# backplane.net
KiCad netlist of a schematic drawn in EAGLE
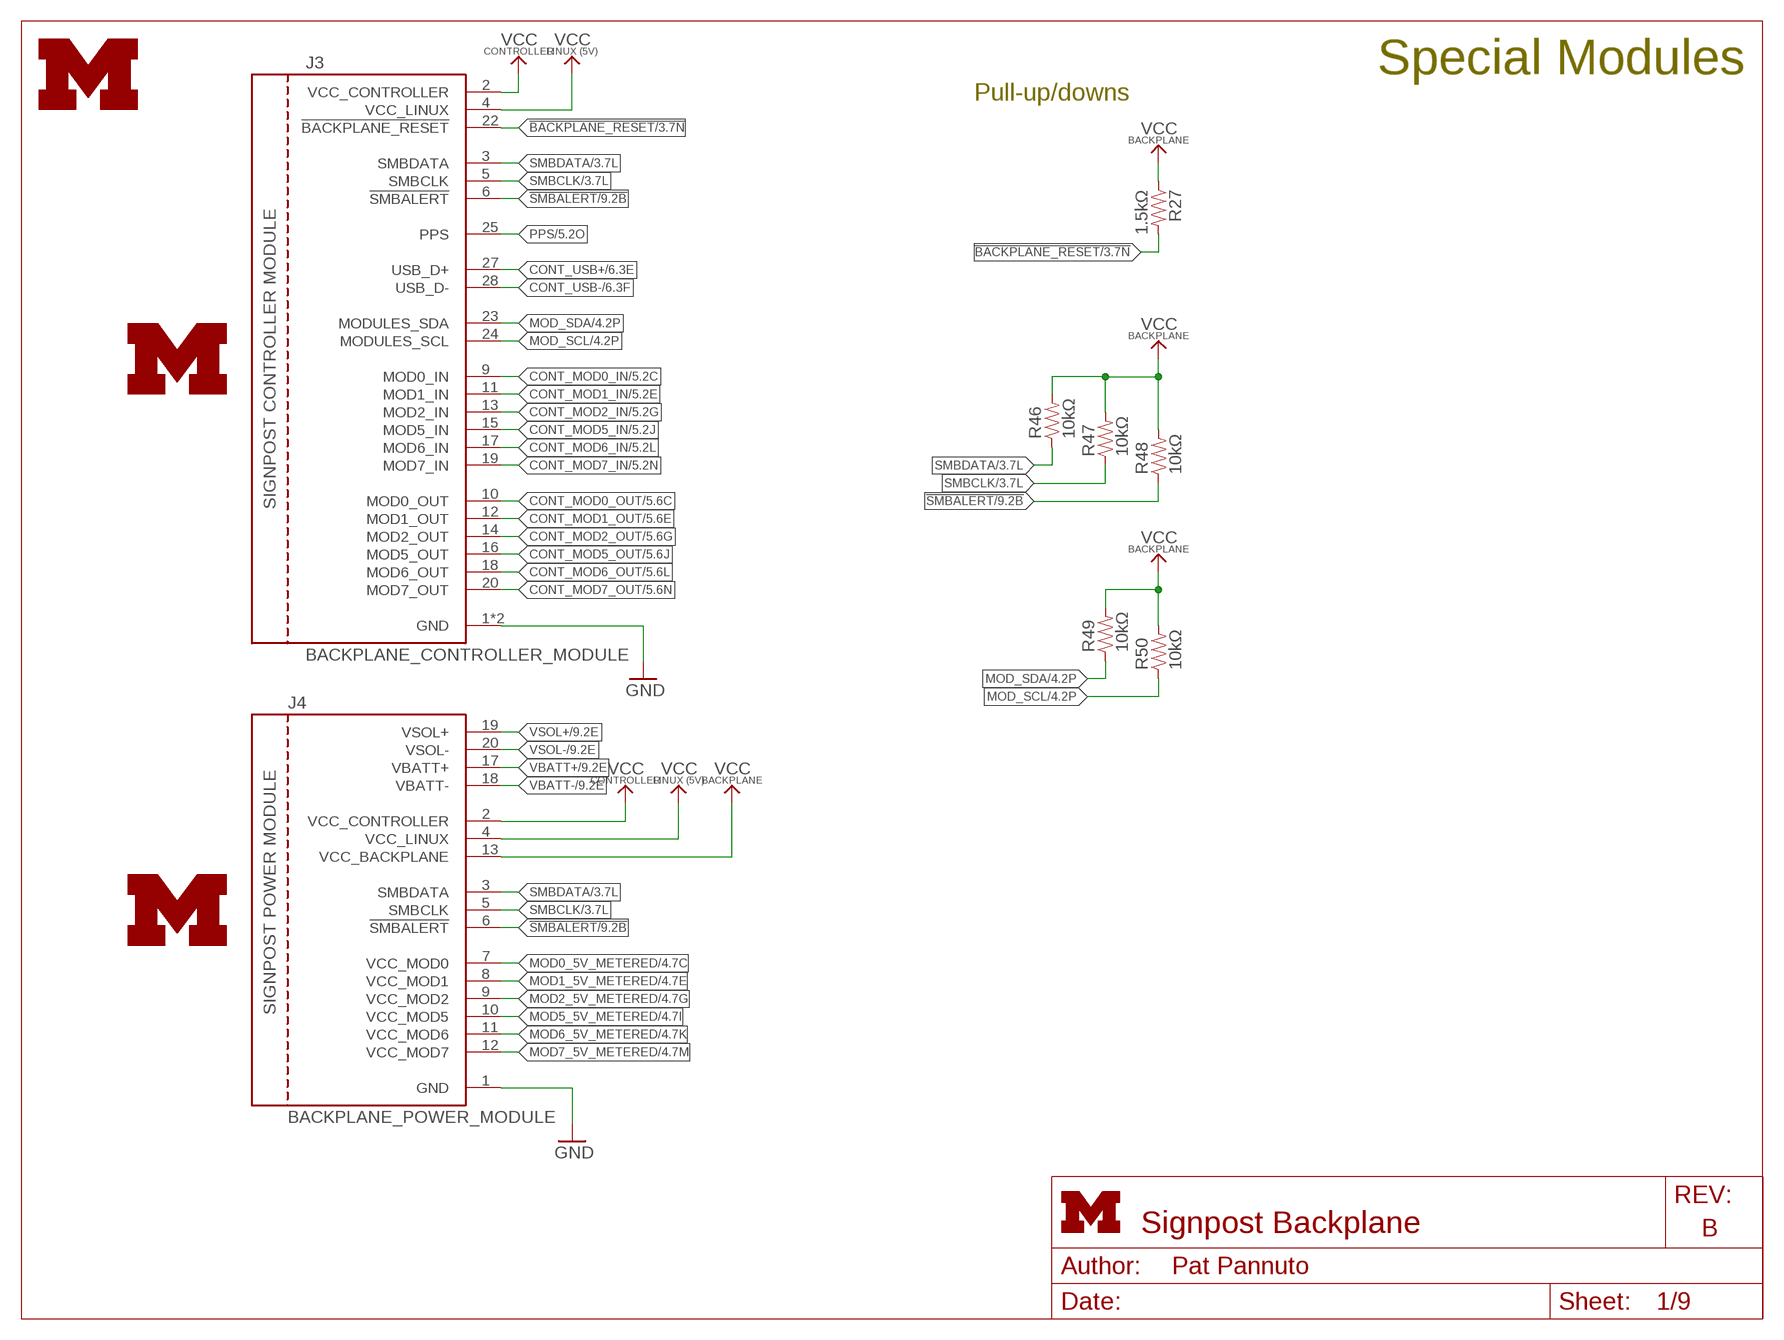
[diagram p0: schematic, sheet 1]
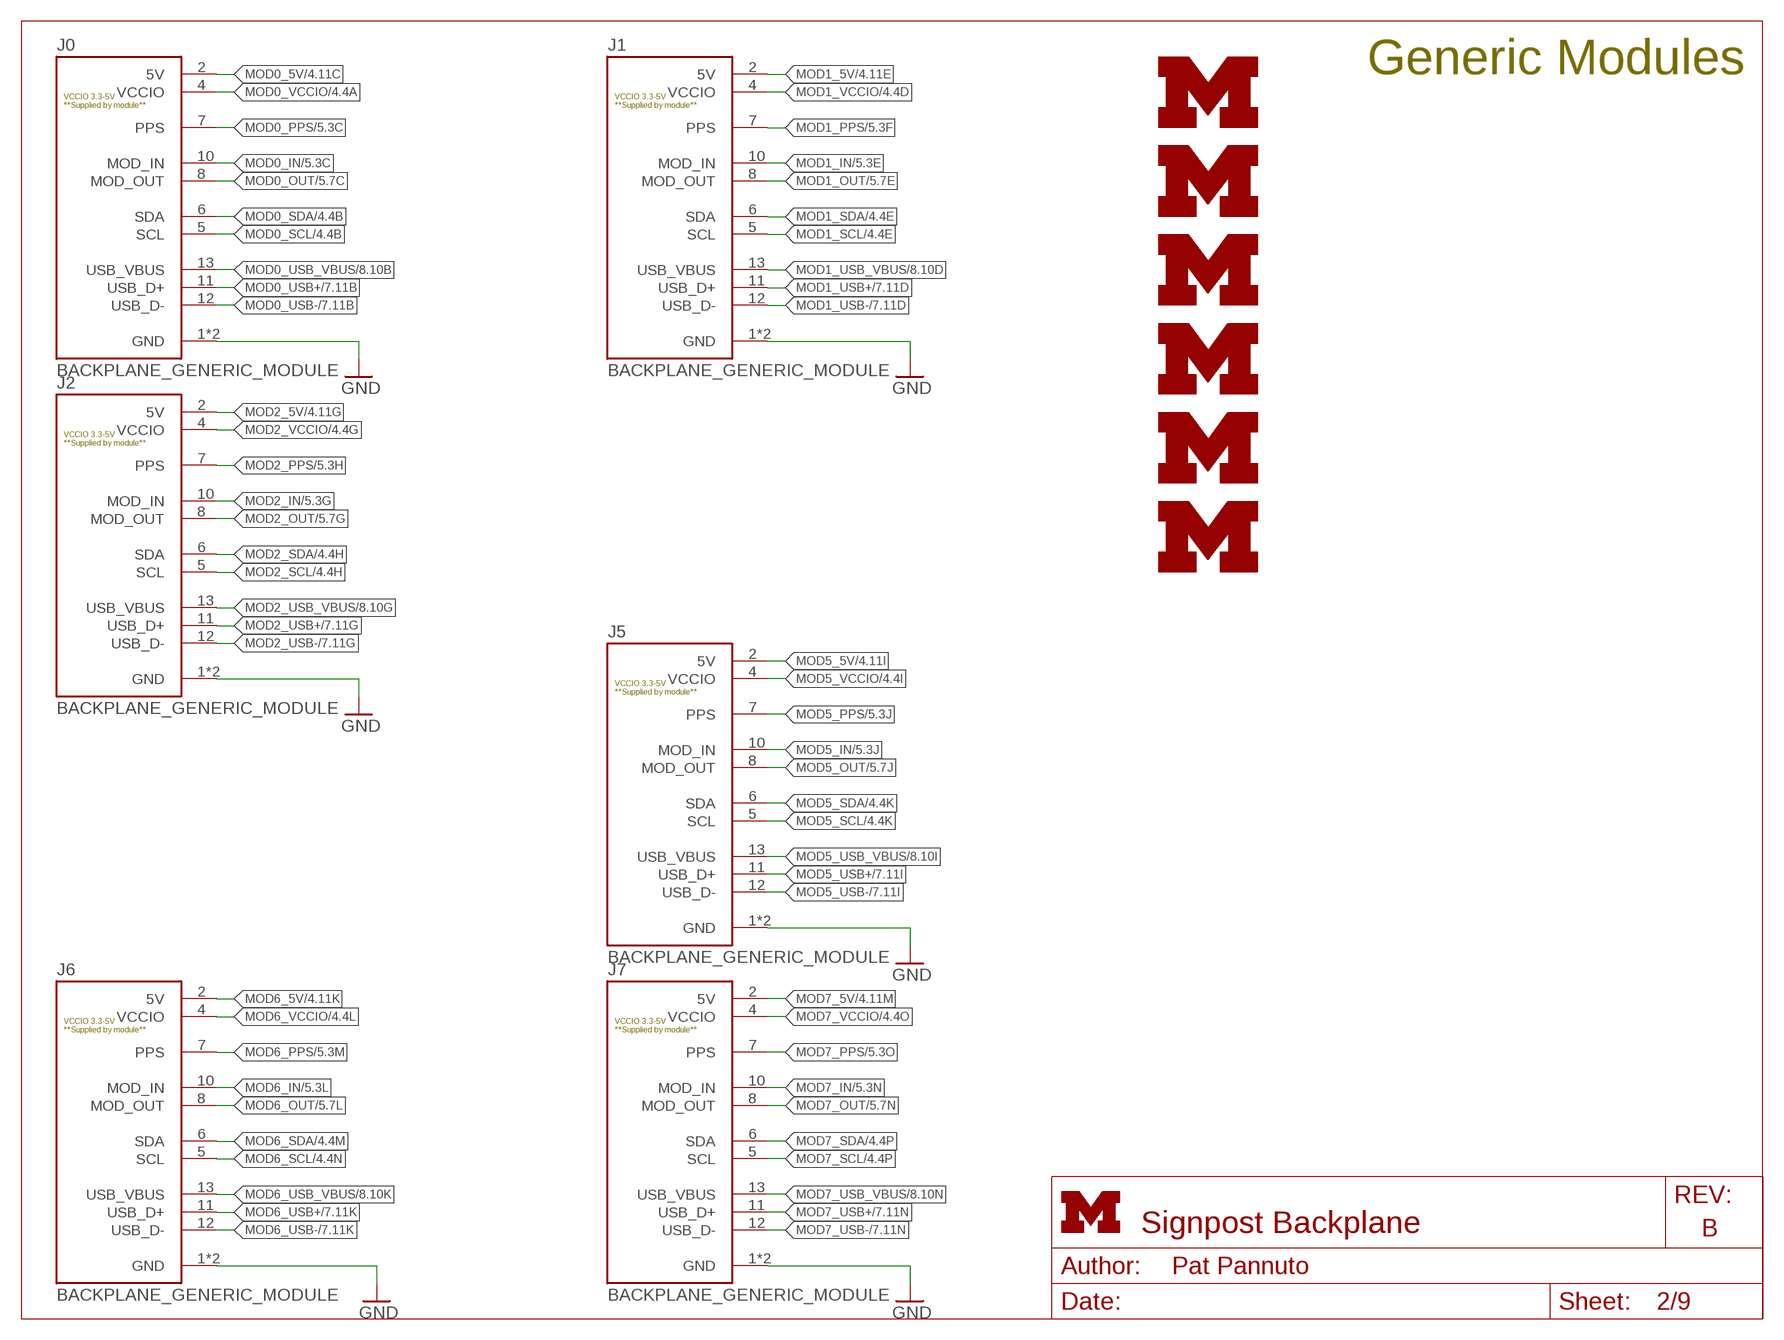
[diagram p1: schematic, sheet 2]
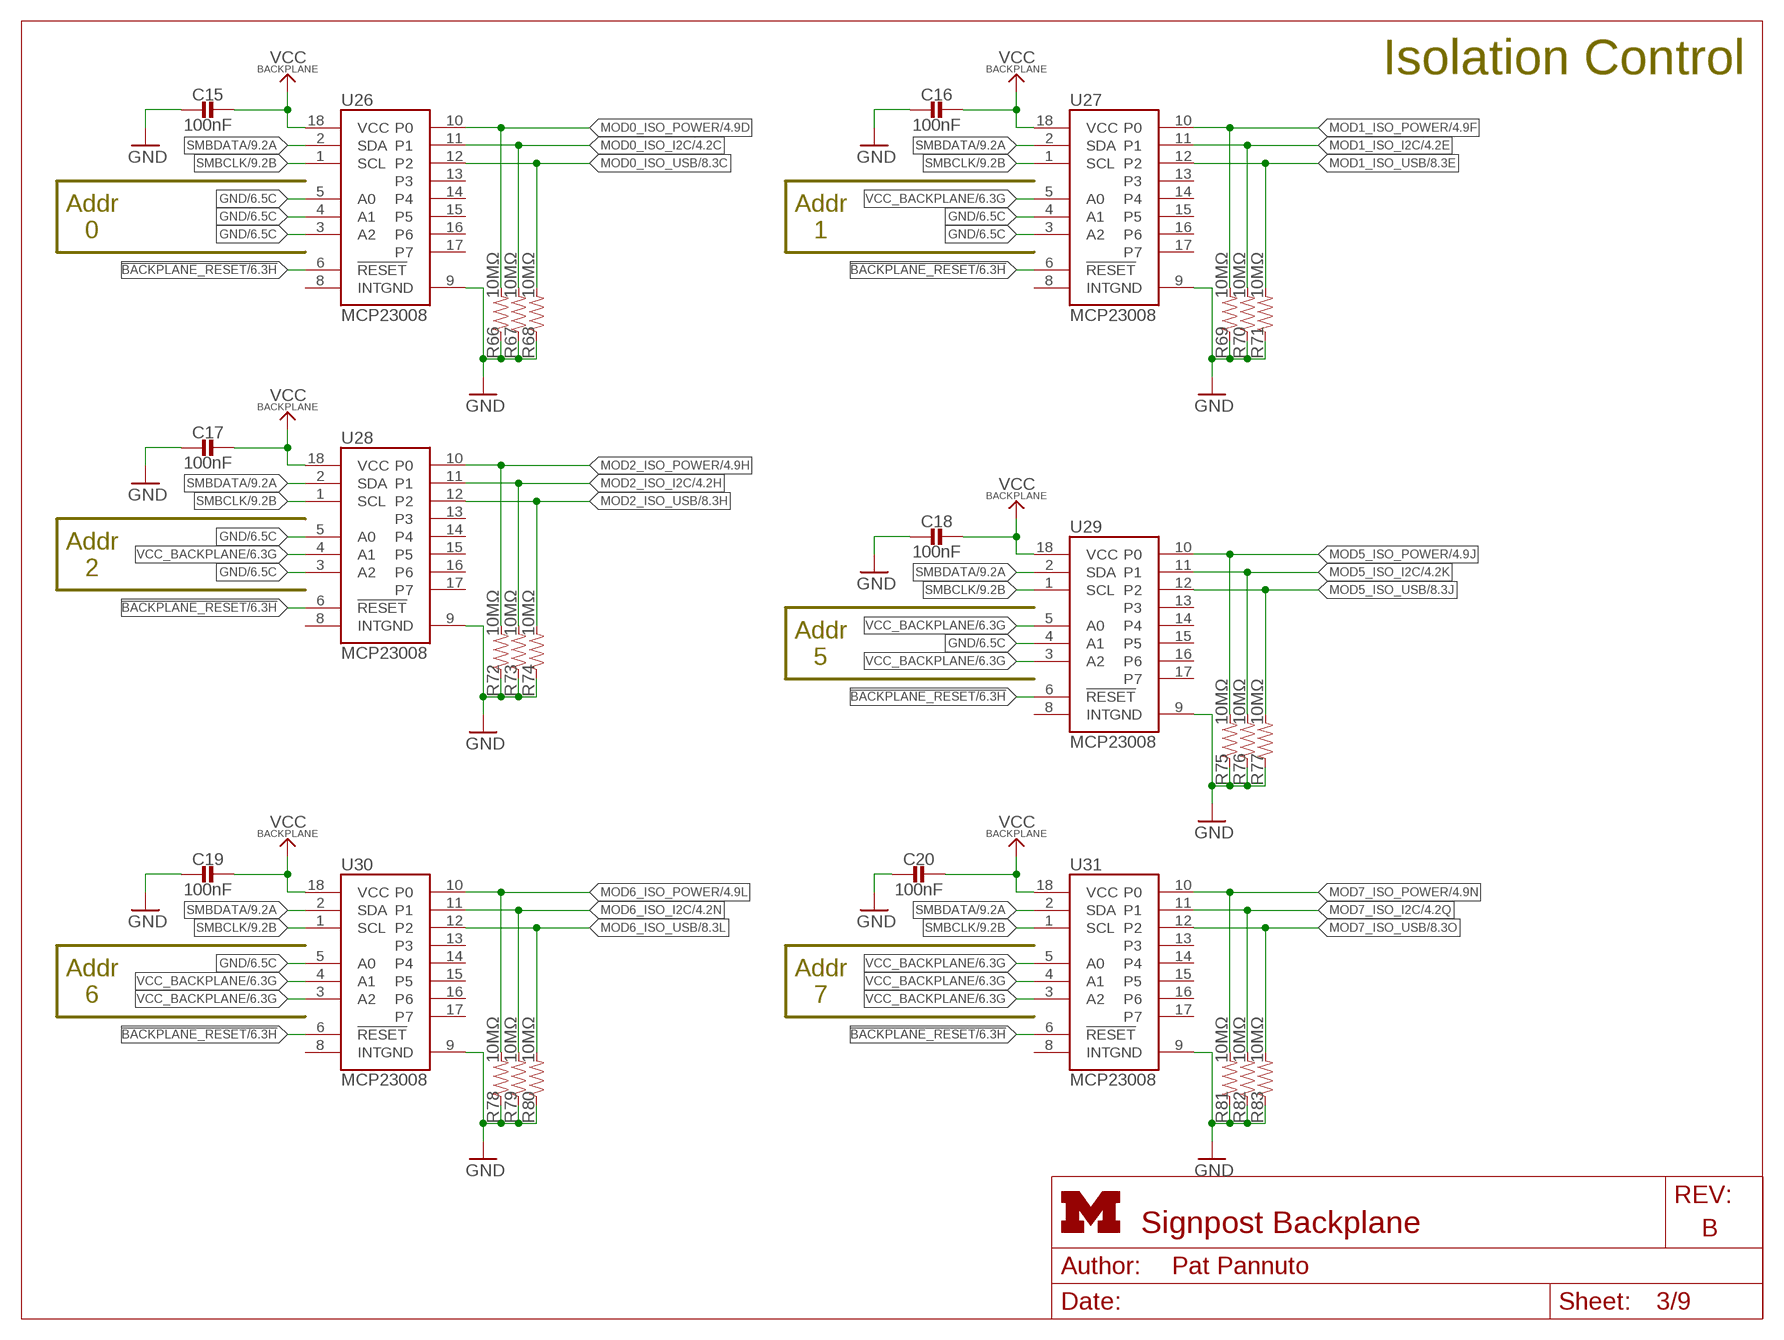
[diagram p2: schematic, sheet 3]
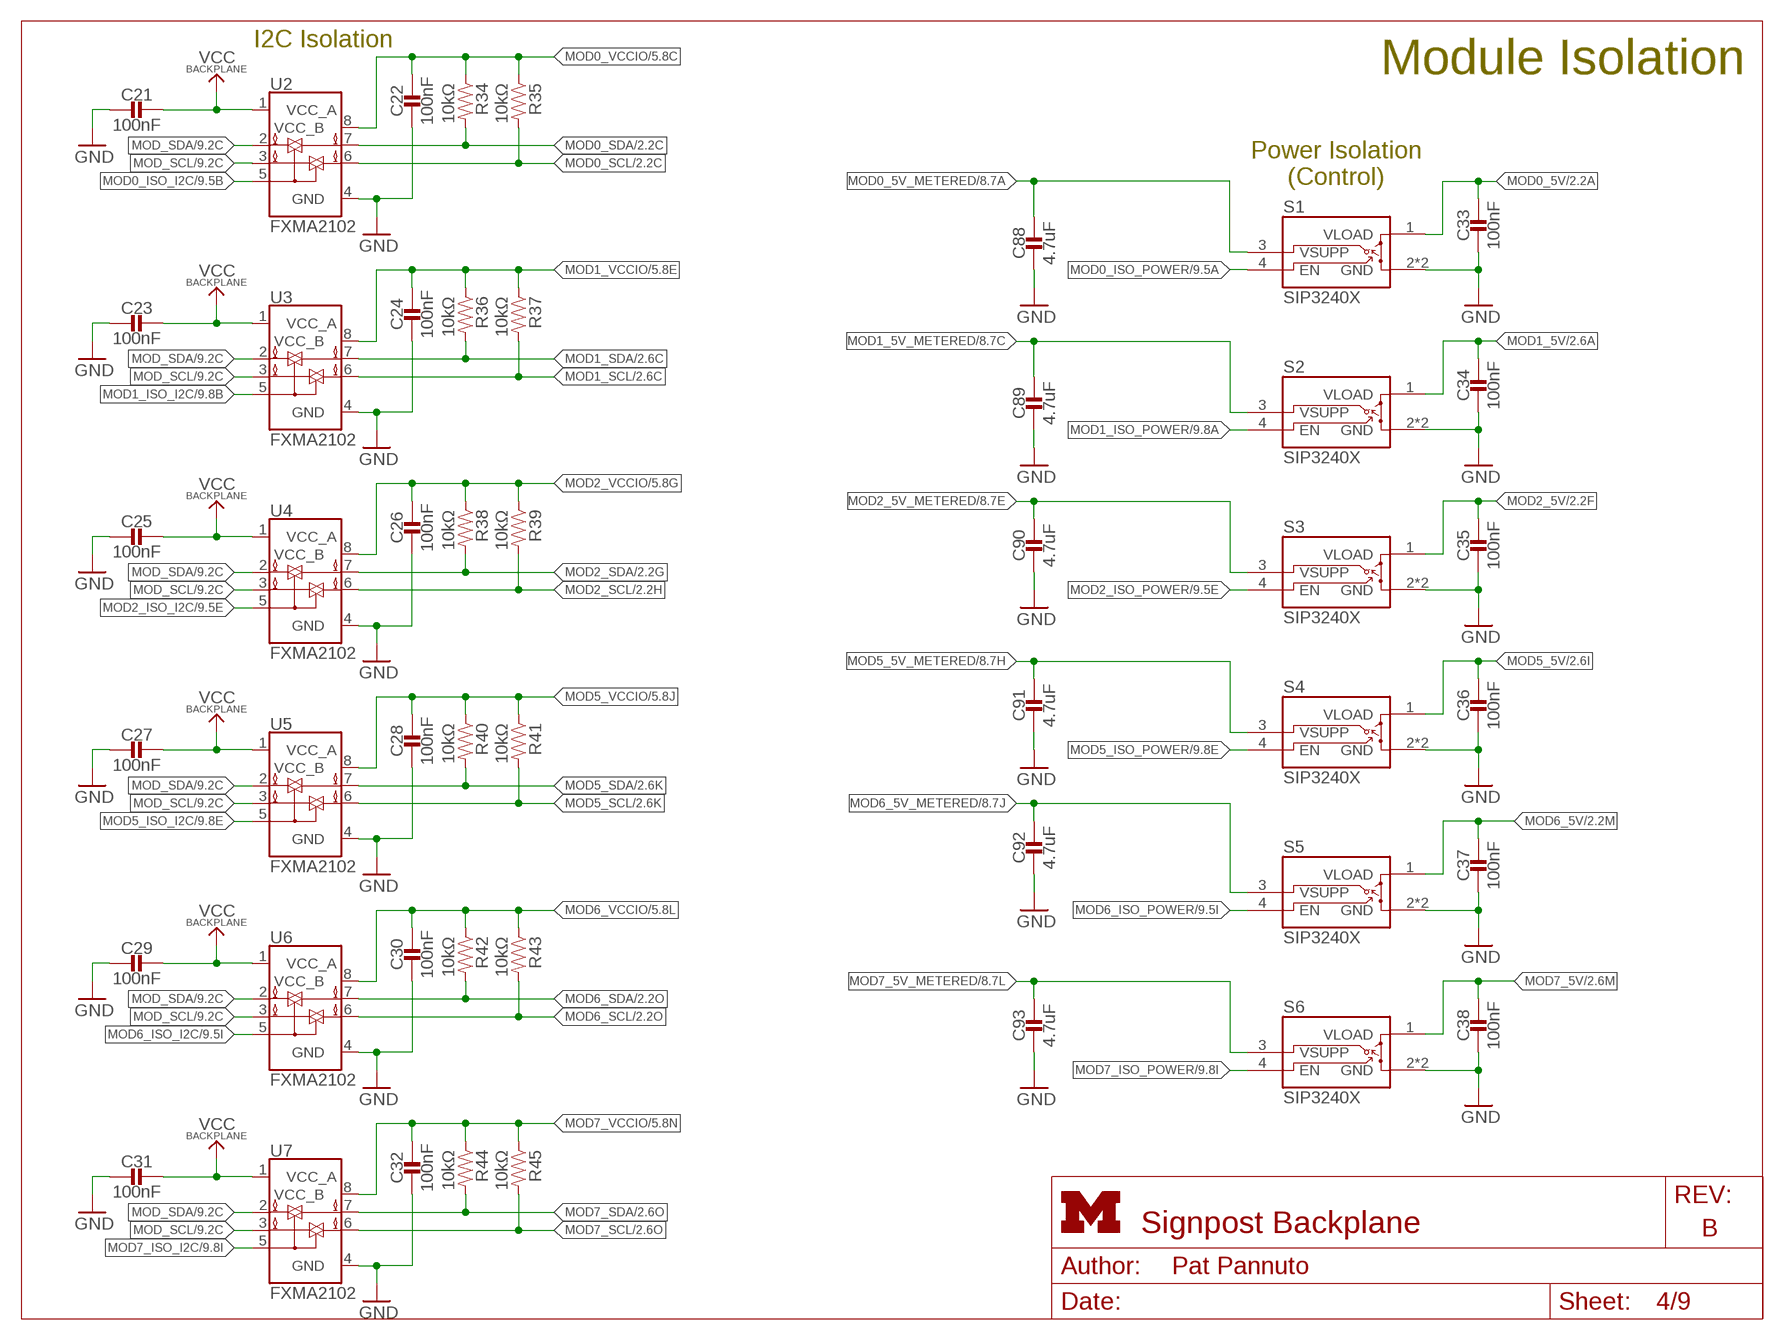
[diagram p3: schematic, sheet 4]
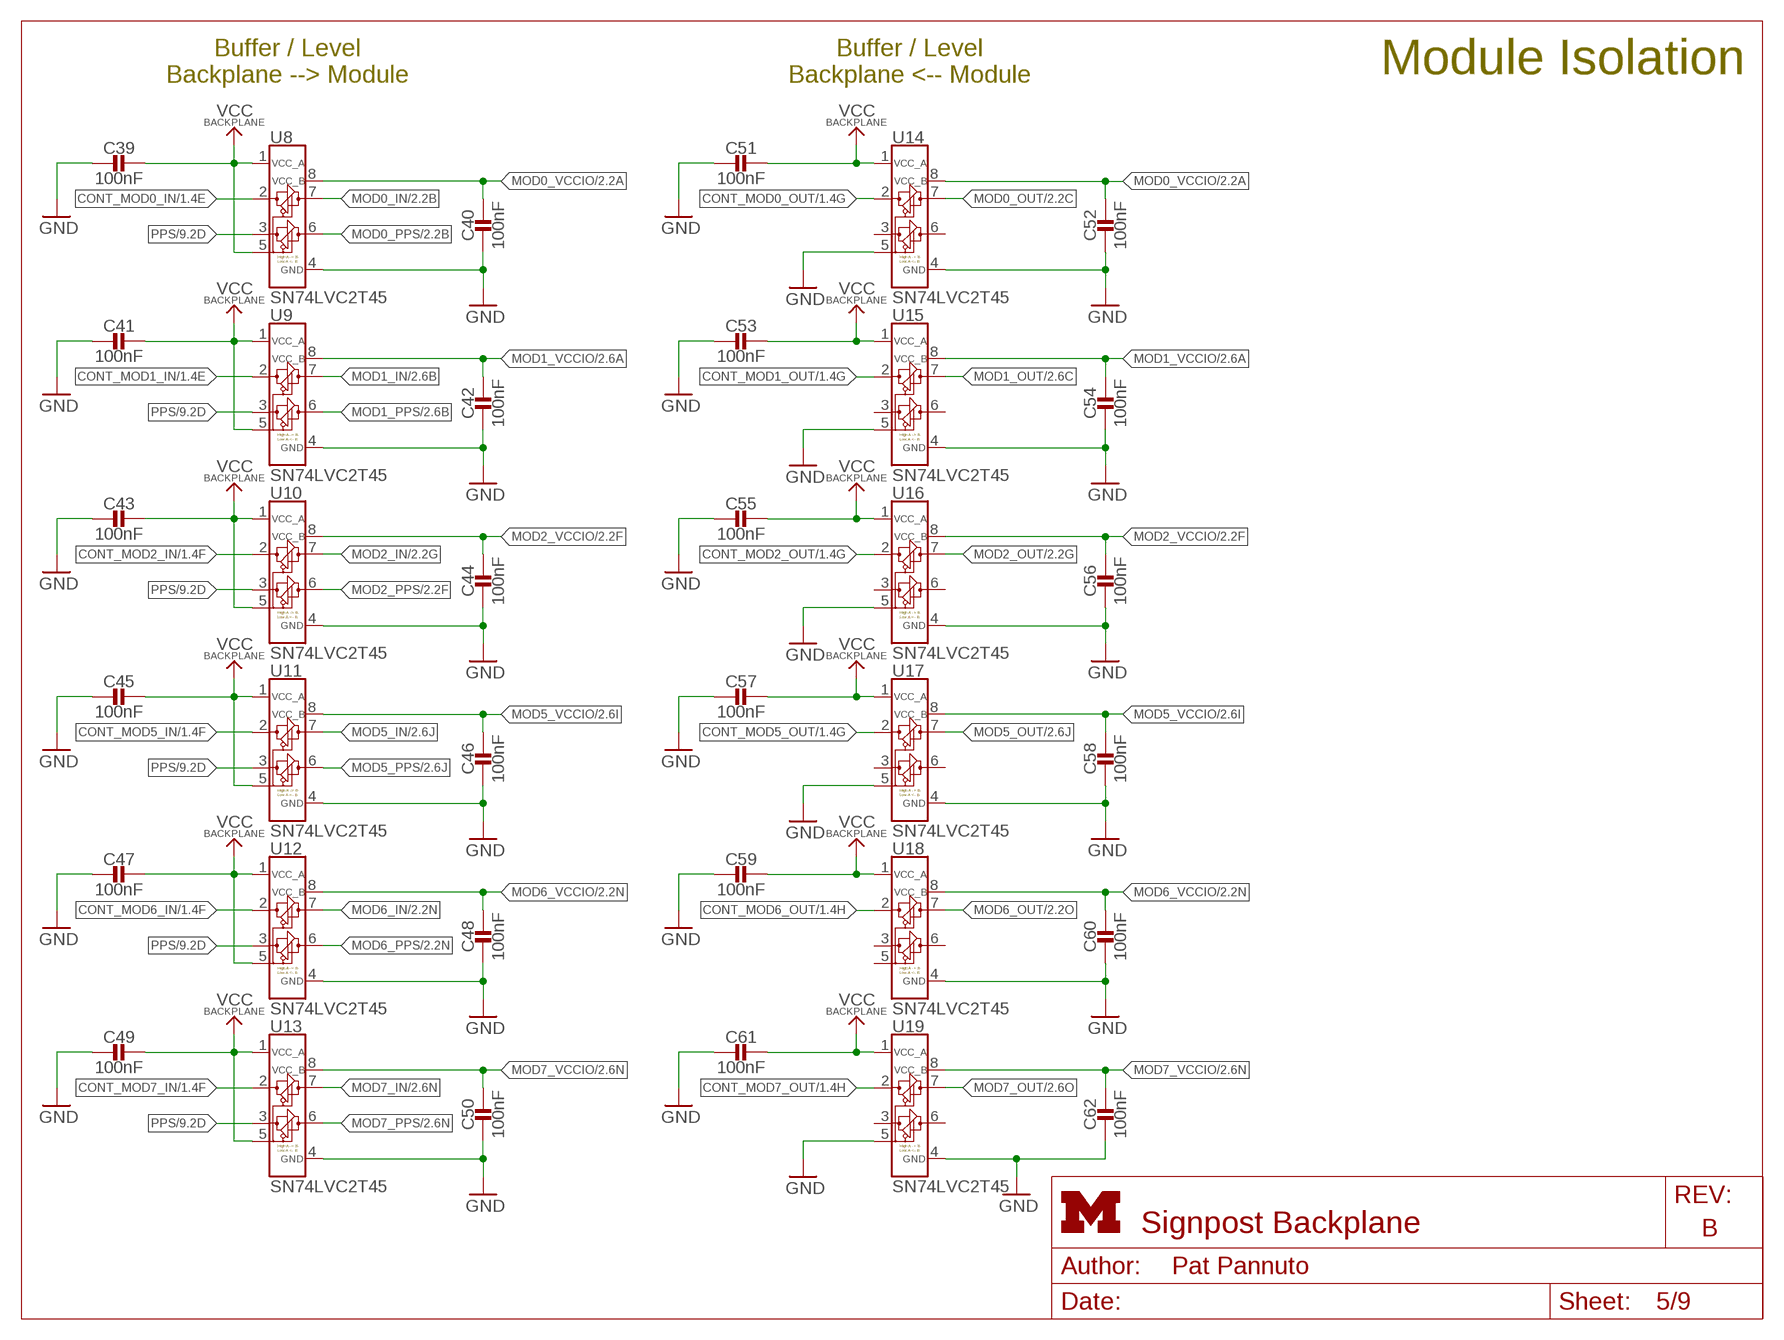
[diagram p4: schematic, sheet 5]
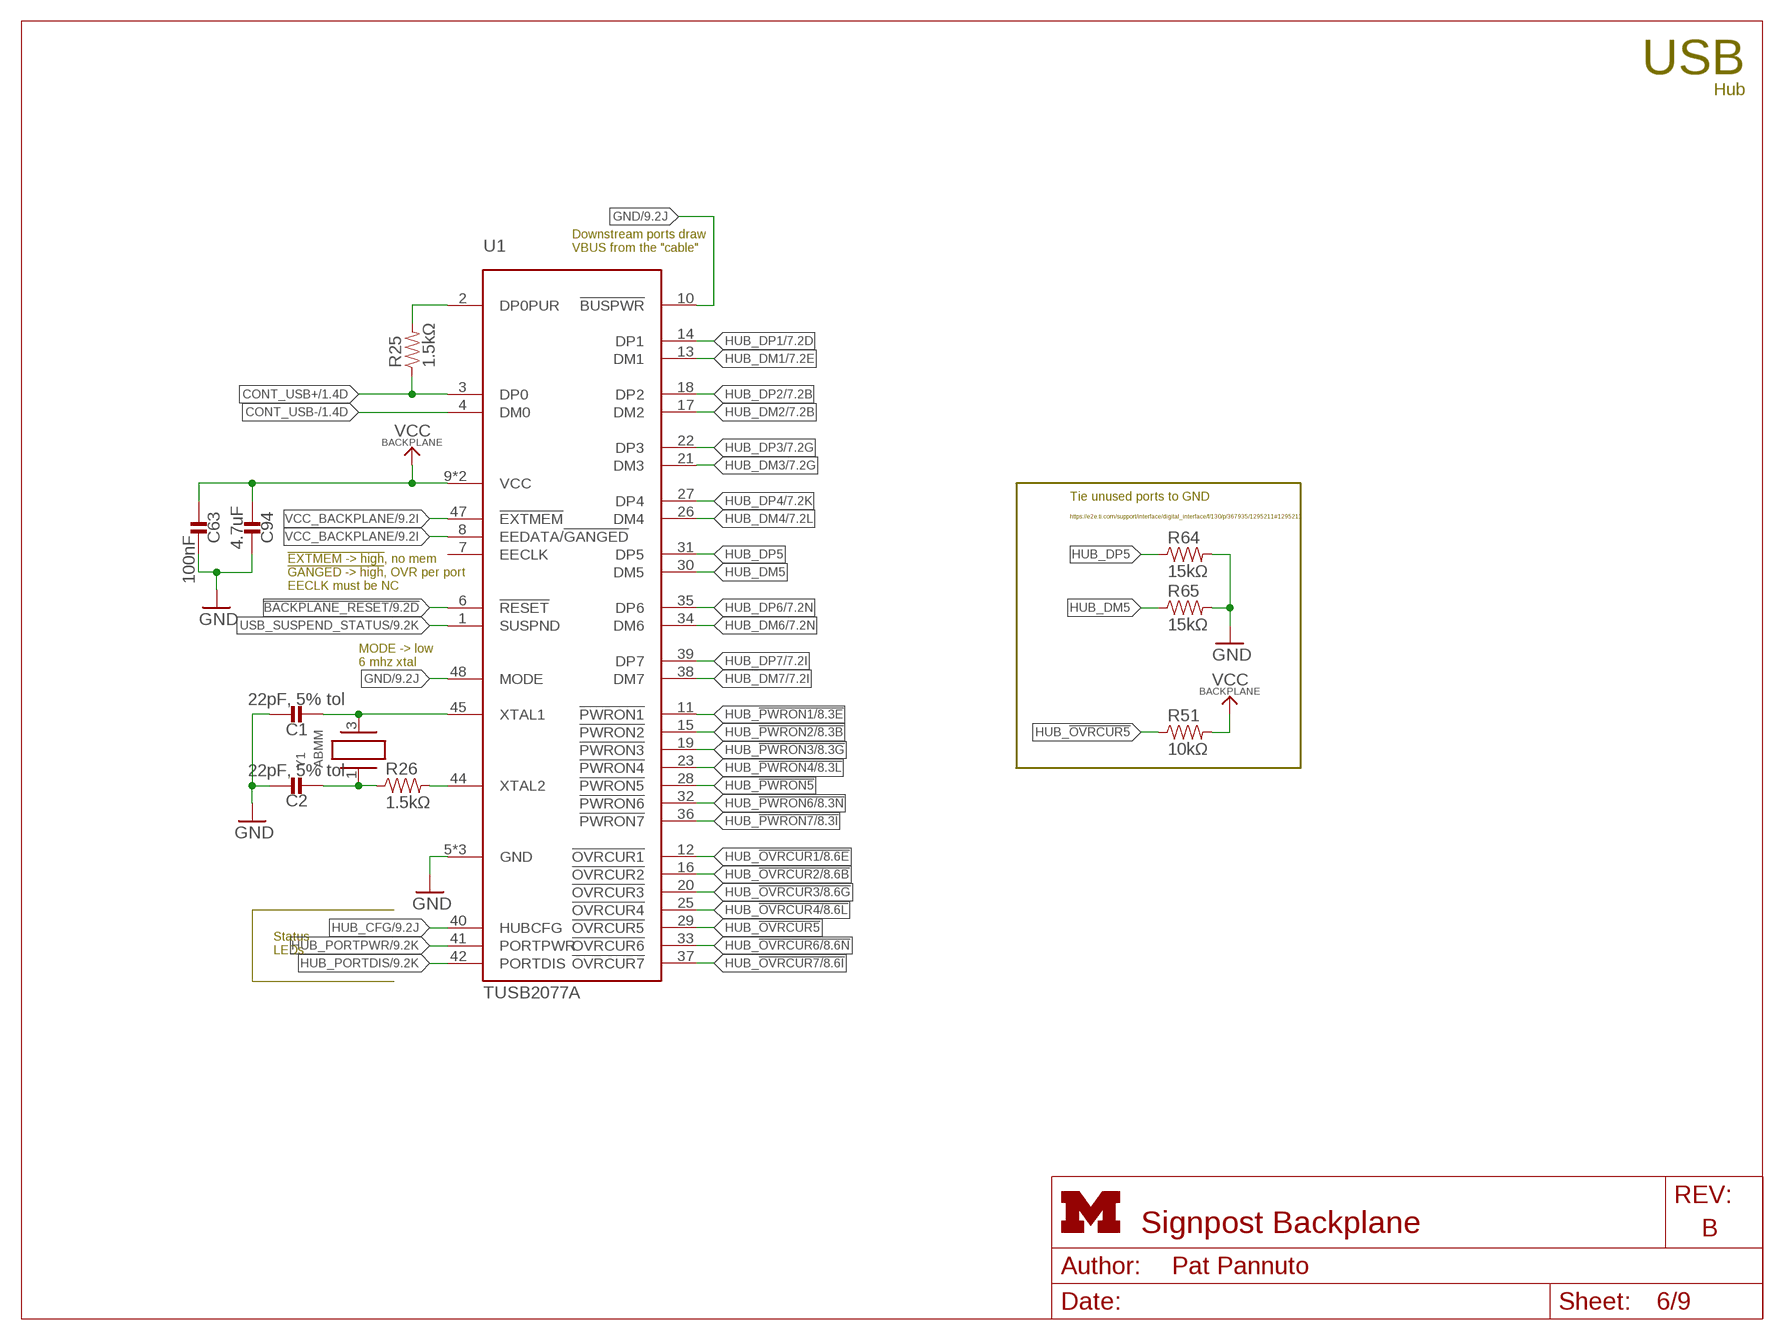
[diagram p5: schematic, sheet 6]
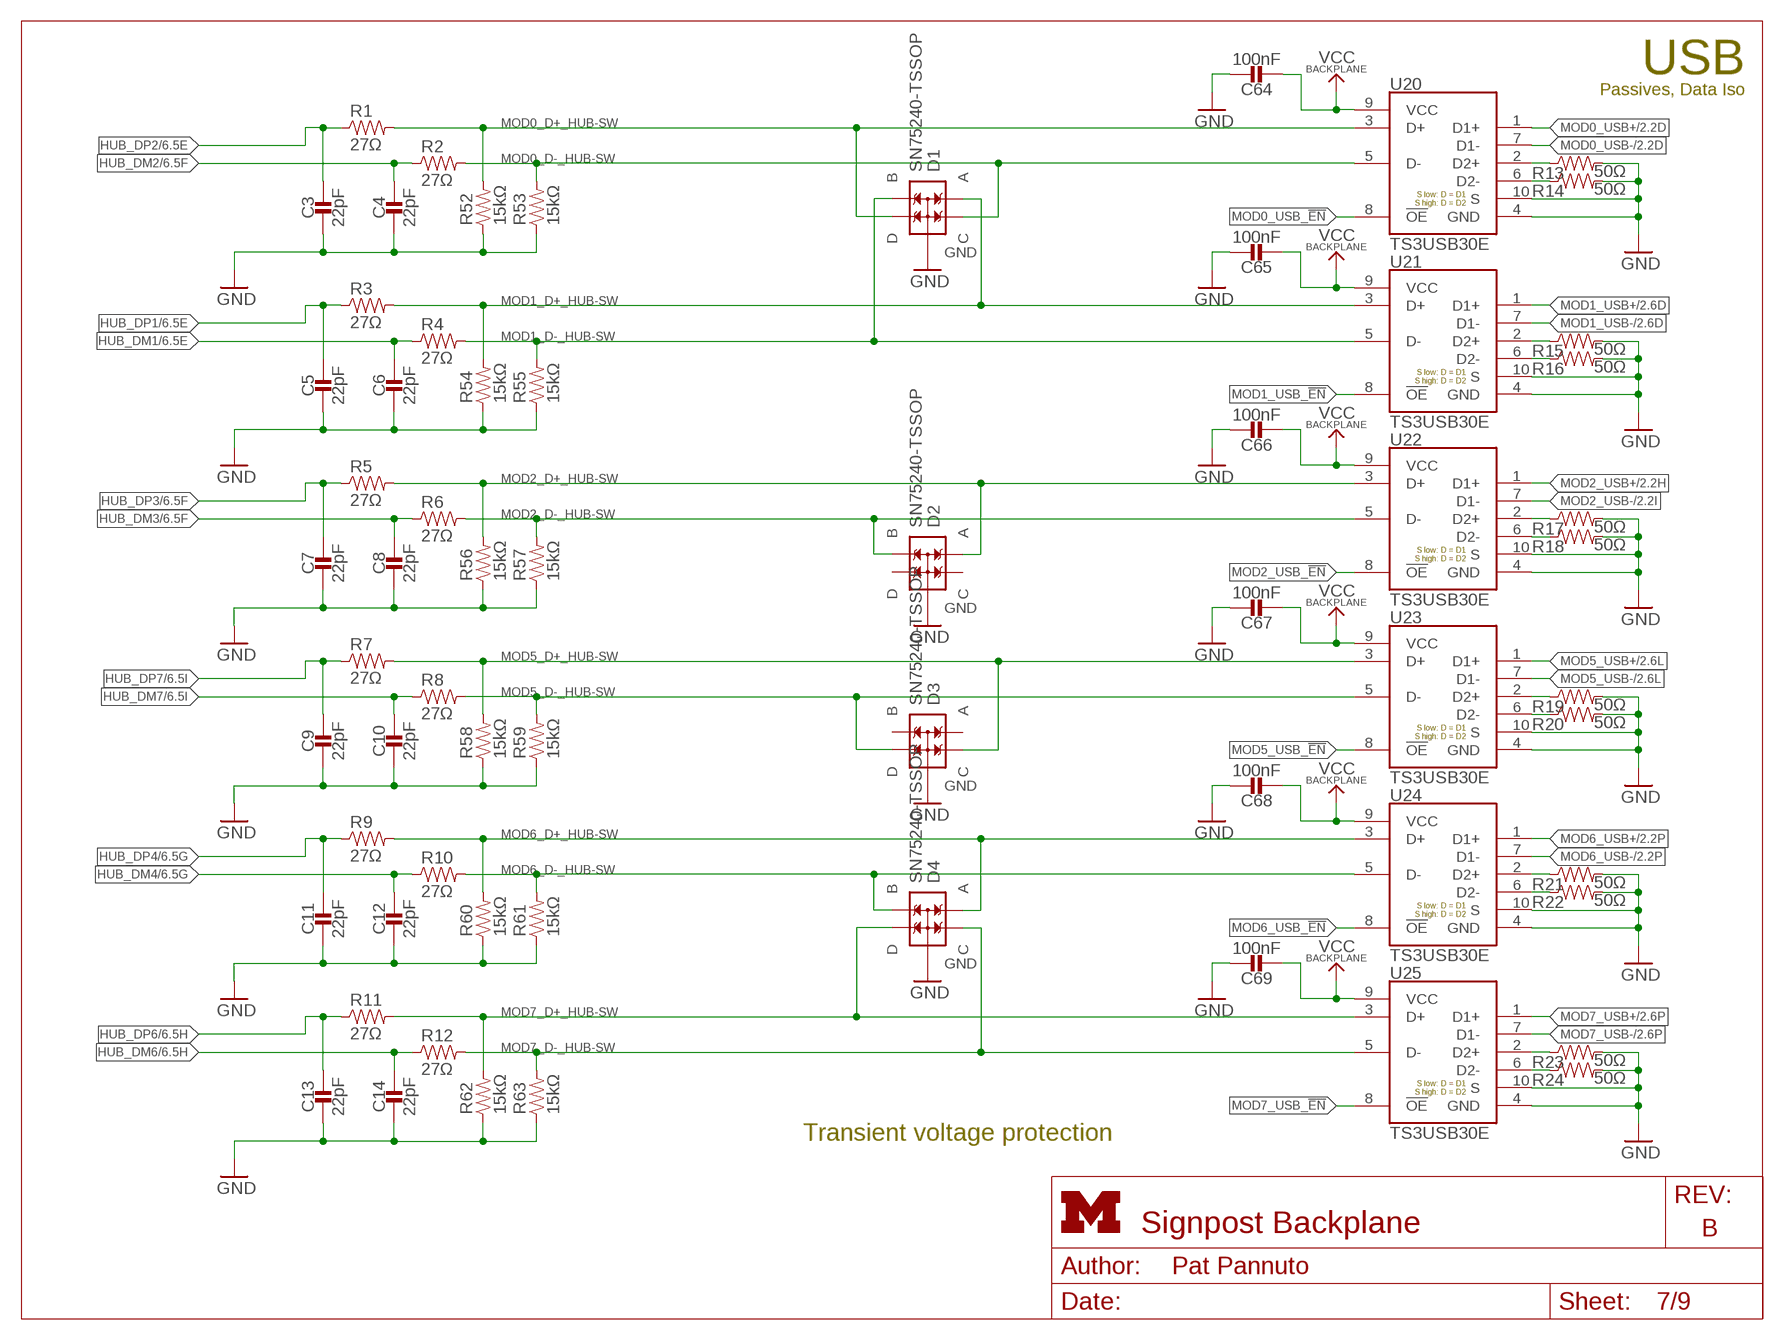
[diagram p6: schematic, sheet 7]
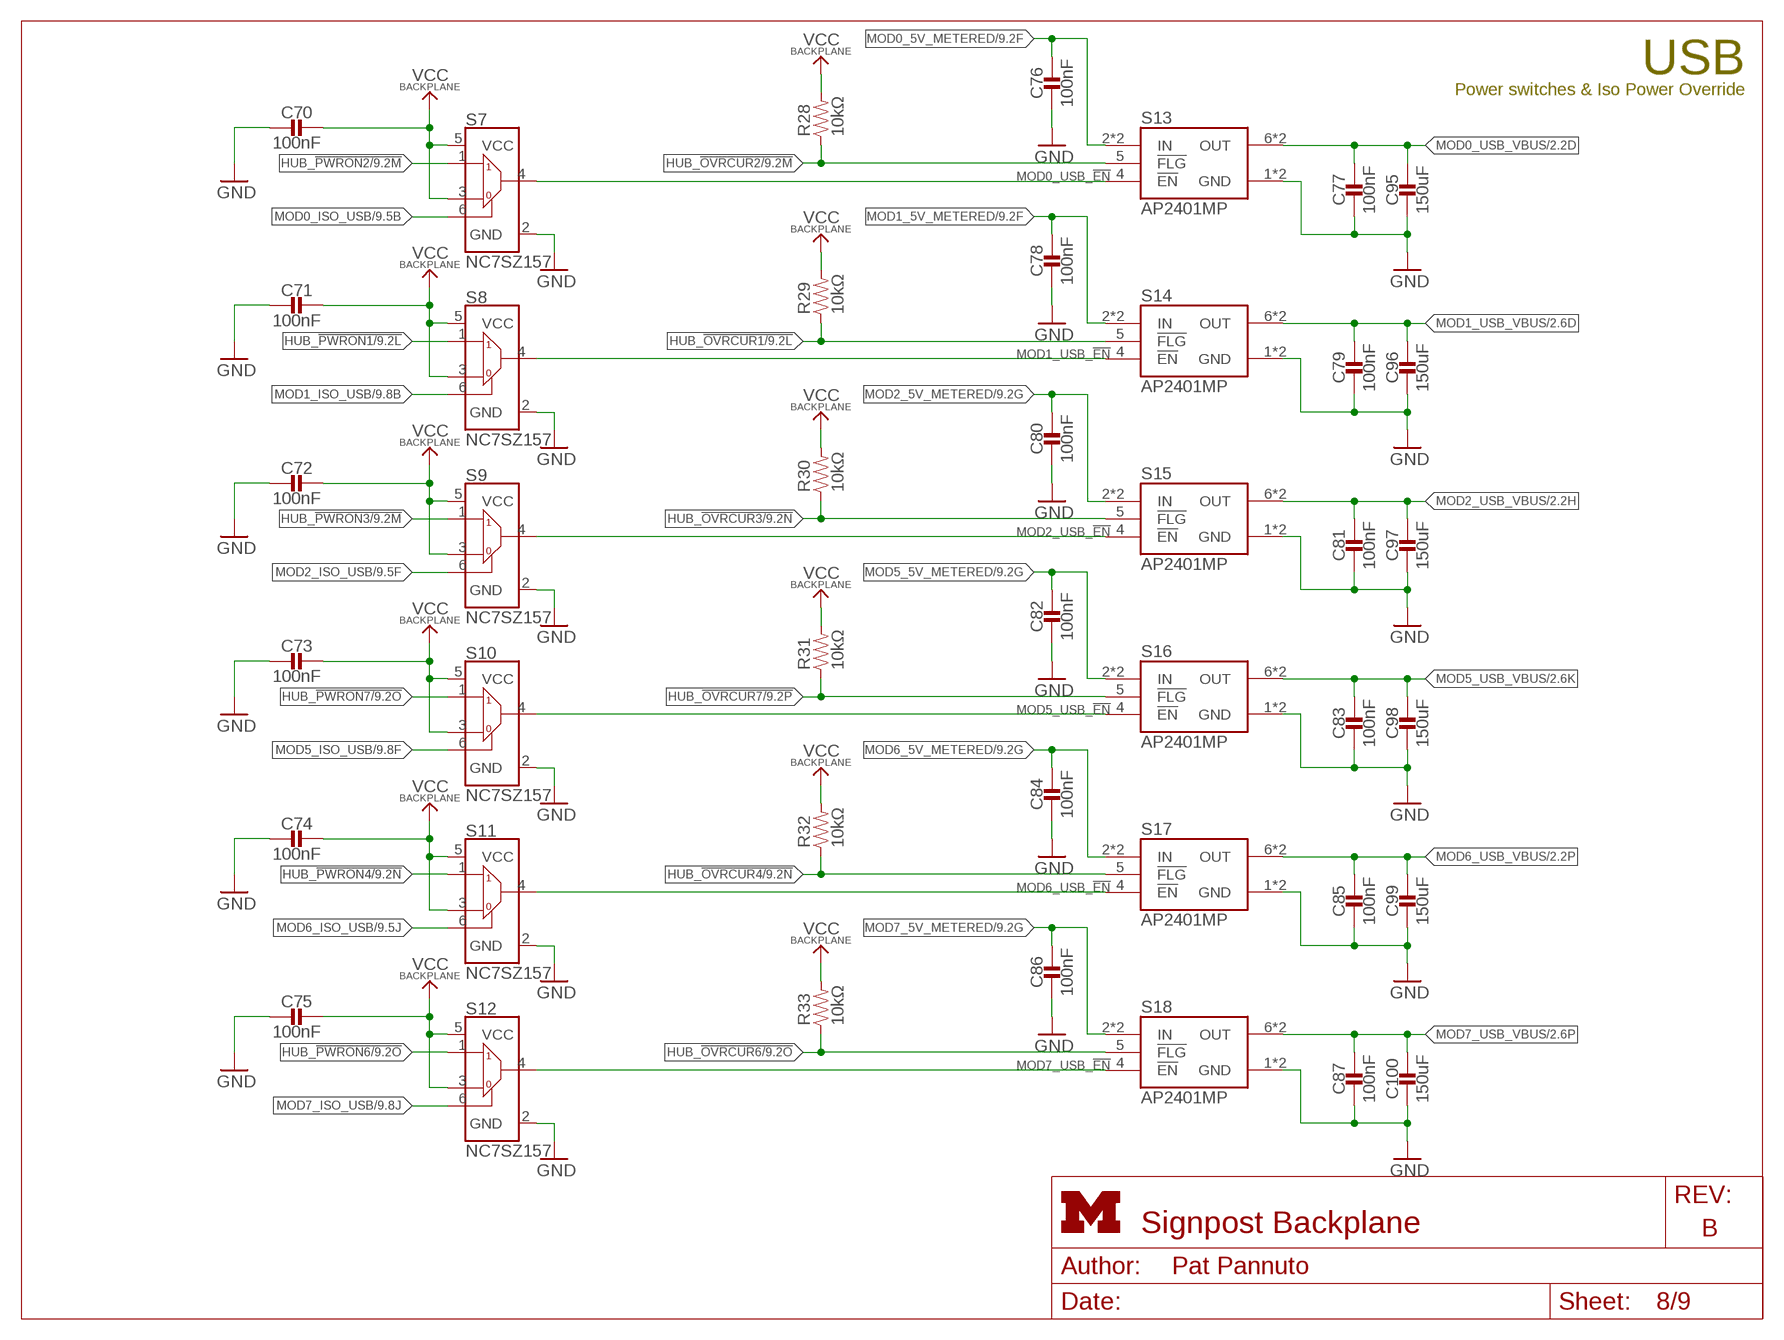
[diagram p7: schematic, sheet 8]
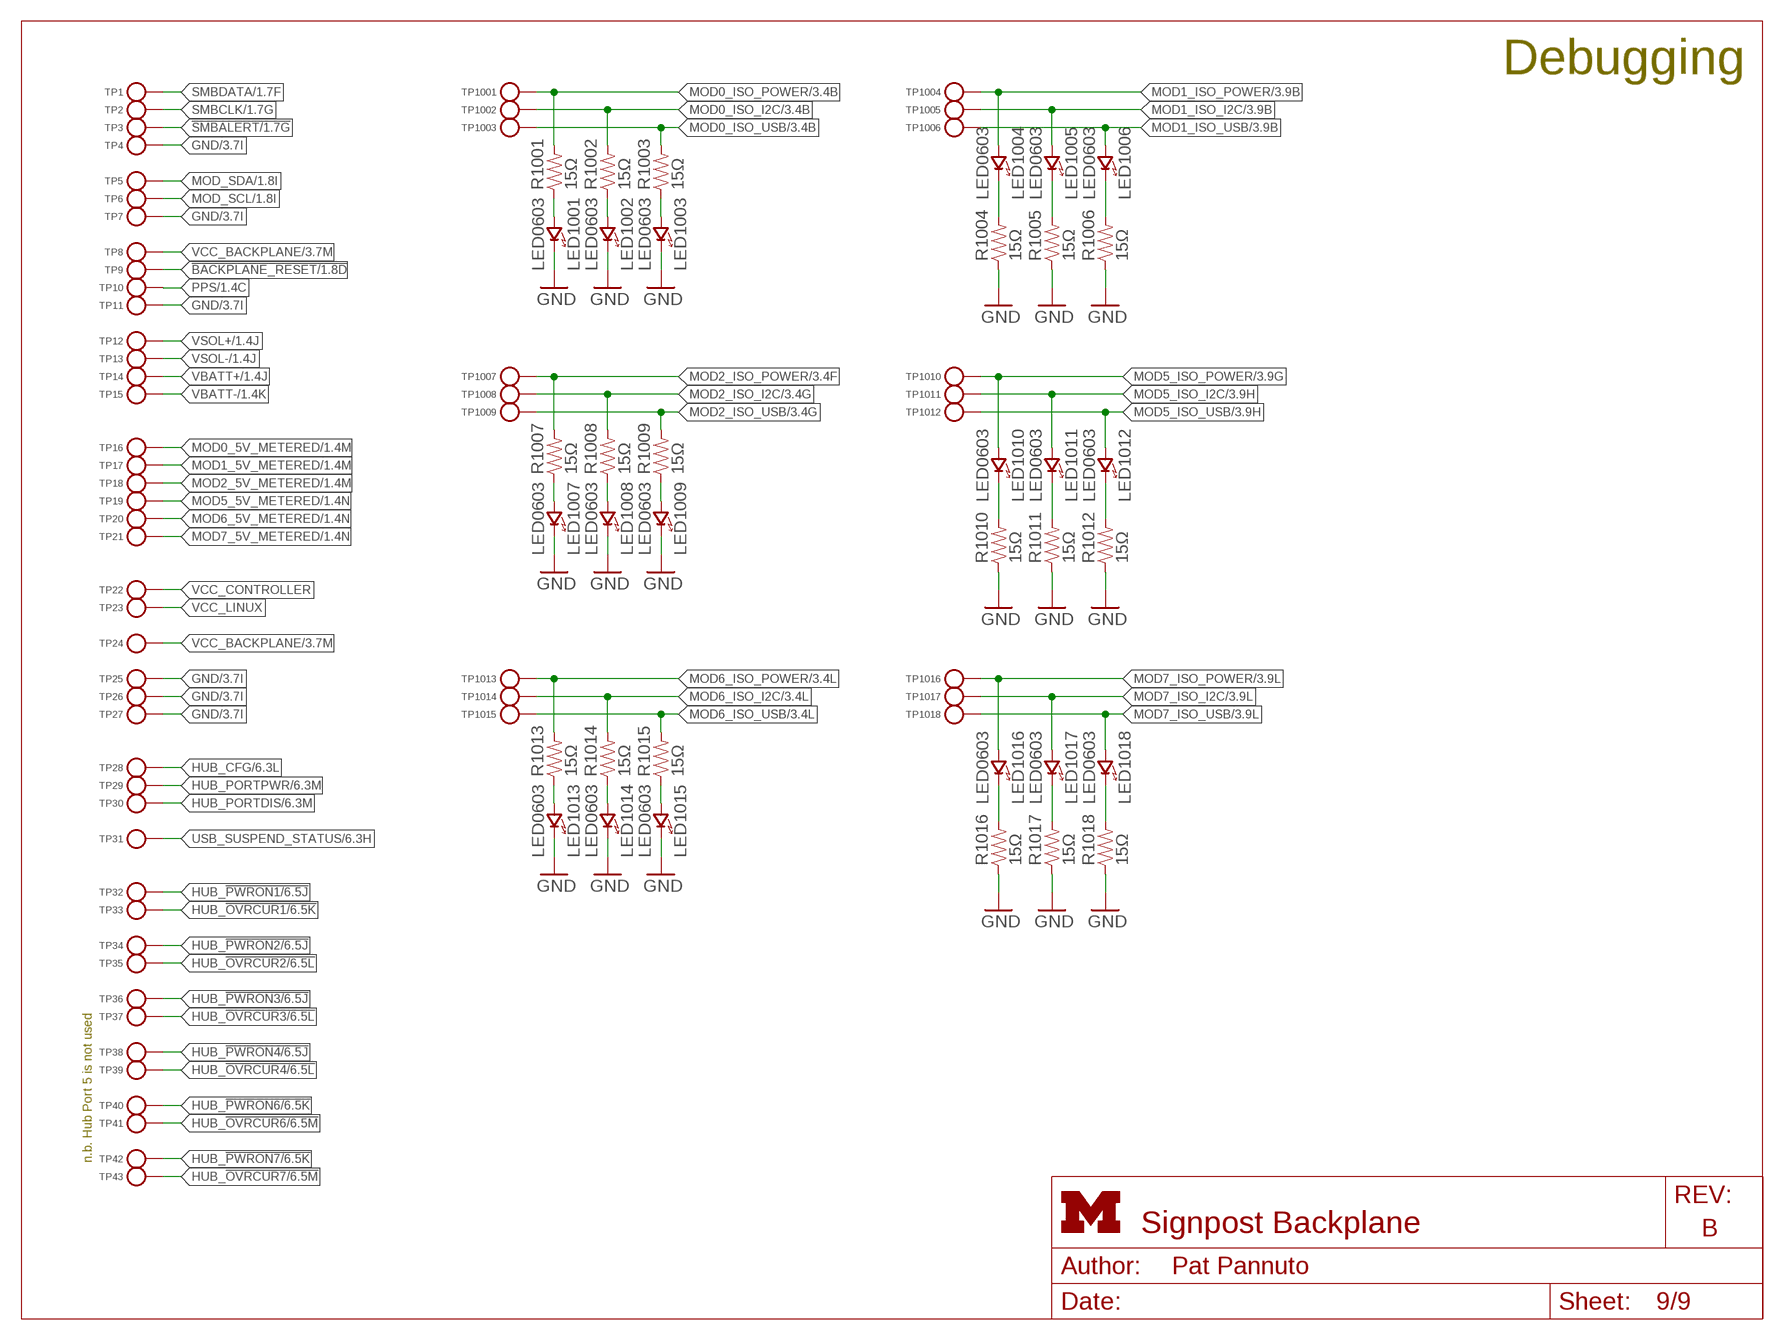
[diagram p8: schematic, sheet 9]

(export (version "E")
  (design (tool "Eeschema 10.0.6"))
  (components
    (comp (ref "C21")
      (value "100nF")
      (footprint "eagle-import:0603_CAP")
      (libsource (lib "eagle-import") (part "CAPACITOR0603_CAP"))
    )
    (comp (ref "C22")
      (value "100nF")
      (footprint "eagle-import:0603_CAP")
      (libsource (lib "eagle-import") (part "CAPACITOR0603_CAP"))
    )
    (comp (ref "C23")
      (value "100nF")
      (footprint "eagle-import:0603_CAP")
      (libsource (lib "eagle-import") (part "CAPACITOR0603_CAP"))
    )
    (comp (ref "C24")
      (value "100nF")
      (footprint "eagle-import:0603_CAP")
      (libsource (lib "eagle-import") (part "CAPACITOR0603_CAP"))
    )
    (comp (ref "C25")
      (value "100nF")
      (footprint "eagle-import:0603_CAP")
      (libsource (lib "eagle-import") (part "CAPACITOR0603_CAP"))
    )
    (comp (ref "C26")
      (value "100nF")
      (footprint "eagle-import:0603_CAP")
      (libsource (lib "eagle-import") (part "CAPACITOR0603_CAP"))
    )
    (comp (ref "C27")
      (value "100nF")
      (footprint "eagle-import:0603_CAP")
      (libsource (lib "eagle-import") (part "CAPACITOR0603_CAP"))
    )
    (comp (ref "C28")
      (value "100nF")
      (footprint "eagle-import:0603_CAP")
      (libsource (lib "eagle-import") (part "CAPACITOR0603_CAP"))
    )
    (comp (ref "C29")
      (value "100nF")
      (footprint "eagle-import:0603_CAP")
      (libsource (lib "eagle-import") (part "CAPACITOR0603_CAP"))
    )
    (comp (ref "C30")
      (value "100nF")
      (footprint "eagle-import:0603_CAP")
      (libsource (lib "eagle-import") (part "CAPACITOR0603_CAP"))
    )
    (comp (ref "C31")
      (value "100nF")
      (footprint "eagle-import:0603_CAP")
      (libsource (lib "eagle-import") (part "CAPACITOR0603_CAP"))
    )
    (comp (ref "C32")
      (value "100nF")
      (footprint "eagle-import:0603_CAP")
      (libsource (lib "eagle-import") (part "CAPACITOR0603_CAP"))
    )
    (comp (ref "C33")
      (value "100nF")
      (footprint "eagle-import:0603_CAP")
      (libsource (lib "eagle-import") (part "CAPACITOR0603_CAP"))
    )
    (comp (ref "C34")
      (value "100nF")
      (footprint "eagle-import:0603_CAP")
      (libsource (lib "eagle-import") (part "CAPACITOR0603_CAP"))
    )
    (comp (ref "C35")
      (value "100nF")
      (footprint "eagle-import:0603_CAP")
      (libsource (lib "eagle-import") (part "CAPACITOR0603_CAP"))
    )
    (comp (ref "C36")
      (value "100nF")
      (footprint "eagle-import:0603_CAP")
      (libsource (lib "eagle-import") (part "CAPACITOR0603_CAP"))
    )
    (comp (ref "C37")
      (value "100nF")
      (footprint "eagle-import:0603_CAP")
      (libsource (lib "eagle-import") (part "CAPACITOR0603_CAP"))
    )
    (comp (ref "C38")
      (value "100nF")
      (footprint "eagle-import:0603_CAP")
      (libsource (lib "eagle-import") (part "CAPACITOR0603_CAP"))
    )
    (comp (ref "C88")
      (value "4.7uF")
      (footprint "eagle-import:0603_CAP")
      (libsource (lib "eagle-import") (part "CAPACITOR0603_CAP"))
    )
    (comp (ref "C89")
      (value "4.7uF")
      (footprint "eagle-import:0603_CAP")
      (libsource (lib "eagle-import") (part "CAPACITOR0603_CAP"))
    )
    (comp (ref "C90")
      (value "4.7uF")
      (footprint "eagle-import:0603_CAP")
      (libsource (lib "eagle-import") (part "CAPACITOR0603_CAP"))
    )
    (comp (ref "C91")
      (value "4.7uF")
      (footprint "eagle-import:0603_CAP")
      (libsource (lib "eagle-import") (part "CAPACITOR0603_CAP"))
    )
    (comp (ref "C92")
      (value "4.7uF")
      (footprint "eagle-import:0603_CAP")
      (libsource (lib "eagle-import") (part "CAPACITOR0603_CAP"))
    )
    (comp (ref "C93")
      (value "4.7uF")
      (footprint "eagle-import:0603_CAP")
      (libsource (lib "eagle-import") (part "CAPACITOR0603_CAP"))
    )
    (comp (ref "R34")
      (value "10kΩ")
      (footprint "eagle-import:0603-RES")
      (libsource (lib "eagle-import") (part "RESISTOR0603_RES"))
    )
    (comp (ref "R35")
      (value "10kΩ")
      (footprint "eagle-import:0603-RES")
      (libsource (lib "eagle-import") (part "RESISTOR0603_RES"))
    )
    (comp (ref "R36")
      (value "10kΩ")
      (footprint "eagle-import:0603-RES")
      (libsource (lib "eagle-import") (part "RESISTOR0603_RES"))
    )
    (comp (ref "R37")
      (value "10kΩ")
      (footprint "eagle-import:0603-RES")
      (libsource (lib "eagle-import") (part "RESISTOR0603_RES"))
    )
    (comp (ref "R38")
      (value "10kΩ")
      (footprint "eagle-import:0603-RES")
      (libsource (lib "eagle-import") (part "RESISTOR0603_RES"))
    )
    (comp (ref "R39")
      (value "10kΩ")
      (footprint "eagle-import:0603-RES")
      (libsource (lib "eagle-import") (part "RESISTOR0603_RES"))
    )
    (comp (ref "R40")
      (value "10kΩ")
      (footprint "eagle-import:0603-RES")
      (libsource (lib "eagle-import") (part "RESISTOR0603_RES"))
    )
    (comp (ref "R41")
      (value "10kΩ")
      (footprint "eagle-import:0603-RES")
      (libsource (lib "eagle-import") (part "RESISTOR0603_RES"))
    )
    (comp (ref "R42")
      (value "10kΩ")
      (footprint "eagle-import:0603-RES")
      (libsource (lib "eagle-import") (part "RESISTOR0603_RES"))
    )
    (comp (ref "R43")
      (value "10kΩ")
      (footprint "eagle-import:0603-RES")
      (libsource (lib "eagle-import") (part "RESISTOR0603_RES"))
    )
    (comp (ref "R44")
      (value "10kΩ")
      (footprint "eagle-import:0603-RES")
      (libsource (lib "eagle-import") (part "RESISTOR0603_RES"))
    )
    (comp (ref "R45")
      (value "10kΩ")
      (footprint "eagle-import:0603-RES")
      (libsource (lib "eagle-import") (part "RESISTOR0603_RES"))
    )
    (comp (ref "S1")
      (value "SIP3240X")
      (footprint "eagle-import:TDFN4")
      (libsource (lib "eagle-import") (part "SIP3240X"))
    )
    (comp (ref "S2")
      (value "SIP3240X")
      (footprint "eagle-import:TDFN4")
      (libsource (lib "eagle-import") (part "SIP3240X"))
    )
    (comp (ref "S3")
      (value "SIP3240X")
      (footprint "eagle-import:TDFN4")
      (libsource (lib "eagle-import") (part "SIP3240X"))
    )
    (comp (ref "S4")
      (value "SIP3240X")
      (footprint "eagle-import:TDFN4")
      (libsource (lib "eagle-import") (part "SIP3240X"))
    )
    (comp (ref "S5")
      (value "SIP3240X")
      (footprint "eagle-import:TDFN4")
      (libsource (lib "eagle-import") (part "SIP3240X"))
    )
    (comp (ref "S6")
      (value "SIP3240X")
      (footprint "eagle-import:TDFN4")
      (libsource (lib "eagle-import") (part "SIP3240X"))
    )
    (comp (ref "U2")
      (value "FXMA2102")
      (footprint "eagle-import:UMLP-8")
      (libsource (lib "eagle-import") (part "FXMA2102"))
    )
    (comp (ref "U3")
      (value "FXMA2102")
      (footprint "eagle-import:UMLP-8")
      (libsource (lib "eagle-import") (part "FXMA2102"))
    )
    (comp (ref "U4")
      (value "FXMA2102")
      (footprint "eagle-import:UMLP-8")
      (libsource (lib "eagle-import") (part "FXMA2102"))
    )
    (comp (ref "U5")
      (value "FXMA2102")
      (footprint "eagle-import:UMLP-8")
      (libsource (lib "eagle-import") (part "FXMA2102"))
    )
    (comp (ref "U6")
      (value "FXMA2102")
      (footprint "eagle-import:UMLP-8")
      (libsource (lib "eagle-import") (part "FXMA2102"))
    )
    (comp (ref "U7")
      (value "FXMA2102")
      (footprint "eagle-import:UMLP-8")
      (libsource (lib "eagle-import") (part "FXMA2102"))
    )
    (comp (ref "C1")
      (value "22pF, 5% tol")
      (footprint "eagle-import:0603_CAP")
      (libsource (lib "eagle-import") (part "CAPACITOR0603_CAP"))
    )
    (comp (ref "C2")
      (value "22pF, 5% tol")
      (footprint "eagle-import:0603_CAP")
      (libsource (lib "eagle-import") (part "CAPACITOR0603_CAP"))
    )
    (comp (ref "C63")
      (value "100nF")
      (footprint "eagle-import:0603_CAP")
      (libsource (lib "eagle-import") (part "CAPACITOR0603_CAP"))
    )
    (comp (ref "C94")
      (value "4.7uF")
      (footprint "eagle-import:0603_CAP")
      (libsource (lib "eagle-import") (part "CAPACITOR0603_CAP"))
    )
    (comp (ref "R25")
      (value "1.5kΩ")
      (footprint "eagle-import:0603-RES")
      (libsource (lib "eagle-import") (part "RESISTOR0603_RES"))
    )
    (comp (ref "R26")
      (value "1.5kΩ")
      (footprint "eagle-import:0603-RES")
      (libsource (lib "eagle-import") (part "RESISTOR0603_RES"))
    )
    (comp (ref "R51")
      (value "10kΩ")
      (footprint "eagle-import:0603-RES")
      (libsource (lib "eagle-import") (part "RESISTOR0603_RES"))
    )
    (comp (ref "R64")
      (value "15kΩ")
      (footprint "eagle-import:0603-RES")
      (libsource (lib "eagle-import") (part "RESISTOR0603_RES"))
    )
    (comp (ref "R65")
      (value "15kΩ")
      (footprint "eagle-import:0603-RES")
      (libsource (lib "eagle-import") (part "RESISTOR0603_RES"))
    )
    (comp (ref "U1")
      (value "TUSB2077A")
      (footprint "eagle-import:LQFP-48")
      (libsource (lib "eagle-import") (part "TUSB2077A"))
    )
    (comp (ref "Y1")
      (value "ABMM")
      (footprint "eagle-import:ABMM")
      (libsource (lib "eagle-import") (part "ABMM"))
    )
    (comp (ref "C3")
      (value "22pF")
      (footprint "eagle-import:0402_CAP")
      (libsource (lib "eagle-import") (part "CAPACITOR0402_CAP"))
    )
    (comp (ref "C4")
      (value "22pF")
      (footprint "eagle-import:0402_CAP")
      (libsource (lib "eagle-import") (part "CAPACITOR0402_CAP"))
    )
    (comp (ref "C5")
      (value "22pF")
      (footprint "eagle-import:0402_CAP")
      (libsource (lib "eagle-import") (part "CAPACITOR0402_CAP"))
    )
    (comp (ref "C6")
      (value "22pF")
      (footprint "eagle-import:0402_CAP")
      (libsource (lib "eagle-import") (part "CAPACITOR0402_CAP"))
    )
    (comp (ref "C7")
      (value "22pF")
      (footprint "eagle-import:0402_CAP")
      (libsource (lib "eagle-import") (part "CAPACITOR0402_CAP"))
    )
    (comp (ref "C8")
      (value "22pF")
      (footprint "eagle-import:0402_CAP")
      (libsource (lib "eagle-import") (part "CAPACITOR0402_CAP"))
    )
    (comp (ref "C9")
      (value "22pF")
      (footprint "eagle-import:0402_CAP")
      (libsource (lib "eagle-import") (part "CAPACITOR0402_CAP"))
    )
    (comp (ref "C10")
      (value "22pF")
      (footprint "eagle-import:0402_CAP")
      (libsource (lib "eagle-import") (part "CAPACITOR0402_CAP"))
    )
    (comp (ref "C11")
      (value "22pF")
      (footprint "eagle-import:0402_CAP")
      (libsource (lib "eagle-import") (part "CAPACITOR0402_CAP"))
    )
    (comp (ref "C12")
      (value "22pF")
      (footprint "eagle-import:0402_CAP")
      (libsource (lib "eagle-import") (part "CAPACITOR0402_CAP"))
    )
    (comp (ref "C13")
      (value "22pF")
      (footprint "eagle-import:0402_CAP")
      (libsource (lib "eagle-import") (part "CAPACITOR0402_CAP"))
    )
    (comp (ref "C14")
      (value "22pF")
      (footprint "eagle-import:0402_CAP")
      (libsource (lib "eagle-import") (part "CAPACITOR0402_CAP"))
    )
    (comp (ref "C64")
      (value "100nF")
      (footprint "eagle-import:0603_CAP")
      (libsource (lib "eagle-import") (part "CAPACITOR0603_CAP"))
    )
    (comp (ref "C65")
      (value "100nF")
      (footprint "eagle-import:0603_CAP")
      (libsource (lib "eagle-import") (part "CAPACITOR0603_CAP"))
    )
    (comp (ref "C66")
      (value "100nF")
      (footprint "eagle-import:0603_CAP")
      (libsource (lib "eagle-import") (part "CAPACITOR0603_CAP"))
    )
    (comp (ref "C67")
      (value "100nF")
      (footprint "eagle-import:0603_CAP")
      (libsource (lib "eagle-import") (part "CAPACITOR0603_CAP"))
    )
    (comp (ref "C68")
      (value "100nF")
      (footprint "eagle-import:0603_CAP")
      (libsource (lib "eagle-import") (part "CAPACITOR0603_CAP"))
    )
    (comp (ref "C69")
      (value "100nF")
      (footprint "eagle-import:0603_CAP")
      (libsource (lib "eagle-import") (part "CAPACITOR0603_CAP"))
    )
    (comp (ref "D1")
      (value "SN75240-TSSOP")
      (footprint "eagle-import:TSSOP-8")
      (libsource (lib "eagle-import") (part "SN75240-TSSOP"))
    )
    (comp (ref "D2")
      (value "SN75240-TSSOP")
      (footprint "eagle-import:TSSOP-8")
      (libsource (lib "eagle-import") (part "SN75240-TSSOP"))
    )
    (comp (ref "D3")
      (value "SN75240-TSSOP")
      (footprint "eagle-import:TSSOP-8")
      (libsource (lib "eagle-import") (part "SN75240-TSSOP"))
    )
    (comp (ref "D4")
      (value "SN75240-TSSOP")
      (footprint "eagle-import:TSSOP-8")
      (libsource (lib "eagle-import") (part "SN75240-TSSOP"))
    )
    (comp (ref "R1")
      (value "27Ω")
      (footprint "eagle-import:0402_RES-HIGH_SPEED")
      (libsource (lib "eagle-import") (part "RESISTOR0402_RES-HIGH_SPEED"))
    )
    (comp (ref "R2")
      (value "27Ω")
      (footprint "eagle-import:0402_RES-HIGH_SPEED")
      (libsource (lib "eagle-import") (part "RESISTOR0402_RES-HIGH_SPEED"))
    )
    (comp (ref "R3")
      (value "27Ω")
      (footprint "eagle-import:0402_RES-HIGH_SPEED")
      (libsource (lib "eagle-import") (part "RESISTOR0402_RES-HIGH_SPEED"))
    )
    (comp (ref "R4")
      (value "27Ω")
      (footprint "eagle-import:0402_RES-HIGH_SPEED")
      (libsource (lib "eagle-import") (part "RESISTOR0402_RES-HIGH_SPEED"))
    )
    (comp (ref "R5")
      (value "27Ω")
      (footprint "eagle-import:0402_RES-HIGH_SPEED")
      (libsource (lib "eagle-import") (part "RESISTOR0402_RES-HIGH_SPEED"))
    )
    (comp (ref "R6")
      (value "27Ω")
      (footprint "eagle-import:0402_RES-HIGH_SPEED")
      (libsource (lib "eagle-import") (part "RESISTOR0402_RES-HIGH_SPEED"))
    )
    (comp (ref "R7")
      (value "27Ω")
      (footprint "eagle-import:0402_RES-HIGH_SPEED")
      (libsource (lib "eagle-import") (part "RESISTOR0402_RES-HIGH_SPEED"))
    )
    (comp (ref "R8")
      (value "27Ω")
      (footprint "eagle-import:0402_RES-HIGH_SPEED")
      (libsource (lib "eagle-import") (part "RESISTOR0402_RES-HIGH_SPEED"))
    )
    (comp (ref "R9")
      (value "27Ω")
      (footprint "eagle-import:0402_RES-HIGH_SPEED")
      (libsource (lib "eagle-import") (part "RESISTOR0402_RES-HIGH_SPEED"))
    )
    (comp (ref "R10")
      (value "27Ω")
      (footprint "eagle-import:0402_RES-HIGH_SPEED")
      (libsource (lib "eagle-import") (part "RESISTOR0402_RES-HIGH_SPEED"))
    )
    (comp (ref "R11")
      (value "27Ω")
      (footprint "eagle-import:0402_RES-HIGH_SPEED")
      (libsource (lib "eagle-import") (part "RESISTOR0402_RES-HIGH_SPEED"))
    )
    (comp (ref "R12")
      (value "27Ω")
      (footprint "eagle-import:0402_RES-HIGH_SPEED")
      (libsource (lib "eagle-import") (part "RESISTOR0402_RES-HIGH_SPEED"))
    )
    (comp (ref "R13")
      (value "50Ω")
      (footprint "eagle-import:0603-RES")
      (libsource (lib "eagle-import") (part "RESISTOR0603_RES"))
    )
    (comp (ref "R14")
      (value "50Ω")
      (footprint "eagle-import:0603-RES")
      (libsource (lib "eagle-import") (part "RESISTOR0603_RES"))
    )
    (comp (ref "R15")
      (value "50Ω")
      (footprint "eagle-import:0603-RES")
      (libsource (lib "eagle-import") (part "RESISTOR0603_RES"))
    )
    (comp (ref "R16")
      (value "50Ω")
      (footprint "eagle-import:0603-RES")
      (libsource (lib "eagle-import") (part "RESISTOR0603_RES"))
    )
    (comp (ref "R17")
      (value "50Ω")
      (footprint "eagle-import:0603-RES")
      (libsource (lib "eagle-import") (part "RESISTOR0603_RES"))
    )
    (comp (ref "R18")
      (value "50Ω")
      (footprint "eagle-import:0603-RES")
      (libsource (lib "eagle-import") (part "RESISTOR0603_RES"))
    )
    (comp (ref "R19")
      (value "50Ω")
      (footprint "eagle-import:0603-RES")
      (libsource (lib "eagle-import") (part "RESISTOR0603_RES"))
    )
    (comp (ref "R20")
      (value "50Ω")
      (footprint "eagle-import:0603-RES")
      (libsource (lib "eagle-import") (part "RESISTOR0603_RES"))
    )
    (comp (ref "R21")
      (value "50Ω")
      (footprint "eagle-import:0603-RES")
      (libsource (lib "eagle-import") (part "RESISTOR0603_RES"))
    )
    (comp (ref "R22")
      (value "50Ω")
      (footprint "eagle-import:0603-RES")
      (libsource (lib "eagle-import") (part "RESISTOR0603_RES"))
    )
    (comp (ref "R23")
      (value "50Ω")
      (footprint "eagle-import:0603-RES")
      (libsource (lib "eagle-import") (part "RESISTOR0603_RES"))
    )
    (comp (ref "R24")
      (value "50Ω")
      (footprint "eagle-import:0603-RES")
      (libsource (lib "eagle-import") (part "RESISTOR0603_RES"))
    )
    (comp (ref "R52")
      (value "15kΩ")
      (footprint "eagle-import:0603-RES")
      (libsource (lib "eagle-import") (part "RESISTOR0603_RES"))
    )
    (comp (ref "R53")
      (value "15kΩ")
      (footprint "eagle-import:0603-RES")
      (libsource (lib "eagle-import") (part "RESISTOR0603_RES"))
    )
    (comp (ref "R54")
      (value "15kΩ")
      (footprint "eagle-import:0603-RES")
      (libsource (lib "eagle-import") (part "RESISTOR0603_RES"))
    )
    (comp (ref "R55")
      (value "15kΩ")
      (footprint "eagle-import:0603-RES")
      (libsource (lib "eagle-import") (part "RESISTOR0603_RES"))
    )
    (comp (ref "R56")
      (value "15kΩ")
      (footprint "eagle-import:0603-RES")
      (libsource (lib "eagle-import") (part "RESISTOR0603_RES"))
    )
    (comp (ref "R57")
      (value "15kΩ")
      (footprint "eagle-import:0603-RES")
      (libsource (lib "eagle-import") (part "RESISTOR0603_RES"))
    )
    (comp (ref "R58")
      (value "15kΩ")
      (footprint "eagle-import:0603-RES")
      (libsource (lib "eagle-import") (part "RESISTOR0603_RES"))
    )
    (comp (ref "R59")
      (value "15kΩ")
      (footprint "eagle-import:0603-RES")
      (libsource (lib "eagle-import") (part "RESISTOR0603_RES"))
    )
    (comp (ref "R60")
      (value "15kΩ")
      (footprint "eagle-import:0603-RES")
      (libsource (lib "eagle-import") (part "RESISTOR0603_RES"))
    )
    (comp (ref "R61")
      (value "15kΩ")
      (footprint "eagle-import:0603-RES")
      (libsource (lib "eagle-import") (part "RESISTOR0603_RES"))
    )
    (comp (ref "R62")
      (value "15kΩ")
      (footprint "eagle-import:0603-RES")
      (libsource (lib "eagle-import") (part "RESISTOR0603_RES"))
    )
    (comp (ref "R63")
      (value "15kΩ")
      (footprint "eagle-import:0603-RES")
      (libsource (lib "eagle-import") (part "RESISTOR0603_RES"))
    )
    (comp (ref "U20")
      (value "TS3USB30E")
      (footprint "eagle-import:UQFN-10")
      (libsource (lib "eagle-import") (part "TS3USB30E"))
    )
    (comp (ref "U21")
      (value "TS3USB30E")
      (footprint "eagle-import:UQFN-10")
      (libsource (lib "eagle-import") (part "TS3USB30E"))
    )
    (comp (ref "U22")
      (value "TS3USB30E")
      (footprint "eagle-import:UQFN-10")
      (libsource (lib "eagle-import") (part "TS3USB30E"))
    )
    (comp (ref "U23")
      (value "TS3USB30E")
      (footprint "eagle-import:UQFN-10")
      (libsource (lib "eagle-import") (part "TS3USB30E"))
    )
    (comp (ref "U24")
      (value "TS3USB30E")
      (footprint "eagle-import:UQFN-10")
      (libsource (lib "eagle-import") (part "TS3USB30E"))
    )
    (comp (ref "U25")
      (value "TS3USB30E")
      (footprint "eagle-import:UQFN-10")
      (libsource (lib "eagle-import") (part "TS3USB30E"))
    )
    (comp (ref "LED1001")
      (value "LED0603")
      (footprint "eagle-import:LED-0603")
      (libsource (lib "eagle-import") (part "LED0603"))
    )
    (comp (ref "LED1002")
      (value "LED0603")
      (footprint "eagle-import:LED-0603")
      (libsource (lib "eagle-import") (part "LED0603"))
    )
    (comp (ref "LED1003")
      (value "LED0603")
      (footprint "eagle-import:LED-0603")
      (libsource (lib "eagle-import") (part "LED0603"))
    )
    (comp (ref "LED1004")
      (value "LED0603")
      (footprint "eagle-import:LED-0603")
      (libsource (lib "eagle-import") (part "LED0603"))
    )
    (comp (ref "LED1005")
      (value "LED0603")
      (footprint "eagle-import:LED-0603")
      (libsource (lib "eagle-import") (part "LED0603"))
    )
    (comp (ref "LED1006")
      (value "LED0603")
      (footprint "eagle-import:LED-0603")
      (libsource (lib "eagle-import") (part "LED0603"))
    )
    (comp (ref "LED1007")
      (value "LED0603")
      (footprint "eagle-import:LED-0603")
      (libsource (lib "eagle-import") (part "LED0603"))
    )
    (comp (ref "LED1008")
      (value "LED0603")
      (footprint "eagle-import:LED-0603")
      (libsource (lib "eagle-import") (part "LED0603"))
    )
    (comp (ref "LED1009")
      (value "LED0603")
      (footprint "eagle-import:LED-0603")
      (libsource (lib "eagle-import") (part "LED0603"))
    )
    (comp (ref "LED1010")
      (value "LED0603")
      (footprint "eagle-import:LED-0603")
      (libsource (lib "eagle-import") (part "LED0603"))
    )
    (comp (ref "LED1011")
      (value "LED0603")
      (footprint "eagle-import:LED-0603")
      (libsource (lib "eagle-import") (part "LED0603"))
    )
    (comp (ref "LED1012")
      (value "LED0603")
      (footprint "eagle-import:LED-0603")
      (libsource (lib "eagle-import") (part "LED0603"))
    )
    (comp (ref "LED1013")
      (value "LED0603")
      (footprint "eagle-import:LED-0603")
      (libsource (lib "eagle-import") (part "LED0603"))
    )
    (comp (ref "LED1014")
      (value "LED0603")
      (footprint "eagle-import:LED-0603")
      (libsource (lib "eagle-import") (part "LED0603"))
    )
    (comp (ref "LED1015")
      (value "LED0603")
      (footprint "eagle-import:LED-0603")
      (libsource (lib "eagle-import") (part "LED0603"))
    )
    (comp (ref "LED1016")
      (value "LED0603")
      (footprint "eagle-import:LED-0603")
      (libsource (lib "eagle-import") (part "LED0603"))
    )
    (comp (ref "LED1017")
      (value "LED0603")
      (footprint "eagle-import:LED-0603")
      (libsource (lib "eagle-import") (part "LED0603"))
    )
    (comp (ref "LED1018")
      (value "LED0603")
      (footprint "eagle-import:LED-0603")
      (libsource (lib "eagle-import") (part "LED0603"))
    )
    (comp (ref "R1001")
      (value "15Ω")
      (footprint "eagle-import:0603-RES")
      (libsource (lib "eagle-import") (part "RESISTOR0603_RES"))
    )
    (comp (ref "R1002")
      (value "15Ω")
      (footprint "eagle-import:0603-RES")
      (libsource (lib "eagle-import") (part "RESISTOR0603_RES"))
    )
    (comp (ref "R1003")
      (value "15Ω")
      (footprint "eagle-import:0603-RES")
      (libsource (lib "eagle-import") (part "RESISTOR0603_RES"))
    )
    (comp (ref "R1004")
      (value "15Ω")
      (footprint "eagle-import:0603-RES")
      (libsource (lib "eagle-import") (part "RESISTOR0603_RES"))
    )
    (comp (ref "R1005")
      (value "15Ω")
      (footprint "eagle-import:0603-RES")
      (libsource (lib "eagle-import") (part "RESISTOR0603_RES"))
    )
    (comp (ref "R1006")
      (value "15Ω")
      (footprint "eagle-import:0603-RES")
      (libsource (lib "eagle-import") (part "RESISTOR0603_RES"))
    )
    (comp (ref "R1007")
      (value "15Ω")
      (footprint "eagle-import:0603-RES")
      (libsource (lib "eagle-import") (part "RESISTOR0603_RES"))
    )
    (comp (ref "R1008")
      (value "15Ω")
      (footprint "eagle-import:0603-RES")
      (libsource (lib "eagle-import") (part "RESISTOR0603_RES"))
    )
    (comp (ref "R1009")
      (value "15Ω")
      (footprint "eagle-import:0603-RES")
      (libsource (lib "eagle-import") (part "RESISTOR0603_RES"))
    )
    (comp (ref "R1010")
      (value "15Ω")
      (footprint "eagle-import:0603-RES")
      (libsource (lib "eagle-import") (part "RESISTOR0603_RES"))
    )
    (comp (ref "R1011")
      (value "15Ω")
      (footprint "eagle-import:0603-RES")
      (libsource (lib "eagle-import") (part "RESISTOR0603_RES"))
    )
    (comp (ref "R1012")
      (value "15Ω")
      (footprint "eagle-import:0603-RES")
      (libsource (lib "eagle-import") (part "RESISTOR0603_RES"))
    )
    (comp (ref "R1013")
      (value "15Ω")
      (footprint "eagle-import:0603-RES")
      (libsource (lib "eagle-import") (part "RESISTOR0603_RES"))
    )
    (comp (ref "R1014")
      (value "15Ω")
      (footprint "eagle-import:0603-RES")
      (libsource (lib "eagle-import") (part "RESISTOR0603_RES"))
    )
    (comp (ref "R1015")
      (value "15Ω")
      (footprint "eagle-import:0603-RES")
      (libsource (lib "eagle-import") (part "RESISTOR0603_RES"))
    )
    (comp (ref "R1016")
      (value "15Ω")
      (footprint "eagle-import:0603-RES")
      (libsource (lib "eagle-import") (part "RESISTOR0603_RES"))
    )
    (comp (ref "R1017")
      (value "15Ω")
      (footprint "eagle-import:0603-RES")
      (libsource (lib "eagle-import") (part "RESISTOR0603_RES"))
    )
    (comp (ref "R1018")
      (value "15Ω")
      (footprint "eagle-import:0603-RES")
      (libsource (lib "eagle-import") (part "RESISTOR0603_RES"))
    )
    (comp (ref "TP1")
      (value "TEST_POINT_0.040IN")
      (footprint "eagle-import:TESTPOINT_0.040IN")
      (libsource (lib "eagle-import") (part "TEST_POINT_0.040IN"))
    )
    (comp (ref "TP2")
      (value "TEST_POINT_0.040IN")
      (footprint "eagle-import:TESTPOINT_0.040IN")
      (libsource (lib "eagle-import") (part "TEST_POINT_0.040IN"))
    )
    (comp (ref "TP3")
      (value "TEST_POINT_0.040IN")
      (footprint "eagle-import:TESTPOINT_0.040IN")
      (libsource (lib "eagle-import") (part "TEST_POINT_0.040IN"))
    )
    (comp (ref "TP4")
      (value "TEST_POINT_0.040IN")
      (footprint "eagle-import:TESTPOINT_0.040IN")
      (libsource (lib "eagle-import") (part "TEST_POINT_0.040IN"))
    )
    (comp (ref "TP5")
      (value "TEST_POINT_0.040IN")
      (footprint "eagle-import:TESTPOINT_0.040IN")
      (libsource (lib "eagle-import") (part "TEST_POINT_0.040IN"))
    )
    (comp (ref "TP6")
      (value "TEST_POINT_0.040IN")
      (footprint "eagle-import:TESTPOINT_0.040IN")
      (libsource (lib "eagle-import") (part "TEST_POINT_0.040IN"))
    )
    (comp (ref "TP7")
      (value "TEST_POINT_0.040IN")
      (footprint "eagle-import:TESTPOINT_0.040IN")
      (libsource (lib "eagle-import") (part "TEST_POINT_0.040IN"))
    )
    (comp (ref "TP8")
      (value "TEST_POINT_0.040IN")
      (footprint "eagle-import:TESTPOINT_0.040IN")
      (libsource (lib "eagle-import") (part "TEST_POINT_0.040IN"))
    )
    (comp (ref "TP9")
      (value "TEST_POINT_0.040IN")
      (footprint "eagle-import:TESTPOINT_0.040IN")
      (libsource (lib "eagle-import") (part "TEST_POINT_0.040IN"))
    )
    (comp (ref "TP10")
      (value "TEST_POINT_0.040IN")
      (footprint "eagle-import:TESTPOINT_0.040IN")
      (libsource (lib "eagle-import") (part "TEST_POINT_0.040IN"))
    )
    (comp (ref "TP11")
      (value "TEST_POINT_0.040IN")
      (footprint "eagle-import:TESTPOINT_0.040IN")
      (libsource (lib "eagle-import") (part "TEST_POINT_0.040IN"))
    )
    (comp (ref "TP12")
      (value "TEST_POINT_0.040IN")
      (footprint "eagle-import:TESTPOINT_0.040IN")
      (libsource (lib "eagle-import") (part "TEST_POINT_0.040IN"))
    )
    (comp (ref "TP13")
      (value "TEST_POINT_0.040IN")
      (footprint "eagle-import:TESTPOINT_0.040IN")
      (libsource (lib "eagle-import") (part "TEST_POINT_0.040IN"))
    )
    (comp (ref "TP14")
      (value "TEST_POINT_0.040IN")
      (footprint "eagle-import:TESTPOINT_0.040IN")
      (libsource (lib "eagle-import") (part "TEST_POINT_0.040IN"))
    )
    (comp (ref "TP15")
      (value "TEST_POINT_0.040IN")
      (footprint "eagle-import:TESTPOINT_0.040IN")
      (libsource (lib "eagle-import") (part "TEST_POINT_0.040IN"))
    )
    (comp (ref "TP16")
      (value "TEST_POINT_0.040IN")
      (footprint "eagle-import:TESTPOINT_0.040IN")
      (libsource (lib "eagle-import") (part "TEST_POINT_0.040IN"))
    )
    (comp (ref "TP17")
      (value "TEST_POINT_0.040IN")
      (footprint "eagle-import:TESTPOINT_0.040IN")
      (libsource (lib "eagle-import") (part "TEST_POINT_0.040IN"))
    )
    (comp (ref "TP18")
      (value "TEST_POINT_0.040IN")
      (footprint "eagle-import:TESTPOINT_0.040IN")
      (libsource (lib "eagle-import") (part "TEST_POINT_0.040IN"))
    )
    (comp (ref "TP19")
      (value "TEST_POINT_0.040IN")
      (footprint "eagle-import:TESTPOINT_0.040IN")
      (libsource (lib "eagle-import") (part "TEST_POINT_0.040IN"))
    )
    (comp (ref "TP20")
      (value "TEST_POINT_0.040IN")
      (footprint "eagle-import:TESTPOINT_0.040IN")
      (libsource (lib "eagle-import") (part "TEST_POINT_0.040IN"))
    )
    (comp (ref "TP21")
      (value "TEST_POINT_0.040IN")
      (footprint "eagle-import:TESTPOINT_0.040IN")
      (libsource (lib "eagle-import") (part "TEST_POINT_0.040IN"))
    )
    (comp (ref "TP22")
      (value "TEST_POINT_0.040IN")
      (footprint "eagle-import:TESTPOINT_0.040IN")
      (libsource (lib "eagle-import") (part "TEST_POINT_0.040IN"))
    )
    (comp (ref "TP23")
      (value "TEST_POINT_0.040IN")
      (footprint "eagle-import:TESTPOINT_0.040IN")
      (libsource (lib "eagle-import") (part "TEST_POINT_0.040IN"))
    )
    (comp (ref "TP24")
      (value "TEST_POINT_0.040IN")
      (footprint "eagle-import:TESTPOINT_0.040IN")
      (libsource (lib "eagle-import") (part "TEST_POINT_0.040IN"))
    )
    (comp (ref "TP25")
      (value "TEST_POINT_0.040IN")
      (footprint "eagle-import:TESTPOINT_0.040IN")
      (libsource (lib "eagle-import") (part "TEST_POINT_0.040IN"))
    )
    (comp (ref "TP26")
      (value "TEST_POINT_0.040IN")
      (footprint "eagle-import:TESTPOINT_0.040IN")
      (libsource (lib "eagle-import") (part "TEST_POINT_0.040IN"))
    )
    (comp (ref "TP27")
      (value "TEST_POINT_0.040IN")
      (footprint "eagle-import:TESTPOINT_0.040IN")
      (libsource (lib "eagle-import") (part "TEST_POINT_0.040IN"))
    )
    (comp (ref "TP28")
      (value "TEST_POINT_0.040IN")
      (footprint "eagle-import:TESTPOINT_0.040IN")
      (libsource (lib "eagle-import") (part "TEST_POINT_0.040IN"))
    )
    (comp (ref "TP29")
      (value "TEST_POINT_0.040IN")
      (footprint "eagle-import:TESTPOINT_0.040IN")
      (libsource (lib "eagle-import") (part "TEST_POINT_0.040IN"))
    )
    (comp (ref "TP30")
      (value "TEST_POINT_0.040IN")
      (footprint "eagle-import:TESTPOINT_0.040IN")
      (libsource (lib "eagle-import") (part "TEST_POINT_0.040IN"))
    )
    (comp (ref "TP31")
      (value "TEST_POINT_0.040IN")
      (footprint "eagle-import:TESTPOINT_0.040IN")
      (libsource (lib "eagle-import") (part "TEST_POINT_0.040IN"))
    )
    (comp (ref "TP32")
      (value "TEST_POINT_0.040IN")
      (footprint "eagle-import:TESTPOINT_0.040IN")
      (libsource (lib "eagle-import") (part "TEST_POINT_0.040IN"))
    )
    (comp (ref "TP33")
      (value "TEST_POINT_0.040IN")
      (footprint "eagle-import:TESTPOINT_0.040IN")
      (libsource (lib "eagle-import") (part "TEST_POINT_0.040IN"))
    )
    (comp (ref "TP34")
      (value "TEST_POINT_0.040IN")
      (footprint "eagle-import:TESTPOINT_0.040IN")
      (libsource (lib "eagle-import") (part "TEST_POINT_0.040IN"))
    )
    (comp (ref "TP35")
      (value "TEST_POINT_0.040IN")
      (footprint "eagle-import:TESTPOINT_0.040IN")
      (libsource (lib "eagle-import") (part "TEST_POINT_0.040IN"))
    )
    (comp (ref "TP36")
      (value "TEST_POINT_0.040IN")
      (footprint "eagle-import:TESTPOINT_0.040IN")
      (libsource (lib "eagle-import") (part "TEST_POINT_0.040IN"))
    )
    (comp (ref "TP37")
      (value "TEST_POINT_0.040IN")
      (footprint "eagle-import:TESTPOINT_0.040IN")
      (libsource (lib "eagle-import") (part "TEST_POINT_0.040IN"))
    )
    (comp (ref "TP38")
      (value "TEST_POINT_0.040IN")
      (footprint "eagle-import:TESTPOINT_0.040IN")
      (libsource (lib "eagle-import") (part "TEST_POINT_0.040IN"))
    )
    (comp (ref "TP39")
      (value "TEST_POINT_0.040IN")
      (footprint "eagle-import:TESTPOINT_0.040IN")
      (libsource (lib "eagle-import") (part "TEST_POINT_0.040IN"))
    )
    (comp (ref "TP40")
      (value "TEST_POINT_0.040IN")
      (footprint "eagle-import:TESTPOINT_0.040IN")
      (libsource (lib "eagle-import") (part "TEST_POINT_0.040IN"))
    )
    (comp (ref "TP41")
      (value "TEST_POINT_0.040IN")
      (footprint "eagle-import:TESTPOINT_0.040IN")
      (libsource (lib "eagle-import") (part "TEST_POINT_0.040IN"))
    )
    (comp (ref "TP42")
      (value "TEST_POINT_0.040IN")
      (footprint "eagle-import:TESTPOINT_0.040IN")
      (libsource (lib "eagle-import") (part "TEST_POINT_0.040IN"))
    )
    (comp (ref "TP43")
      (value "TEST_POINT_0.040IN")
      (footprint "eagle-import:TESTPOINT_0.040IN")
      (libsource (lib "eagle-import") (part "TEST_POINT_0.040IN"))
    )
    (comp (ref "TP1001")
      (value "TEST_POINT_0.040IN")
      (footprint "eagle-import:TESTPOINT_0.040IN")
      (libsource (lib "eagle-import") (part "TEST_POINT_0.040IN"))
    )
    (comp (ref "TP1002")
      (value "TEST_POINT_0.040IN")
      (footprint "eagle-import:TESTPOINT_0.040IN")
      (libsource (lib "eagle-import") (part "TEST_POINT_0.040IN"))
    )
    (comp (ref "TP1003")
      (value "TEST_POINT_0.040IN")
      (footprint "eagle-import:TESTPOINT_0.040IN")
      (libsource (lib "eagle-import") (part "TEST_POINT_0.040IN"))
    )
    (comp (ref "TP1004")
      (value "TEST_POINT_0.040IN")
      (footprint "eagle-import:TESTPOINT_0.040IN")
      (libsource (lib "eagle-import") (part "TEST_POINT_0.040IN"))
    )
    (comp (ref "TP1005")
      (value "TEST_POINT_0.040IN")
      (footprint "eagle-import:TESTPOINT_0.040IN")
      (libsource (lib "eagle-import") (part "TEST_POINT_0.040IN"))
    )
    (comp (ref "TP1006")
      (value "TEST_POINT_0.040IN")
      (footprint "eagle-import:TESTPOINT_0.040IN")
      (libsource (lib "eagle-import") (part "TEST_POINT_0.040IN"))
    )
    (comp (ref "TP1007")
      (value "TEST_POINT_0.040IN")
      (footprint "eagle-import:TESTPOINT_0.040IN")
      (libsource (lib "eagle-import") (part "TEST_POINT_0.040IN"))
    )
    (comp (ref "TP1008")
      (value "TEST_POINT_0.040IN")
      (footprint "eagle-import:TESTPOINT_0.040IN")
      (libsource (lib "eagle-import") (part "TEST_POINT_0.040IN"))
    )
    (comp (ref "TP1009")
      (value "TEST_POINT_0.040IN")
      (footprint "eagle-import:TESTPOINT_0.040IN")
      (libsource (lib "eagle-import") (part "TEST_POINT_0.040IN"))
    )
    (comp (ref "TP1010")
      (value "TEST_POINT_0.040IN")
      (footprint "eagle-import:TESTPOINT_0.040IN")
      (libsource (lib "eagle-import") (part "TEST_POINT_0.040IN"))
    )
    (comp (ref "TP1011")
      (value "TEST_POINT_0.040IN")
      (footprint "eagle-import:TESTPOINT_0.040IN")
      (libsource (lib "eagle-import") (part "TEST_POINT_0.040IN"))
    )
    (comp (ref "TP1012")
      (value "TEST_POINT_0.040IN")
      (footprint "eagle-import:TESTPOINT_0.040IN")
      (libsource (lib "eagle-import") (part "TEST_POINT_0.040IN"))
    )
    (comp (ref "TP1013")
      (value "TEST_POINT_0.040IN")
      (footprint "eagle-import:TESTPOINT_0.040IN")
      (libsource (lib "eagle-import") (part "TEST_POINT_0.040IN"))
    )
    (comp (ref "TP1014")
      (value "TEST_POINT_0.040IN")
      (footprint "eagle-import:TESTPOINT_0.040IN")
      (libsource (lib "eagle-import") (part "TEST_POINT_0.040IN"))
    )
    (comp (ref "TP1015")
      (value "TEST_POINT_0.040IN")
      (footprint "eagle-import:TESTPOINT_0.040IN")
      (libsource (lib "eagle-import") (part "TEST_POINT_0.040IN"))
    )
    (comp (ref "TP1016")
      (value "TEST_POINT_0.040IN")
      (footprint "eagle-import:TESTPOINT_0.040IN")
      (libsource (lib "eagle-import") (part "TEST_POINT_0.040IN"))
    )
    (comp (ref "TP1017")
      (value "TEST_POINT_0.040IN")
      (footprint "eagle-import:TESTPOINT_0.040IN")
      (libsource (lib "eagle-import") (part "TEST_POINT_0.040IN"))
    )
    (comp (ref "TP1018")
      (value "TEST_POINT_0.040IN")
      (footprint "eagle-import:TESTPOINT_0.040IN")
      (libsource (lib "eagle-import") (part "TEST_POINT_0.040IN"))
    )
    (comp (ref "C15")
      (value "100nF")
      (footprint "eagle-import:0603_CAP")
      (libsource (lib "eagle-import") (part "CAPACITOR0603_CAP"))
    )
    (comp (ref "C16")
      (value "100nF")
      (footprint "eagle-import:0603_CAP")
      (libsource (lib "eagle-import") (part "CAPACITOR0603_CAP"))
    )
    (comp (ref "C17")
      (value "100nF")
      (footprint "eagle-import:0603_CAP")
      (libsource (lib "eagle-import") (part "CAPACITOR0603_CAP"))
    )
    (comp (ref "C18")
      (value "100nF")
      (footprint "eagle-import:0603_CAP")
      (libsource (lib "eagle-import") (part "CAPACITOR0603_CAP"))
    )
    (comp (ref "C19")
      (value "100nF")
      (footprint "eagle-import:0603_CAP")
      (libsource (lib "eagle-import") (part "CAPACITOR0603_CAP"))
    )
    (comp (ref "C20")
      (value "100nF")
      (footprint "eagle-import:0603_CAP")
      (libsource (lib "eagle-import") (part "CAPACITOR0603_CAP"))
    )
    (comp (ref "R66")
      (value "10MΩ")
      (footprint "eagle-import:0603-RES")
      (libsource (lib "eagle-import") (part "RESISTOR0603_RES"))
    )
    (comp (ref "R67")
      (value "10MΩ")
      (footprint "eagle-import:0603-RES")
      (libsource (lib "eagle-import") (part "RESISTOR0603_RES"))
    )
    (comp (ref "R68")
      (value "10MΩ")
      (footprint "eagle-import:0603-RES")
      (libsource (lib "eagle-import") (part "RESISTOR0603_RES"))
    )
    (comp (ref "R69")
      (value "10MΩ")
      (footprint "eagle-import:0603-RES")
      (libsource (lib "eagle-import") (part "RESISTOR0603_RES"))
    )
    (comp (ref "R70")
      (value "10MΩ")
      (footprint "eagle-import:0603-RES")
      (libsource (lib "eagle-import") (part "RESISTOR0603_RES"))
    )
    (comp (ref "R71")
      (value "10MΩ")
      (footprint "eagle-import:0603-RES")
      (libsource (lib "eagle-import") (part "RESISTOR0603_RES"))
    )
    (comp (ref "R72")
      (value "10MΩ")
      (footprint "eagle-import:0603-RES")
      (libsource (lib "eagle-import") (part "RESISTOR0603_RES"))
    )
    (comp (ref "R73")
      (value "10MΩ")
      (footprint "eagle-import:0603-RES")
      (libsource (lib "eagle-import") (part "RESISTOR0603_RES"))
    )
    (comp (ref "R74")
      (value "10MΩ")
      (footprint "eagle-import:0603-RES")
      (libsource (lib "eagle-import") (part "RESISTOR0603_RES"))
    )
    (comp (ref "R75")
      (value "10MΩ")
      (footprint "eagle-import:0603-RES")
      (libsource (lib "eagle-import") (part "RESISTOR0603_RES"))
    )
    (comp (ref "R76")
      (value "10MΩ")
      (footprint "eagle-import:0603-RES")
      (libsource (lib "eagle-import") (part "RESISTOR0603_RES"))
    )
    (comp (ref "R77")
      (value "10MΩ")
      (footprint "eagle-import:0603-RES")
      (libsource (lib "eagle-import") (part "RESISTOR0603_RES"))
    )
    (comp (ref "R78")
      (value "10MΩ")
      (footprint "eagle-import:0603-RES")
      (libsource (lib "eagle-import") (part "RESISTOR0603_RES"))
    )
    (comp (ref "R79")
      (value "10MΩ")
      (footprint "eagle-import:0603-RES")
      (libsource (lib "eagle-import") (part "RESISTOR0603_RES"))
    )
    (comp (ref "R80")
      (value "10MΩ")
      (footprint "eagle-import:0603-RES")
      (libsource (lib "eagle-import") (part "RESISTOR0603_RES"))
    )
    (comp (ref "R81")
      (value "10MΩ")
      (footprint "eagle-import:0603-RES")
      (libsource (lib "eagle-import") (part "RESISTOR0603_RES"))
    )
    (comp (ref "R82")
      (value "10MΩ")
      (footprint "eagle-import:0603-RES")
      (libsource (lib "eagle-import") (part "RESISTOR0603_RES"))
    )
    (comp (ref "R83")
      (value "10MΩ")
      (footprint "eagle-import:0603-RES")
      (libsource (lib "eagle-import") (part "RESISTOR0603_RES"))
    )
    (comp (ref "U26")
      (value "MCP23008")
      (footprint "eagle-import:SOIC-18")
      (libsource (lib "eagle-import") (part "MCP23008"))
    )
    (comp (ref "U27")
      (value "MCP23008")
      (footprint "eagle-import:SOIC-18")
      (libsource (lib "eagle-import") (part "MCP23008"))
    )
    (comp (ref "U28")
      (value "MCP23008")
      (footprint "eagle-import:SOIC-18")
      (libsource (lib "eagle-import") (part "MCP23008"))
    )
    (comp (ref "U29")
      (value "MCP23008")
      (footprint "eagle-import:SOIC-18")
      (libsource (lib "eagle-import") (part "MCP23008"))
    )
    (comp (ref "U30")
      (value "MCP23008")
      (footprint "eagle-import:SOIC-18")
      (libsource (lib "eagle-import") (part "MCP23008"))
    )
    (comp (ref "U31")
      (value "MCP23008")
      (footprint "eagle-import:SOIC-18")
      (libsource (lib "eagle-import") (part "MCP23008"))
    )
    (comp (ref "C39")
      (value "100nF")
      (footprint "eagle-import:0603_CAP")
      (libsource (lib "eagle-import") (part "CAPACITOR0603_CAP"))
    )
    (comp (ref "C40")
      (value "100nF")
      (footprint "eagle-import:0603_CAP")
      (libsource (lib "eagle-import") (part "CAPACITOR0603_CAP"))
    )
    (comp (ref "C41")
      (value "100nF")
      (footprint "eagle-import:0603_CAP")
      (libsource (lib "eagle-import") (part "CAPACITOR0603_CAP"))
    )
    (comp (ref "C42")
      (value "100nF")
      (footprint "eagle-import:0603_CAP")
      (libsource (lib "eagle-import") (part "CAPACITOR0603_CAP"))
    )
    (comp (ref "C43")
      (value "100nF")
      (footprint "eagle-import:0603_CAP")
      (libsource (lib "eagle-import") (part "CAPACITOR0603_CAP"))
    )
    (comp (ref "C44")
      (value "100nF")
      (footprint "eagle-import:0603_CAP")
      (libsource (lib "eagle-import") (part "CAPACITOR0603_CAP"))
    )
    (comp (ref "C45")
      (value "100nF")
      (footprint "eagle-import:0603_CAP")
      (libsource (lib "eagle-import") (part "CAPACITOR0603_CAP"))
    )
    (comp (ref "C46")
      (value "100nF")
      (footprint "eagle-import:0603_CAP")
      (libsource (lib "eagle-import") (part "CAPACITOR0603_CAP"))
    )
    (comp (ref "C47")
      (value "100nF")
      (footprint "eagle-import:0603_CAP")
      (libsource (lib "eagle-import") (part "CAPACITOR0603_CAP"))
    )
    (comp (ref "C48")
      (value "100nF")
      (footprint "eagle-import:0603_CAP")
      (libsource (lib "eagle-import") (part "CAPACITOR0603_CAP"))
    )
    (comp (ref "C49")
      (value "100nF")
      (footprint "eagle-import:0603_CAP")
      (libsource (lib "eagle-import") (part "CAPACITOR0603_CAP"))
    )
    (comp (ref "C50")
      (value "100nF")
      (footprint "eagle-import:0603_CAP")
      (libsource (lib "eagle-import") (part "CAPACITOR0603_CAP"))
    )
    (comp (ref "C51")
      (value "100nF")
      (footprint "eagle-import:0603_CAP")
      (libsource (lib "eagle-import") (part "CAPACITOR0603_CAP"))
    )
    (comp (ref "C52")
      (value "100nF")
      (footprint "eagle-import:0603_CAP")
      (libsource (lib "eagle-import") (part "CAPACITOR0603_CAP"))
    )
    (comp (ref "C53")
      (value "100nF")
      (footprint "eagle-import:0603_CAP")
      (libsource (lib "eagle-import") (part "CAPACITOR0603_CAP"))
    )
    (comp (ref "C54")
      (value "100nF")
      (footprint "eagle-import:0603_CAP")
      (libsource (lib "eagle-import") (part "CAPACITOR0603_CAP"))
    )
    (comp (ref "C55")
      (value "100nF")
      (footprint "eagle-import:0603_CAP")
      (libsource (lib "eagle-import") (part "CAPACITOR0603_CAP"))
    )
    (comp (ref "C56")
      (value "100nF")
      (footprint "eagle-import:0603_CAP")
      (libsource (lib "eagle-import") (part "CAPACITOR0603_CAP"))
    )
    (comp (ref "C57")
      (value "100nF")
      (footprint "eagle-import:0603_CAP")
      (libsource (lib "eagle-import") (part "CAPACITOR0603_CAP"))
    )
    (comp (ref "C58")
      (value "100nF")
      (footprint "eagle-import:0603_CAP")
      (libsource (lib "eagle-import") (part "CAPACITOR0603_CAP"))
    )
    (comp (ref "C59")
      (value "100nF")
      (footprint "eagle-import:0603_CAP")
      (libsource (lib "eagle-import") (part "CAPACITOR0603_CAP"))
    )
    (comp (ref "C60")
      (value "100nF")
      (footprint "eagle-import:0603_CAP")
      (libsource (lib "eagle-import") (part "CAPACITOR0603_CAP"))
    )
    (comp (ref "C61")
      (value "100nF")
      (footprint "eagle-import:0603_CAP")
      (libsource (lib "eagle-import") (part "CAPACITOR0603_CAP"))
    )
    (comp (ref "C62")
      (value "100nF")
      (footprint "eagle-import:0603_CAP")
      (libsource (lib "eagle-import") (part "CAPACITOR0603_CAP"))
    )
    (comp (ref "U8")
      (value "SN74LVC2T45")
      (footprint "eagle-import:VFSOP-8")
      (libsource (lib "eagle-import") (part "SN74LVC2T45"))
    )
    (comp (ref "U9")
      (value "SN74LVC2T45")
      (footprint "eagle-import:VFSOP-8")
      (libsource (lib "eagle-import") (part "SN74LVC2T45"))
    )
    (comp (ref "U10")
      (value "SN74LVC2T45")
      (footprint "eagle-import:VFSOP-8")
      (libsource (lib "eagle-import") (part "SN74LVC2T45"))
    )
    (comp (ref "U11")
      (value "SN74LVC2T45")
      (footprint "eagle-import:VFSOP-8")
      (libsource (lib "eagle-import") (part "SN74LVC2T45"))
    )
    (comp (ref "U12")
      (value "SN74LVC2T45")
      (footprint "eagle-import:VFSOP-8")
      (libsource (lib "eagle-import") (part "SN74LVC2T45"))
    )
    (comp (ref "U13")
      (value "SN74LVC2T45")
      (footprint "eagle-import:VFSOP-8")
      (libsource (lib "eagle-import") (part "SN74LVC2T45"))
    )
    (comp (ref "U14")
      (value "SN74LVC2T45")
      (footprint "eagle-import:VFSOP-8")
      (libsource (lib "eagle-import") (part "SN74LVC2T45"))
    )
    (comp (ref "U15")
      (value "SN74LVC2T45")
      (footprint "eagle-import:VFSOP-8")
      (libsource (lib "eagle-import") (part "SN74LVC2T45"))
    )
    (comp (ref "U16")
      (value "SN74LVC2T45")
      (footprint "eagle-import:VFSOP-8")
      (libsource (lib "eagle-import") (part "SN74LVC2T45"))
    )
    (comp (ref "U17")
      (value "SN74LVC2T45")
      (footprint "eagle-import:VFSOP-8")
      (libsource (lib "eagle-import") (part "SN74LVC2T45"))
    )
    (comp (ref "U18")
      (value "SN74LVC2T45")
      (footprint "eagle-import:VFSOP-8")
      (libsource (lib "eagle-import") (part "SN74LVC2T45"))
    )
    (comp (ref "U19")
      (value "SN74LVC2T45")
      (footprint "eagle-import:VFSOP-8")
      (libsource (lib "eagle-import") (part "SN74LVC2T45"))
    )
    (comp (ref "J0")
      (value "BACKPLANE_GENERIC_MODULE")
      (footprint "eagle-import:BACKPLANE_MODULE_14PIN")
      (libsource (lib "eagle-import") (part "BACKPLANE_GENERIC_MODULE"))
    )
    (comp (ref "J1")
      (value "BACKPLANE_GENERIC_MODULE")
      (footprint "eagle-import:BACKPLANE_MODULE_14PIN")
      (libsource (lib "eagle-import") (part "BACKPLANE_GENERIC_MODULE"))
    )
    (comp (ref "J2")
      (value "BACKPLANE_GENERIC_MODULE")
      (footprint "eagle-import:BACKPLANE_MODULE_14PIN")
      (libsource (lib "eagle-import") (part "BACKPLANE_GENERIC_MODULE"))
    )
    (comp (ref "J5")
      (value "BACKPLANE_GENERIC_MODULE")
      (footprint "eagle-import:BACKPLANE_MODULE_14PIN")
      (libsource (lib "eagle-import") (part "BACKPLANE_GENERIC_MODULE"))
    )
    (comp (ref "J6")
      (value "BACKPLANE_GENERIC_MODULE")
      (footprint "eagle-import:BACKPLANE_MODULE_14PIN")
      (libsource (lib "eagle-import") (part "BACKPLANE_GENERIC_MODULE"))
    )
    (comp (ref "J7")
      (value "BACKPLANE_GENERIC_MODULE")
      (footprint "eagle-import:BACKPLANE_MODULE_14PIN")
      (libsource (lib "eagle-import") (part "BACKPLANE_GENERIC_MODULE"))
    )
    (comp (ref "LOGO2")
      (value "UMICH_SOLID_MEDIUM")
      (footprint "eagle-import:UMICH_SOLID_200MIL")
      (libsource (lib "eagle-import") (part "UMICH_SOLID_MEDIUM"))
    )
    (comp (ref "LOGO3")
      (value "UMICH_SOLID_MEDIUM")
      (footprint "eagle-import:UMICH_SOLID_200MIL")
      (libsource (lib "eagle-import") (part "UMICH_SOLID_MEDIUM"))
    )
    (comp (ref "LOGO4")
      (value "UMICH_SOLID_MEDIUM")
      (footprint "eagle-import:UMICH_SOLID_200MIL")
      (libsource (lib "eagle-import") (part "UMICH_SOLID_MEDIUM"))
    )
    (comp (ref "LOGO5")
      (value "UMICH_SOLID_MEDIUM")
      (footprint "eagle-import:UMICH_SOLID_200MIL")
      (libsource (lib "eagle-import") (part "UMICH_SOLID_MEDIUM"))
    )
    (comp (ref "LOGO6")
      (value "UMICH_SOLID_MEDIUM")
      (footprint "eagle-import:UMICH_SOLID_200MIL")
      (libsource (lib "eagle-import") (part "UMICH_SOLID_MEDIUM"))
    )
    (comp (ref "LOGO7")
      (value "UMICH_SOLID_MEDIUM")
      (footprint "eagle-import:UMICH_SOLID_200MIL")
      (libsource (lib "eagle-import") (part "UMICH_SOLID_MEDIUM"))
    )
    (comp (ref "C70")
      (value "100nF")
      (footprint "eagle-import:0603_CAP")
      (libsource (lib "eagle-import") (part "CAPACITOR0603_CAP"))
    )
    (comp (ref "C71")
      (value "100nF")
      (footprint "eagle-import:0603_CAP")
      (libsource (lib "eagle-import") (part "CAPACITOR0603_CAP"))
    )
    (comp (ref "C72")
      (value "100nF")
      (footprint "eagle-import:0603_CAP")
      (libsource (lib "eagle-import") (part "CAPACITOR0603_CAP"))
    )
    (comp (ref "C73")
      (value "100nF")
      (footprint "eagle-import:0603_CAP")
      (libsource (lib "eagle-import") (part "CAPACITOR0603_CAP"))
    )
    (comp (ref "C74")
      (value "100nF")
      (footprint "eagle-import:0603_CAP")
      (libsource (lib "eagle-import") (part "CAPACITOR0603_CAP"))
    )
    (comp (ref "C75")
      (value "100nF")
      (footprint "eagle-import:0603_CAP")
      (libsource (lib "eagle-import") (part "CAPACITOR0603_CAP"))
    )
    (comp (ref "C76")
      (value "100nF")
      (footprint "eagle-import:0603_CAP")
      (libsource (lib "eagle-import") (part "CAPACITOR0603_CAP"))
    )
    (comp (ref "C77")
      (value "100nF")
      (footprint "eagle-import:0603_CAP")
      (libsource (lib "eagle-import") (part "CAPACITOR0603_CAP"))
    )
    (comp (ref "C78")
      (value "100nF")
      (footprint "eagle-import:0603_CAP")
      (libsource (lib "eagle-import") (part "CAPACITOR0603_CAP"))
    )
    (comp (ref "C79")
      (value "100nF")
      (footprint "eagle-import:0603_CAP")
      (libsource (lib "eagle-import") (part "CAPACITOR0603_CAP"))
    )
    (comp (ref "C80")
      (value "100nF")
      (footprint "eagle-import:0603_CAP")
      (libsource (lib "eagle-import") (part "CAPACITOR0603_CAP"))
    )
    (comp (ref "C81")
      (value "100nF")
      (footprint "eagle-import:0603_CAP")
      (libsource (lib "eagle-import") (part "CAPACITOR0603_CAP"))
    )
    (comp (ref "C82")
      (value "100nF")
      (footprint "eagle-import:0603_CAP")
      (libsource (lib "eagle-import") (part "CAPACITOR0603_CAP"))
    )
    (comp (ref "C83")
      (value "100nF")
      (footprint "eagle-import:0603_CAP")
      (libsource (lib "eagle-import") (part "CAPACITOR0603_CAP"))
    )
    (comp (ref "C84")
      (value "100nF")
      (footprint "eagle-import:0603_CAP")
      (libsource (lib "eagle-import") (part "CAPACITOR0603_CAP"))
    )
    (comp (ref "C85")
      (value "100nF")
      (footprint "eagle-import:0603_CAP")
      (libsource (lib "eagle-import") (part "CAPACITOR0603_CAP"))
    )
    (comp (ref "C86")
      (value "100nF")
      (footprint "eagle-import:0603_CAP")
      (libsource (lib "eagle-import") (part "CAPACITOR0603_CAP"))
    )
    (comp (ref "C87")
      (value "100nF")
      (footprint "eagle-import:0603_CAP")
      (libsource (lib "eagle-import") (part "CAPACITOR0603_CAP"))
    )
    (comp (ref "C95")
      (value "150uF")
      (footprint "eagle-import:1210_CAP")
      (libsource (lib "eagle-import") (part "CAPACITOR1210_CAP"))
    )
    (comp (ref "C96")
      (value "150uF")
      (footprint "eagle-import:1210_CAP")
      (libsource (lib "eagle-import") (part "CAPACITOR1210_CAP"))
    )
    (comp (ref "C97")
      (value "150uF")
      (footprint "eagle-import:1210_CAP")
      (libsource (lib "eagle-import") (part "CAPACITOR1210_CAP"))
    )
    (comp (ref "C98")
      (value "150uF")
      (footprint "eagle-import:1210_CAP")
      (libsource (lib "eagle-import") (part "CAPACITOR1210_CAP"))
    )
    (comp (ref "C99")
      (value "150uF")
      (footprint "eagle-import:1210_CAP")
      (libsource (lib "eagle-import") (part "CAPACITOR1210_CAP"))
    )
    (comp (ref "C100")
      (value "150uF")
      (footprint "eagle-import:1210_CAP")
      (libsource (lib "eagle-import") (part "CAPACITOR1210_CAP"))
    )
    (comp (ref "R28")
      (value "10kΩ")
      (footprint "eagle-import:0603-RES")
      (libsource (lib "eagle-import") (part "RESISTOR0603_RES"))
    )
    (comp (ref "R29")
      (value "10kΩ")
      (footprint "eagle-import:0603-RES")
      (libsource (lib "eagle-import") (part "RESISTOR0603_RES"))
    )
    (comp (ref "R30")
      (value "10kΩ")
      (footprint "eagle-import:0603-RES")
      (libsource (lib "eagle-import") (part "RESISTOR0603_RES"))
    )
    (comp (ref "R31")
      (value "10kΩ")
      (footprint "eagle-import:0603-RES")
      (libsource (lib "eagle-import") (part "RESISTOR0603_RES"))
    )
    (comp (ref "R32")
      (value "10kΩ")
      (footprint "eagle-import:0603-RES")
      (libsource (lib "eagle-import") (part "RESISTOR0603_RES"))
    )
    (comp (ref "R33")
      (value "10kΩ")
      (footprint "eagle-import:0603-RES")
      (libsource (lib "eagle-import") (part "RESISTOR0603_RES"))
    )
    (comp (ref "S7")
      (value "NC7SZ157")
      (footprint "eagle-import:SC70-6")
      (libsource (lib "eagle-import") (part "NC7SZ157"))
    )
    (comp (ref "S8")
      (value "NC7SZ157")
      (footprint "eagle-import:SC70-6")
      (libsource (lib "eagle-import") (part "NC7SZ157"))
    )
    (comp (ref "S9")
      (value "NC7SZ157")
      (footprint "eagle-import:SC70-6")
      (libsource (lib "eagle-import") (part "NC7SZ157"))
    )
    (comp (ref "S10")
      (value "NC7SZ157")
      (footprint "eagle-import:SC70-6")
      (libsource (lib "eagle-import") (part "NC7SZ157"))
    )
    (comp (ref "S11")
      (value "NC7SZ157")
      (footprint "eagle-import:SC70-6")
      (libsource (lib "eagle-import") (part "NC7SZ157"))
    )
    (comp (ref "S12")
      (value "NC7SZ157")
      (footprint "eagle-import:SC70-6")
      (libsource (lib "eagle-import") (part "NC7SZ157"))
    )
    (comp (ref "S13")
      (value "AP2401MP")
      (footprint "eagle-import:MSOP-8EP")
      (libsource (lib "eagle-import") (part "AP2401MP"))
    )
    (comp (ref "S14")
      (value "AP2401MP")
      (footprint "eagle-import:MSOP-8EP")
      (libsource (lib "eagle-import") (part "AP2401MP"))
    )
    (comp (ref "S15")
      (value "AP2401MP")
      (footprint "eagle-import:MSOP-8EP")
      (libsource (lib "eagle-import") (part "AP2401MP"))
    )
    (comp (ref "S16")
      (value "AP2401MP")
      (footprint "eagle-import:MSOP-8EP")
      (libsource (lib "eagle-import") (part "AP2401MP"))
    )
    (comp (ref "S17")
      (value "AP2401MP")
      (footprint "eagle-import:MSOP-8EP")
      (libsource (lib "eagle-import") (part "AP2401MP"))
    )
    (comp (ref "S18")
      (value "AP2401MP")
      (footprint "eagle-import:MSOP-8EP")
      (libsource (lib "eagle-import") (part "AP2401MP"))
    )
    (comp (ref "J3")
      (value "BACKPLANE_CONTROLLER_MODULE")
      (footprint "eagle-import:BACKPLANE_MODULE_20PIN_10PIN")
      (libsource (lib "eagle-import") (part "BACKPLANE_CONTROLLER_MODULE"))
    )
    (comp (ref "J4")
      (value "BACKPLANE_POWER_MODULE")
      (footprint "eagle-import:BACKPLANE_MODULE_20PIN")
      (libsource (lib "eagle-import") (part "BACKPLANE_POWER_MODULE"))
    )
    (comp (ref "LOGO1")
      (value "UMICH_SOLID_GIANT")
      (footprint "eagle-import:UMICH_SOLID_1000MIL")
      (libsource (lib "eagle-import") (part "UMICH_SOLID_GIANT"))
    )
    (comp (ref "LOGO8")
      (value "UMICH_SOLID_MEDIUM")
      (footprint "eagle-import:UMICH_SOLID_200MIL")
      (libsource (lib "eagle-import") (part "UMICH_SOLID_MEDIUM"))
    )
    (comp (ref "LOGO9")
      (value "UMICH_SOLID_MEDIUM")
      (footprint "eagle-import:UMICH_SOLID_200MIL")
      (libsource (lib "eagle-import") (part "UMICH_SOLID_MEDIUM"))
    )
    (comp (ref "R27")
      (value "1.5kΩ")
      (footprint "eagle-import:0603-RES")
      (libsource (lib "eagle-import") (part "RESISTOR0603_RES"))
    )
    (comp (ref "R46")
      (value "10kΩ")
      (footprint "eagle-import:0603-RES")
      (libsource (lib "eagle-import") (part "RESISTOR0603_RES"))
    )
    (comp (ref "R47")
      (value "10kΩ")
      (footprint "eagle-import:0603-RES")
      (libsource (lib "eagle-import") (part "RESISTOR0603_RES"))
    )
    (comp (ref "R48")
      (value "10kΩ")
      (footprint "eagle-import:0603-RES")
      (libsource (lib "eagle-import") (part "RESISTOR0603_RES"))
    )
    (comp (ref "R49")
      (value "10kΩ")
      (footprint "eagle-import:0603-RES")
      (libsource (lib "eagle-import") (part "RESISTOR0603_RES"))
    )
    (comp (ref "R50")
      (value "10kΩ")
      (footprint "eagle-import:0603-RES")
      (libsource (lib "eagle-import") (part "RESISTOR0603_RES"))
    )
  )
  (nets
    (net (code "1") (name "CONT_MOD0_IN") (class "Default")
      (node (ref "J3") (pin "9") (pinfunction "MOD0_IN_9") (pintype "bidirectional"))
      (node (ref "U8") (pin "2") (pinfunction "A1_2") (pintype "bidirectional"))
    )
    (net (code "2") (name "CONT_MOD0_OUT") (class "Default")
      (node (ref "J3") (pin "10") (pinfunction "MOD0_OUT_10") (pintype "bidirectional"))
      (node (ref "U14") (pin "2") (pinfunction "A1_2") (pintype "bidirectional"))
    )
    (net (code "3") (name "CONT_MOD1_IN") (class "Default")
      (node (ref "J3") (pin "11") (pinfunction "MOD1_IN_11") (pintype "bidirectional"))
      (node (ref "U9") (pin "2") (pinfunction "A1_2") (pintype "bidirectional"))
    )
    (net (code "4") (name "CONT_MOD1_OUT") (class "Default")
      (node (ref "J3") (pin "12") (pinfunction "MOD1_OUT_12") (pintype "bidirectional"))
      (node (ref "U15") (pin "2") (pinfunction "A1_2") (pintype "bidirectional"))
    )
    (net (code "5") (name "CONT_MOD2_IN") (class "Default")
      (node (ref "J3") (pin "13") (pinfunction "MOD2_IN_13") (pintype "bidirectional"))
      (node (ref "U10") (pin "2") (pinfunction "A1_2") (pintype "bidirectional"))
    )
    (net (code "6") (name "CONT_MOD2_OUT") (class "Default")
      (node (ref "J3") (pin "14") (pinfunction "MOD2_OUT_14") (pintype "bidirectional"))
      (node (ref "U16") (pin "2") (pinfunction "A1_2") (pintype "bidirectional"))
    )
    (net (code "7") (name "CONT_MOD5_IN") (class "Default")
      (node (ref "J3") (pin "15") (pinfunction "MOD5_IN_15") (pintype "bidirectional"))
      (node (ref "U11") (pin "2") (pinfunction "A1_2") (pintype "bidirectional"))
    )
    (net (code "8") (name "CONT_MOD5_OUT") (class "Default")
      (node (ref "J3") (pin "16") (pinfunction "MOD5_OUT_16") (pintype "bidirectional"))
      (node (ref "U17") (pin "2") (pinfunction "A1_2") (pintype "bidirectional"))
    )
    (net (code "9") (name "CONT_MOD6_IN") (class "Default")
      (node (ref "J3") (pin "17") (pinfunction "MOD6_IN_17") (pintype "bidirectional"))
      (node (ref "U12") (pin "2") (pinfunction "A1_2") (pintype "bidirectional"))
    )
    (net (code "10") (name "CONT_MOD6_OUT") (class "Default")
      (node (ref "J3") (pin "18") (pinfunction "MOD6_OUT_18") (pintype "bidirectional"))
      (node (ref "U18") (pin "2") (pinfunction "A1_2") (pintype "bidirectional"))
    )
    (net (code "11") (name "CONT_MOD7_IN") (class "Default")
      (node (ref "J3") (pin "19") (pinfunction "MOD7_IN_19") (pintype "bidirectional"))
      (node (ref "U13") (pin "2") (pinfunction "A1_2") (pintype "bidirectional"))
    )
    (net (code "12") (name "CONT_MOD7_OUT") (class "Default")
      (node (ref "J3") (pin "20") (pinfunction "MOD7_OUT_20") (pintype "bidirectional"))
      (node (ref "U19") (pin "2") (pinfunction "A1_2") (pintype "bidirectional"))
    )
    (net (code "13") (name "CONT_USB+") (class "Default")
      (node (ref "J3") (pin "27") (pinfunction "USB_D+_27") (pintype "bidirectional"))
      (node (ref "R25") (pin "1") (pinfunction "1_1") (pintype "passive"))
      (node (ref "U1") (pin "3") (pinfunction "DP0_3") (pintype "bidirectional"))
    )
    (net (code "14") (name "CONT_USB-") (class "Default")
      (node (ref "J3") (pin "28") (pinfunction "USB_D-_28") (pintype "bidirectional"))
      (node (ref "U1") (pin "4") (pinfunction "DM0_4") (pintype "bidirectional"))
    )
    (net (code "15") (name "GND") (class "Default")
      (node (ref "C1") (pin "1") (pinfunction "1_1") (pintype "bidirectional"))
      (node (ref "C10") (pin "2") (pinfunction "2_2") (pintype "bidirectional"))
      (node (ref "C100") (pin "2") (pinfunction "2_2") (pintype "bidirectional"))
      (node (ref "C11") (pin "2") (pinfunction "2_2") (pintype "bidirectional"))
      (node (ref "C12") (pin "2") (pinfunction "2_2") (pintype "bidirectional"))
      (node (ref "C13") (pin "2") (pinfunction "2_2") (pintype "bidirectional"))
      (node (ref "C14") (pin "2") (pinfunction "2_2") (pintype "bidirectional"))
      (node (ref "C15") (pin "2") (pinfunction "2_2") (pintype "bidirectional"))
      (node (ref "C16") (pin "2") (pinfunction "2_2") (pintype "bidirectional"))
      (node (ref "C17") (pin "2") (pinfunction "2_2") (pintype "bidirectional"))
      (node (ref "C18") (pin "2") (pinfunction "2_2") (pintype "bidirectional"))
      (node (ref "C19") (pin "2") (pinfunction "2_2") (pintype "bidirectional"))
      (node (ref "C2") (pin "1") (pinfunction "1_1") (pintype "bidirectional"))
      (node (ref "C20") (pin "2") (pinfunction "2_2") (pintype "bidirectional"))
      (node (ref "C21") (pin "2") (pinfunction "2_2") (pintype "bidirectional"))
      (node (ref "C22") (pin "2") (pinfunction "2_2") (pintype "bidirectional"))
      (node (ref "C23") (pin "2") (pinfunction "2_2") (pintype "bidirectional"))
      (node (ref "C24") (pin "2") (pinfunction "2_2") (pintype "bidirectional"))
      (node (ref "C25") (pin "2") (pinfunction "2_2") (pintype "bidirectional"))
      (node (ref "C26") (pin "2") (pinfunction "2_2") (pintype "bidirectional"))
      (node (ref "C27") (pin "2") (pinfunction "2_2") (pintype "bidirectional"))
      (node (ref "C28") (pin "2") (pinfunction "2_2") (pintype "bidirectional"))
      (node (ref "C29") (pin "2") (pinfunction "2_2") (pintype "bidirectional"))
      (node (ref "C3") (pin "2") (pinfunction "2_2") (pintype "bidirectional"))
      (node (ref "C30") (pin "2") (pinfunction "2_2") (pintype "bidirectional"))
      (node (ref "C31") (pin "2") (pinfunction "2_2") (pintype "bidirectional"))
      (node (ref "C32") (pin "2") (pinfunction "2_2") (pintype "bidirectional"))
      (node (ref "C33") (pin "2") (pinfunction "2_2") (pintype "bidirectional"))
      (node (ref "C34") (pin "2") (pinfunction "2_2") (pintype "bidirectional"))
      (node (ref "C35") (pin "2") (pinfunction "2_2") (pintype "bidirectional"))
      (node (ref "C36") (pin "2") (pinfunction "2_2") (pintype "bidirectional"))
      (node (ref "C37") (pin "2") (pinfunction "2_2") (pintype "bidirectional"))
      (node (ref "C38") (pin "2") (pinfunction "2_2") (pintype "bidirectional"))
      (node (ref "C39") (pin "2") (pinfunction "2_2") (pintype "bidirectional"))
      (node (ref "C4") (pin "2") (pinfunction "2_2") (pintype "bidirectional"))
      (node (ref "C40") (pin "2") (pinfunction "2_2") (pintype "bidirectional"))
      (node (ref "C41") (pin "2") (pinfunction "2_2") (pintype "bidirectional"))
      (node (ref "C42") (pin "2") (pinfunction "2_2") (pintype "bidirectional"))
      (node (ref "C43") (pin "2") (pinfunction "2_2") (pintype "bidirectional"))
      (node (ref "C44") (pin "2") (pinfunction "2_2") (pintype "bidirectional"))
      (node (ref "C45") (pin "2") (pinfunction "2_2") (pintype "bidirectional"))
      (node (ref "C46") (pin "2") (pinfunction "2_2") (pintype "bidirectional"))
      (node (ref "C47") (pin "2") (pinfunction "2_2") (pintype "bidirectional"))
      (node (ref "C48") (pin "2") (pinfunction "2_2") (pintype "bidirectional"))
      (node (ref "C49") (pin "2") (pinfunction "2_2") (pintype "bidirectional"))
      (node (ref "C5") (pin "2") (pinfunction "2_2") (pintype "bidirectional"))
      (node (ref "C50") (pin "2") (pinfunction "2_2") (pintype "bidirectional"))
      (node (ref "C51") (pin "2") (pinfunction "2_2") (pintype "bidirectional"))
      (node (ref "C52") (pin "2") (pinfunction "2_2") (pintype "bidirectional"))
      (node (ref "C53") (pin "2") (pinfunction "2_2") (pintype "bidirectional"))
      (node (ref "C54") (pin "2") (pinfunction "2_2") (pintype "bidirectional"))
      (node (ref "C55") (pin "2") (pinfunction "2_2") (pintype "bidirectional"))
      (node (ref "C56") (pin "2") (pinfunction "2_2") (pintype "bidirectional"))
      (node (ref "C57") (pin "2") (pinfunction "2_2") (pintype "bidirectional"))
      (node (ref "C58") (pin "2") (pinfunction "2_2") (pintype "bidirectional"))
      (node (ref "C59") (pin "2") (pinfunction "2_2") (pintype "bidirectional"))
      (node (ref "C6") (pin "2") (pinfunction "2_2") (pintype "bidirectional"))
      (node (ref "C60") (pin "2") (pinfunction "2_2") (pintype "bidirectional"))
      (node (ref "C61") (pin "2") (pinfunction "2_2") (pintype "bidirectional"))
      (node (ref "C62") (pin "2") (pinfunction "2_2") (pintype "bidirectional"))
      (node (ref "C63") (pin "1") (pinfunction "1_1") (pintype "bidirectional"))
      (node (ref "C64") (pin "1") (pinfunction "1_1") (pintype "bidirectional"))
      (node (ref "C65") (pin "1") (pinfunction "1_1") (pintype "bidirectional"))
      (node (ref "C66") (pin "1") (pinfunction "1_1") (pintype "bidirectional"))
      (node (ref "C67") (pin "1") (pinfunction "1_1") (pintype "bidirectional"))
      (node (ref "C68") (pin "1") (pinfunction "1_1") (pintype "bidirectional"))
      (node (ref "C69") (pin "1") (pinfunction "1_1") (pintype "bidirectional"))
      (node (ref "C7") (pin "2") (pinfunction "2_2") (pintype "bidirectional"))
      (node (ref "C70") (pin "2") (pinfunction "2_2") (pintype "bidirectional"))
      (node (ref "C71") (pin "2") (pinfunction "2_2") (pintype "bidirectional"))
      (node (ref "C72") (pin "2") (pinfunction "2_2") (pintype "bidirectional"))
      (node (ref "C73") (pin "2") (pinfunction "2_2") (pintype "bidirectional"))
      (node (ref "C74") (pin "2") (pinfunction "2_2") (pintype "bidirectional"))
      (node (ref "C75") (pin "2") (pinfunction "2_2") (pintype "bidirectional"))
      (node (ref "C76") (pin "2") (pinfunction "2_2") (pintype "bidirectional"))
      (node (ref "C77") (pin "2") (pinfunction "2_2") (pintype "bidirectional"))
      (node (ref "C78") (pin "2") (pinfunction "2_2") (pintype "bidirectional"))
      (node (ref "C79") (pin "2") (pinfunction "2_2") (pintype "bidirectional"))
      (node (ref "C8") (pin "2") (pinfunction "2_2") (pintype "bidirectional"))
      (node (ref "C80") (pin "2") (pinfunction "2_2") (pintype "bidirectional"))
      (node (ref "C81") (pin "2") (pinfunction "2_2") (pintype "bidirectional"))
      (node (ref "C82") (pin "2") (pinfunction "2_2") (pintype "bidirectional"))
      (node (ref "C83") (pin "2") (pinfunction "2_2") (pintype "bidirectional"))
      (node (ref "C84") (pin "2") (pinfunction "2_2") (pintype "bidirectional"))
      (node (ref "C85") (pin "2") (pinfunction "2_2") (pintype "bidirectional"))
      (node (ref "C86") (pin "2") (pinfunction "2_2") (pintype "bidirectional"))
      (node (ref "C87") (pin "2") (pinfunction "2_2") (pintype "bidirectional"))
      (node (ref "C88") (pin "2") (pinfunction "2_2") (pintype "bidirectional"))
      (node (ref "C89") (pin "2") (pinfunction "2_2") (pintype "bidirectional"))
      (node (ref "C9") (pin "2") (pinfunction "2_2") (pintype "bidirectional"))
      (node (ref "C90") (pin "2") (pinfunction "2_2") (pintype "bidirectional"))
      (node (ref "C91") (pin "2") (pinfunction "2_2") (pintype "bidirectional"))
      (node (ref "C92") (pin "2") (pinfunction "2_2") (pintype "bidirectional"))
      (node (ref "C93") (pin "2") (pinfunction "2_2") (pintype "bidirectional"))
      (node (ref "C94") (pin "1") (pinfunction "1_1") (pintype "bidirectional"))
      (node (ref "C95") (pin "2") (pinfunction "2_2") (pintype "bidirectional"))
      (node (ref "C96") (pin "2") (pinfunction "2_2") (pintype "bidirectional"))
      (node (ref "C97") (pin "2") (pinfunction "2_2") (pintype "bidirectional"))
      (node (ref "C98") (pin "2") (pinfunction "2_2") (pintype "bidirectional"))
      (node (ref "C99") (pin "2") (pinfunction "2_2") (pintype "bidirectional"))
      (node (ref "D1") (pin "1") (pinfunction "GND_1") (pintype "bidirectional"))
      (node (ref "D1") (pin "3") (pinfunction "GND_3") (pintype "bidirectional"))
      (node (ref "D1") (pin "5") (pinfunction "GND_5") (pintype "bidirectional"))
      (node (ref "D1") (pin "7") (pinfunction "GND_7") (pintype "bidirectional"))
      (node (ref "D2") (pin "1") (pinfunction "GND_1") (pintype "bidirectional"))
      (node (ref "D2") (pin "3") (pinfunction "GND_3") (pintype "bidirectional"))
      (node (ref "D2") (pin "5") (pinfunction "GND_5") (pintype "bidirectional"))
      (node (ref "D2") (pin "7") (pinfunction "GND_7") (pintype "bidirectional"))
      (node (ref "D3") (pin "1") (pinfunction "GND_1") (pintype "bidirectional"))
      (node (ref "D3") (pin "3") (pinfunction "GND_3") (pintype "bidirectional"))
      (node (ref "D3") (pin "5") (pinfunction "GND_5") (pintype "bidirectional"))
      (node (ref "D3") (pin "7") (pinfunction "GND_7") (pintype "bidirectional"))
      (node (ref "D4") (pin "1") (pinfunction "GND_1") (pintype "bidirectional"))
      (node (ref "D4") (pin "3") (pinfunction "GND_3") (pintype "bidirectional"))
      (node (ref "D4") (pin "5") (pinfunction "GND_5") (pintype "bidirectional"))
      (node (ref "D4") (pin "7") (pinfunction "GND_7") (pintype "bidirectional"))
      (node (ref "J0") (pin "1") (pinfunction "GND_1") (pintype "bidirectional"))
      (node (ref "J0") (pin "14") (pinfunction "GND_14") (pintype "bidirectional"))
      (node (ref "J1") (pin "1") (pinfunction "GND_1") (pintype "bidirectional"))
      (node (ref "J1") (pin "14") (pinfunction "GND_14") (pintype "bidirectional"))
      (node (ref "J2") (pin "1") (pinfunction "GND_1") (pintype "bidirectional"))
      (node (ref "J2") (pin "14") (pinfunction "GND_14") (pintype "bidirectional"))
      (node (ref "J3") (pin "1") (pinfunction "GND_1") (pintype "bidirectional"))
      (node (ref "J3") (pin "21") (pinfunction "GND_21") (pintype "bidirectional"))
      (node (ref "J4") (pin "1") (pinfunction "GND_1") (pintype "power_in"))
      (node (ref "J5") (pin "1") (pinfunction "GND_1") (pintype "bidirectional"))
      (node (ref "J5") (pin "14") (pinfunction "GND_14") (pintype "bidirectional"))
      (node (ref "J6") (pin "1") (pinfunction "GND_1") (pintype "bidirectional"))
      (node (ref "J6") (pin "14") (pinfunction "GND_14") (pintype "bidirectional"))
      (node (ref "J7") (pin "1") (pinfunction "GND_1") (pintype "bidirectional"))
      (node (ref "J7") (pin "14") (pinfunction "GND_14") (pintype "bidirectional"))
      (node (ref "LED1001") (pin "C") (pinfunction "CATHODE_C") (pintype "bidirectional"))
      (node (ref "LED1002") (pin "C") (pinfunction "CATHODE_C") (pintype "bidirectional"))
      (node (ref "LED1003") (pin "C") (pinfunction "CATHODE_C") (pintype "bidirectional"))
      (node (ref "LED1007") (pin "C") (pinfunction "CATHODE_C") (pintype "bidirectional"))
      (node (ref "LED1008") (pin "C") (pinfunction "CATHODE_C") (pintype "bidirectional"))
      (node (ref "LED1009") (pin "C") (pinfunction "CATHODE_C") (pintype "bidirectional"))
      (node (ref "LED1013") (pin "C") (pinfunction "CATHODE_C") (pintype "bidirectional"))
      (node (ref "LED1014") (pin "C") (pinfunction "CATHODE_C") (pintype "bidirectional"))
      (node (ref "LED1015") (pin "C") (pinfunction "CATHODE_C") (pintype "bidirectional"))
      (node (ref "R1004") (pin "1") (pinfunction "1_1") (pintype "passive"))
      (node (ref "R1005") (pin "1") (pinfunction "1_1") (pintype "passive"))
      (node (ref "R1006") (pin "1") (pinfunction "1_1") (pintype "passive"))
      (node (ref "R1010") (pin "1") (pinfunction "1_1") (pintype "passive"))
      (node (ref "R1011") (pin "1") (pinfunction "1_1") (pintype "passive"))
      (node (ref "R1012") (pin "1") (pinfunction "1_1") (pintype "passive"))
      (node (ref "R1016") (pin "1") (pinfunction "1_1") (pintype "passive"))
      (node (ref "R1017") (pin "1") (pinfunction "1_1") (pintype "passive"))
      (node (ref "R1018") (pin "1") (pinfunction "1_1") (pintype "passive"))
      (node (ref "R13") (pin "2") (pinfunction "2_2") (pintype "passive"))
      (node (ref "R14") (pin "2") (pinfunction "2_2") (pintype "passive"))
      (node (ref "R15") (pin "2") (pinfunction "2_2") (pintype "passive"))
      (node (ref "R16") (pin "2") (pinfunction "2_2") (pintype "passive"))
      (node (ref "R17") (pin "2") (pinfunction "2_2") (pintype "passive"))
      (node (ref "R18") (pin "2") (pinfunction "2_2") (pintype "passive"))
      (node (ref "R19") (pin "2") (pinfunction "2_2") (pintype "passive"))
      (node (ref "R20") (pin "2") (pinfunction "2_2") (pintype "passive"))
      (node (ref "R21") (pin "2") (pinfunction "2_2") (pintype "passive"))
      (node (ref "R22") (pin "2") (pinfunction "2_2") (pintype "passive"))
      (node (ref "R23") (pin "2") (pinfunction "2_2") (pintype "passive"))
      (node (ref "R24") (pin "2") (pinfunction "2_2") (pintype "passive"))
      (node (ref "R52") (pin "1") (pinfunction "1_1") (pintype "passive"))
      (node (ref "R53") (pin "1") (pinfunction "1_1") (pintype "passive"))
      (node (ref "R54") (pin "1") (pinfunction "1_1") (pintype "passive"))
      (node (ref "R55") (pin "1") (pinfunction "1_1") (pintype "passive"))
      (node (ref "R56") (pin "1") (pinfunction "1_1") (pintype "passive"))
      (node (ref "R57") (pin "1") (pinfunction "1_1") (pintype "passive"))
      (node (ref "R58") (pin "1") (pinfunction "1_1") (pintype "passive"))
      (node (ref "R59") (pin "1") (pinfunction "1_1") (pintype "passive"))
      (node (ref "R60") (pin "1") (pinfunction "1_1") (pintype "passive"))
      (node (ref "R61") (pin "1") (pinfunction "1_1") (pintype "passive"))
      (node (ref "R62") (pin "1") (pinfunction "1_1") (pintype "passive"))
      (node (ref "R63") (pin "1") (pinfunction "1_1") (pintype "passive"))
      (node (ref "R64") (pin "2") (pinfunction "2_2") (pintype "passive"))
      (node (ref "R65") (pin "2") (pinfunction "2_2") (pintype "passive"))
      (node (ref "R66") (pin "1") (pinfunction "1_1") (pintype "passive"))
      (node (ref "R67") (pin "1") (pinfunction "1_1") (pintype "passive"))
      (node (ref "R68") (pin "1") (pinfunction "1_1") (pintype "passive"))
      (node (ref "R69") (pin "1") (pinfunction "1_1") (pintype "passive"))
      (node (ref "R70") (pin "1") (pinfunction "1_1") (pintype "passive"))
      (node (ref "R71") (pin "1") (pinfunction "1_1") (pintype "passive"))
      (node (ref "R72") (pin "1") (pinfunction "1_1") (pintype "passive"))
      (node (ref "R73") (pin "1") (pinfunction "1_1") (pintype "passive"))
      (node (ref "R74") (pin "1") (pinfunction "1_1") (pintype "passive"))
      (node (ref "R75") (pin "1") (pinfunction "1_1") (pintype "passive"))
      (node (ref "R76") (pin "1") (pinfunction "1_1") (pintype "passive"))
      (node (ref "R77") (pin "1") (pinfunction "1_1") (pintype "passive"))
      (node (ref "R78") (pin "1") (pinfunction "1_1") (pintype "passive"))
      (node (ref "R79") (pin "1") (pinfunction "1_1") (pintype "passive"))
      (node (ref "R80") (pin "1") (pinfunction "1_1") (pintype "passive"))
      (node (ref "R81") (pin "1") (pinfunction "1_1") (pintype "passive"))
      (node (ref "R82") (pin "1") (pinfunction "1_1") (pintype "passive"))
      (node (ref "R83") (pin "1") (pinfunction "1_1") (pintype "passive"))
      (node (ref "S1") (pin "2") (pinfunction "GND_2") (pintype "bidirectional"))
      (node (ref "S1") (pin "PAD") (pinfunction "GND_PAD") (pintype "bidirectional"))
      (node (ref "S10") (pin "2") (pinfunction "GND_2") (pintype "bidirectional"))
      (node (ref "S11") (pin "2") (pinfunction "GND_2") (pintype "bidirectional"))
      (node (ref "S12") (pin "2") (pinfunction "GND_2") (pintype "bidirectional"))
      (node (ref "S13") (pin "1") (pinfunction "GND_1") (pintype "bidirectional"))
      (node (ref "S13") (pin "PAD") (pinfunction "GND_PAD") (pintype "bidirectional"))
      (node (ref "S14") (pin "1") (pinfunction "GND_1") (pintype "bidirectional"))
      (node (ref "S14") (pin "PAD") (pinfunction "GND_PAD") (pintype "bidirectional"))
      (node (ref "S15") (pin "1") (pinfunction "GND_1") (pintype "bidirectional"))
      (node (ref "S15") (pin "PAD") (pinfunction "GND_PAD") (pintype "bidirectional"))
      (node (ref "S16") (pin "1") (pinfunction "GND_1") (pintype "bidirectional"))
      (node (ref "S16") (pin "PAD") (pinfunction "GND_PAD") (pintype "bidirectional"))
      (node (ref "S17") (pin "1") (pinfunction "GND_1") (pintype "bidirectional"))
      (node (ref "S17") (pin "PAD") (pinfunction "GND_PAD") (pintype "bidirectional"))
      (node (ref "S18") (pin "1") (pinfunction "GND_1") (pintype "bidirectional"))
      (node (ref "S18") (pin "PAD") (pinfunction "GND_PAD") (pintype "bidirectional"))
      (node (ref "S2") (pin "2") (pinfunction "GND_2") (pintype "bidirectional"))
      (node (ref "S2") (pin "PAD") (pinfunction "GND_PAD") (pintype "bidirectional"))
      (node (ref "S3") (pin "2") (pinfunction "GND_2") (pintype "bidirectional"))
      (node (ref "S3") (pin "PAD") (pinfunction "GND_PAD") (pintype "bidirectional"))
      (node (ref "S4") (pin "2") (pinfunction "GND_2") (pintype "bidirectional"))
      (node (ref "S4") (pin "PAD") (pinfunction "GND_PAD") (pintype "bidirectional"))
      (node (ref "S5") (pin "2") (pinfunction "GND_2") (pintype "bidirectional"))
      (node (ref "S5") (pin "PAD") (pinfunction "GND_PAD") (pintype "bidirectional"))
      (node (ref "S6") (pin "2") (pinfunction "GND_2") (pintype "bidirectional"))
      (node (ref "S6") (pin "PAD") (pinfunction "GND_PAD") (pintype "bidirectional"))
      (node (ref "S7") (pin "2") (pinfunction "GND_2") (pintype "bidirectional"))
      (node (ref "S8") (pin "2") (pinfunction "GND_2") (pintype "bidirectional"))
      (node (ref "S9") (pin "2") (pinfunction "GND_2") (pintype "bidirectional"))
      (node (ref "TP11") (pin "TESTPOINT") (pinfunction "TESTPOINT_TESTPOINT") (pintype "bidirectional"))
      (node (ref "TP25") (pin "TESTPOINT") (pinfunction "TESTPOINT_TESTPOINT") (pintype "bidirectional"))
      (node (ref "TP26") (pin "TESTPOINT") (pinfunction "TESTPOINT_TESTPOINT") (pintype "bidirectional"))
      (node (ref "TP27") (pin "TESTPOINT") (pinfunction "TESTPOINT_TESTPOINT") (pintype "bidirectional"))
      (node (ref "TP4") (pin "TESTPOINT") (pinfunction "TESTPOINT_TESTPOINT") (pintype "bidirectional"))
      (node (ref "TP7") (pin "TESTPOINT") (pinfunction "TESTPOINT_TESTPOINT") (pintype "bidirectional"))
      (node (ref "U1") (pin "10") (pinfunction "~{BUSPWR}_10") (pintype "bidirectional"))
      (node (ref "U1") (pin "24") (pinfunction "GND_24") (pintype "bidirectional"))
      (node (ref "U1") (pin "43") (pinfunction "GND_43") (pintype "bidirectional"))
      (node (ref "U1") (pin "48") (pinfunction "MODE_48") (pintype "bidirectional"))
      (node (ref "U1") (pin "5") (pinfunction "GND_5") (pintype "bidirectional"))
      (node (ref "U10") (pin "4") (pinfunction "GND_4") (pintype "bidirectional"))
      (node (ref "U11") (pin "4") (pinfunction "GND_4") (pintype "bidirectional"))
      (node (ref "U12") (pin "4") (pinfunction "GND_4") (pintype "bidirectional"))
      (node (ref "U13") (pin "4") (pinfunction "GND_4") (pintype "bidirectional"))
      (node (ref "U14") (pin "4") (pinfunction "GND_4") (pintype "bidirectional"))
      (node (ref "U14") (pin "5") (pinfunction "DIR_5") (pintype "bidirectional"))
      (node (ref "U15") (pin "4") (pinfunction "GND_4") (pintype "bidirectional"))
      (node (ref "U15") (pin "5") (pinfunction "DIR_5") (pintype "bidirectional"))
      (node (ref "U16") (pin "4") (pinfunction "GND_4") (pintype "bidirectional"))
      (node (ref "U16") (pin "5") (pinfunction "DIR_5") (pintype "bidirectional"))
      (node (ref "U17") (pin "4") (pinfunction "GND_4") (pintype "bidirectional"))
      (node (ref "U17") (pin "5") (pinfunction "DIR_5") (pintype "bidirectional"))
      (node (ref "U18") (pin "4") (pinfunction "GND_4") (pintype "bidirectional"))
      (node (ref "U19") (pin "4") (pinfunction "GND_4") (pintype "bidirectional"))
      (node (ref "U19") (pin "5") (pinfunction "DIR_5") (pintype "bidirectional"))
      (node (ref "U2") (pin "4") (pinfunction "GND_4") (pintype "bidirectional"))
      (node (ref "U20") (pin "10") (pinfunction "S_10") (pintype "bidirectional"))
      (node (ref "U20") (pin "4") (pinfunction "GND_4") (pintype "bidirectional"))
      (node (ref "U21") (pin "10") (pinfunction "S_10") (pintype "bidirectional"))
      (node (ref "U21") (pin "4") (pinfunction "GND_4") (pintype "bidirectional"))
      (node (ref "U22") (pin "10") (pinfunction "S_10") (pintype "bidirectional"))
      (node (ref "U22") (pin "4") (pinfunction "GND_4") (pintype "bidirectional"))
      (node (ref "U23") (pin "10") (pinfunction "S_10") (pintype "bidirectional"))
      (node (ref "U23") (pin "4") (pinfunction "GND_4") (pintype "bidirectional"))
      (node (ref "U24") (pin "10") (pinfunction "S_10") (pintype "bidirectional"))
      (node (ref "U24") (pin "4") (pinfunction "GND_4") (pintype "bidirectional"))
      (node (ref "U25") (pin "10") (pinfunction "S_10") (pintype "bidirectional"))
      (node (ref "U25") (pin "4") (pinfunction "GND_4") (pintype "bidirectional"))
      (node (ref "U26") (pin "3") (pinfunction "A2_3") (pintype "bidirectional"))
      (node (ref "U26") (pin "4") (pinfunction "A1_4") (pintype "bidirectional"))
      (node (ref "U26") (pin "5") (pinfunction "A0_5") (pintype "bidirectional"))
      (node (ref "U26") (pin "9") (pinfunction "GND_9") (pintype "bidirectional"))
      (node (ref "U27") (pin "3") (pinfunction "A2_3") (pintype "bidirectional"))
      (node (ref "U27") (pin "4") (pinfunction "A1_4") (pintype "bidirectional"))
      (node (ref "U27") (pin "9") (pinfunction "GND_9") (pintype "bidirectional"))
      (node (ref "U28") (pin "3") (pinfunction "A2_3") (pintype "bidirectional"))
      (node (ref "U28") (pin "5") (pinfunction "A0_5") (pintype "bidirectional"))
      (node (ref "U28") (pin "9") (pinfunction "GND_9") (pintype "bidirectional"))
      (node (ref "U29") (pin "4") (pinfunction "A1_4") (pintype "bidirectional"))
      (node (ref "U29") (pin "9") (pinfunction "GND_9") (pintype "bidirectional"))
      (node (ref "U3") (pin "4") (pinfunction "GND_4") (pintype "bidirectional"))
      (node (ref "U30") (pin "5") (pinfunction "A0_5") (pintype "bidirectional"))
      (node (ref "U30") (pin "9") (pinfunction "GND_9") (pintype "bidirectional"))
      (node (ref "U31") (pin "9") (pinfunction "GND_9") (pintype "bidirectional"))
      (node (ref "U4") (pin "4") (pinfunction "GND_4") (pintype "bidirectional"))
      (node (ref "U5") (pin "4") (pinfunction "GND_4") (pintype "bidirectional"))
      (node (ref "U6") (pin "4") (pinfunction "GND_4") (pintype "bidirectional"))
      (node (ref "U7") (pin "4") (pinfunction "GND_4") (pintype "bidirectional"))
      (node (ref "U8") (pin "4") (pinfunction "GND_4") (pintype "bidirectional"))
      (node (ref "U9") (pin "4") (pinfunction "GND_4") (pintype "bidirectional"))
    )
    (net (code "16") (name "HUB_CFG") (class "Default")
      (node (ref "TP28") (pin "TESTPOINT") (pinfunction "TESTPOINT_TESTPOINT") (pintype "bidirectional"))
      (node (ref "U1") (pin "40") (pinfunction "HUBCFG_40") (pintype "bidirectional"))
    )
    (net (code "17") (name "HUB_DM1") (class "Default")
      (node (ref "C6") (pin "1") (pinfunction "1_1") (pintype "bidirectional"))
      (node (ref "R4") (pin "1") (pinfunction "1_1") (pintype "passive"))
      (node (ref "U1") (pin "13") (pinfunction "DM1_13") (pintype "bidirectional"))
    )
    (net (code "18") (name "HUB_DM2") (class "Default")
      (node (ref "C4") (pin "1") (pinfunction "1_1") (pintype "bidirectional"))
      (node (ref "R2") (pin "1") (pinfunction "1_1") (pintype "passive"))
      (node (ref "U1") (pin "17") (pinfunction "DM2_17") (pintype "bidirectional"))
    )
    (net (code "19") (name "HUB_DM3") (class "Default")
      (node (ref "C8") (pin "1") (pinfunction "1_1") (pintype "bidirectional"))
      (node (ref "R6") (pin "1") (pinfunction "1_1") (pintype "passive"))
      (node (ref "U1") (pin "21") (pinfunction "DM3_21") (pintype "bidirectional"))
    )
    (net (code "20") (name "HUB_DM4") (class "Default")
      (node (ref "C12") (pin "1") (pinfunction "1_1") (pintype "bidirectional"))
      (node (ref "R10") (pin "1") (pinfunction "1_1") (pintype "passive"))
      (node (ref "U1") (pin "26") (pinfunction "DM4_26") (pintype "bidirectional"))
    )
    (net (code "21") (name "HUB_DM5") (class "Default")
      (node (ref "R65") (pin "1") (pinfunction "1_1") (pintype "passive"))
      (node (ref "U1") (pin "30") (pinfunction "DM5_30") (pintype "bidirectional"))
    )
    (net (code "22") (name "HUB_DM6") (class "Default")
      (node (ref "C14") (pin "1") (pinfunction "1_1") (pintype "bidirectional"))
      (node (ref "R12") (pin "1") (pinfunction "1_1") (pintype "passive"))
      (node (ref "U1") (pin "34") (pinfunction "DM6_34") (pintype "bidirectional"))
    )
    (net (code "23") (name "HUB_DM7") (class "Default")
      (node (ref "C10") (pin "1") (pinfunction "1_1") (pintype "bidirectional"))
      (node (ref "R8") (pin "1") (pinfunction "1_1") (pintype "passive"))
      (node (ref "U1") (pin "38") (pinfunction "DM7_38") (pintype "bidirectional"))
    )
    (net (code "24") (name "HUB_DP1") (class "Default")
      (node (ref "C5") (pin "1") (pinfunction "1_1") (pintype "bidirectional"))
      (node (ref "R3") (pin "1") (pinfunction "1_1") (pintype "passive"))
      (node (ref "U1") (pin "14") (pinfunction "DP1_14") (pintype "bidirectional"))
    )
    (net (code "25") (name "HUB_DP2") (class "Default")
      (node (ref "C3") (pin "1") (pinfunction "1_1") (pintype "bidirectional"))
      (node (ref "R1") (pin "1") (pinfunction "1_1") (pintype "passive"))
      (node (ref "U1") (pin "18") (pinfunction "DP2_18") (pintype "bidirectional"))
    )
    (net (code "26") (name "HUB_DP3") (class "Default")
      (node (ref "C7") (pin "1") (pinfunction "1_1") (pintype "bidirectional"))
      (node (ref "R5") (pin "1") (pinfunction "1_1") (pintype "passive"))
      (node (ref "U1") (pin "22") (pinfunction "DP3_22") (pintype "bidirectional"))
    )
    (net (code "27") (name "HUB_DP4") (class "Default")
      (node (ref "C11") (pin "1") (pinfunction "1_1") (pintype "bidirectional"))
      (node (ref "R9") (pin "1") (pinfunction "1_1") (pintype "passive"))
      (node (ref "U1") (pin "27") (pinfunction "DP4_27") (pintype "bidirectional"))
    )
    (net (code "28") (name "HUB_DP5") (class "Default")
      (node (ref "R64") (pin "1") (pinfunction "1_1") (pintype "passive"))
      (node (ref "U1") (pin "31") (pinfunction "DP5_31") (pintype "bidirectional"))
    )
    (net (code "29") (name "HUB_DP6") (class "Default")
      (node (ref "C13") (pin "1") (pinfunction "1_1") (pintype "bidirectional"))
      (node (ref "R11") (pin "1") (pinfunction "1_1") (pintype "passive"))
      (node (ref "U1") (pin "35") (pinfunction "DP6_35") (pintype "bidirectional"))
    )
    (net (code "30") (name "HUB_DP7") (class "Default")
      (node (ref "C9") (pin "1") (pinfunction "1_1") (pintype "bidirectional"))
      (node (ref "R7") (pin "1") (pinfunction "1_1") (pintype "passive"))
      (node (ref "U1") (pin "39") (pinfunction "DP7_39") (pintype "bidirectional"))
    )
    (net (code "31") (name "HUB_PORTDIS") (class "Default")
      (node (ref "TP30") (pin "TESTPOINT") (pinfunction "TESTPOINT_TESTPOINT") (pintype "bidirectional"))
      (node (ref "U1") (pin "42") (pinfunction "PORTDIS_42") (pintype "bidirectional"))
    )
    (net (code "32") (name "HUB_PORTPWR") (class "Default")
      (node (ref "TP29") (pin "TESTPOINT") (pinfunction "TESTPOINT_TESTPOINT") (pintype "bidirectional"))
      (node (ref "U1") (pin "41") (pinfunction "PORTPWR_41") (pintype "bidirectional"))
    )
    (net (code "33") (name "HUB_~{OVRCUR1}") (class "Default")
      (node (ref "R29") (pin "1") (pinfunction "1_1") (pintype "passive"))
      (node (ref "S14") (pin "5") (pinfunction "~{FLG}_5") (pintype "bidirectional"))
      (node (ref "TP33") (pin "TESTPOINT") (pinfunction "TESTPOINT_TESTPOINT") (pintype "bidirectional"))
      (node (ref "U1") (pin "12") (pinfunction "~{OVRCUR1}_12") (pintype "bidirectional"))
    )
    (net (code "34") (name "HUB_~{OVRCUR2}") (class "Default")
      (node (ref "R28") (pin "1") (pinfunction "1_1") (pintype "passive"))
      (node (ref "S13") (pin "5") (pinfunction "~{FLG}_5") (pintype "bidirectional"))
      (node (ref "TP35") (pin "TESTPOINT") (pinfunction "TESTPOINT_TESTPOINT") (pintype "bidirectional"))
      (node (ref "U1") (pin "16") (pinfunction "~{OVRCUR2}_16") (pintype "bidirectional"))
    )
    (net (code "35") (name "HUB_~{OVRCUR3}") (class "Default")
      (node (ref "R30") (pin "1") (pinfunction "1_1") (pintype "passive"))
      (node (ref "S15") (pin "5") (pinfunction "~{FLG}_5") (pintype "bidirectional"))
      (node (ref "TP37") (pin "TESTPOINT") (pinfunction "TESTPOINT_TESTPOINT") (pintype "bidirectional"))
      (node (ref "U1") (pin "20") (pinfunction "~{OVRCUR3}_20") (pintype "bidirectional"))
    )
    (net (code "36") (name "HUB_~{OVRCUR4}") (class "Default")
      (node (ref "R32") (pin "1") (pinfunction "1_1") (pintype "passive"))
      (node (ref "S17") (pin "5") (pinfunction "~{FLG}_5") (pintype "bidirectional"))
      (node (ref "TP39") (pin "TESTPOINT") (pinfunction "TESTPOINT_TESTPOINT") (pintype "bidirectional"))
      (node (ref "U1") (pin "25") (pinfunction "~{OVRCUR4}_25") (pintype "bidirectional"))
    )
    (net (code "37") (name "HUB_~{OVRCUR5}") (class "Default")
      (node (ref "R51") (pin "1") (pinfunction "1_1") (pintype "passive"))
      (node (ref "U1") (pin "29") (pinfunction "~{OVRCUR5}_29") (pintype "bidirectional"))
    )
    (net (code "38") (name "HUB_~{OVRCUR6}") (class "Default")
      (node (ref "R33") (pin "1") (pinfunction "1_1") (pintype "passive"))
      (node (ref "S18") (pin "5") (pinfunction "~{FLG}_5") (pintype "bidirectional"))
      (node (ref "TP41") (pin "TESTPOINT") (pinfunction "TESTPOINT_TESTPOINT") (pintype "bidirectional"))
      (node (ref "U1") (pin "33") (pinfunction "~{OVRCUR6}_33") (pintype "bidirectional"))
    )
    (net (code "39") (name "HUB_~{OVRCUR7}") (class "Default")
      (node (ref "R31") (pin "1") (pinfunction "1_1") (pintype "passive"))
      (node (ref "S16") (pin "5") (pinfunction "~{FLG}_5") (pintype "bidirectional"))
      (node (ref "TP43") (pin "TESTPOINT") (pinfunction "TESTPOINT_TESTPOINT") (pintype "bidirectional"))
      (node (ref "U1") (pin "37") (pinfunction "~{OVRCUR7}_37") (pintype "bidirectional"))
    )
    (net (code "40") (name "HUB_~{PWRON1}") (class "Default")
      (node (ref "S8") (pin "1") (pinfunction "I1_1") (pintype "bidirectional"))
      (node (ref "TP32") (pin "TESTPOINT") (pinfunction "TESTPOINT_TESTPOINT") (pintype "bidirectional"))
      (node (ref "U1") (pin "11") (pinfunction "~{PWRON1}_11") (pintype "bidirectional"))
    )
    (net (code "41") (name "HUB_~{PWRON2}") (class "Default")
      (node (ref "S7") (pin "1") (pinfunction "I1_1") (pintype "bidirectional"))
      (node (ref "TP34") (pin "TESTPOINT") (pinfunction "TESTPOINT_TESTPOINT") (pintype "bidirectional"))
      (node (ref "U1") (pin "15") (pinfunction "~{PWRON2}_15") (pintype "bidirectional"))
    )
    (net (code "42") (name "HUB_~{PWRON3}") (class "Default")
      (node (ref "S9") (pin "1") (pinfunction "I1_1") (pintype "bidirectional"))
      (node (ref "TP36") (pin "TESTPOINT") (pinfunction "TESTPOINT_TESTPOINT") (pintype "bidirectional"))
      (node (ref "U1") (pin "19") (pinfunction "~{PWRON3}_19") (pintype "bidirectional"))
    )
    (net (code "43") (name "HUB_~{PWRON4}") (class "Default")
      (node (ref "S11") (pin "1") (pinfunction "I1_1") (pintype "bidirectional"))
      (node (ref "TP38") (pin "TESTPOINT") (pinfunction "TESTPOINT_TESTPOINT") (pintype "bidirectional"))
      (node (ref "U1") (pin "23") (pinfunction "~{PWRON4}_23") (pintype "bidirectional"))
    )
    (net (code "44") (name "HUB_~{PWRON5}") (class "Default")
      (node (ref "U1") (pin "28") (pinfunction "~{PWRON5}_28") (pintype "bidirectional"))
    )
    (net (code "45") (name "HUB_~{PWRON6}") (class "Default")
      (node (ref "S12") (pin "1") (pinfunction "I1_1") (pintype "bidirectional"))
      (node (ref "TP40") (pin "TESTPOINT") (pinfunction "TESTPOINT_TESTPOINT") (pintype "bidirectional"))
      (node (ref "U1") (pin "32") (pinfunction "~{PWRON6}_32") (pintype "bidirectional"))
    )
    (net (code "46") (name "HUB_~{PWRON7}") (class "Default")
      (node (ref "S10") (pin "1") (pinfunction "I1_1") (pintype "bidirectional"))
      (node (ref "TP42") (pin "TESTPOINT") (pinfunction "TESTPOINT_TESTPOINT") (pintype "bidirectional"))
      (node (ref "U1") (pin "36") (pinfunction "~{PWRON7}_36") (pintype "bidirectional"))
    )
    (net (code "47") (name "MOD0_5V") (class "Default")
      (node (ref "C33") (pin "1") (pinfunction "1_1") (pintype "bidirectional"))
      (node (ref "J0") (pin "2") (pinfunction "5V_2") (pintype "bidirectional"))
      (node (ref "S1") (pin "1") (pinfunction "VLOAD_1") (pintype "bidirectional"))
    )
    (net (code "48") (name "MOD0_5V_METERED") (class "Default")
      (node (ref "C76") (pin "1") (pinfunction "1_1") (pintype "bidirectional"))
      (node (ref "C88") (pin "1") (pinfunction "1_1") (pintype "bidirectional"))
      (node (ref "J4") (pin "7") (pinfunction "VCC_MOD0_7") (pintype "power_in"))
      (node (ref "S1") (pin "3") (pinfunction "VSUPP_3") (pintype "bidirectional"))
      (node (ref "S13") (pin "2") (pinfunction "IN_2") (pintype "bidirectional"))
      (node (ref "S13") (pin "3") (pinfunction "IN_3") (pintype "bidirectional"))
      (node (ref "TP16") (pin "TESTPOINT") (pinfunction "TESTPOINT_TESTPOINT") (pintype "bidirectional"))
    )
    (net (code "49") (name "MOD0_D+_HUB-SW") (class "Default")
      (node (ref "D1") (pin "4") (pinfunction "D_4") (pintype "bidirectional"))
      (node (ref "R1") (pin "2") (pinfunction "2_2") (pintype "passive"))
      (node (ref "R52") (pin "2") (pinfunction "2_2") (pintype "passive"))
      (node (ref "U20") (pin "3") (pinfunction "D+_3") (pintype "bidirectional"))
    )
    (net (code "50") (name "MOD0_D-_HUB-SW") (class "Default")
      (node (ref "D1") (pin "2") (pinfunction "C_2") (pintype "bidirectional"))
      (node (ref "R2") (pin "2") (pinfunction "2_2") (pintype "passive"))
      (node (ref "R53") (pin "2") (pinfunction "2_2") (pintype "passive"))
      (node (ref "U20") (pin "5") (pinfunction "D-_5") (pintype "bidirectional"))
    )
    (net (code "51") (name "MOD0_IN") (class "Default")
      (node (ref "J0") (pin "10") (pinfunction "MOD_IN_10") (pintype "bidirectional"))
      (node (ref "U8") (pin "7") (pinfunction "B1_7") (pintype "bidirectional"))
    )
    (net (code "52") (name "MOD0_ISO_I2C") (class "Default")
      (node (ref "R1002") (pin "2") (pinfunction "2_2") (pintype "passive"))
      (node (ref "R67") (pin "2") (pinfunction "2_2") (pintype "passive"))
      (node (ref "TP1002") (pin "TESTPOINT") (pinfunction "TESTPOINT_TESTPOINT") (pintype "bidirectional"))
      (node (ref "U2") (pin "5") (pinfunction "OE_5") (pintype "bidirectional"))
      (node (ref "U26") (pin "11") (pinfunction "P1_11") (pintype "bidirectional"))
    )
    (net (code "53") (name "MOD0_ISO_POWER") (class "Default")
      (node (ref "R1001") (pin "2") (pinfunction "2_2") (pintype "passive"))
      (node (ref "R66") (pin "2") (pinfunction "2_2") (pintype "passive"))
      (node (ref "S1") (pin "4") (pinfunction "EN_4") (pintype "bidirectional"))
      (node (ref "TP1001") (pin "TESTPOINT") (pinfunction "TESTPOINT_TESTPOINT") (pintype "bidirectional"))
      (node (ref "U26") (pin "10") (pinfunction "P0_10") (pintype "bidirectional"))
    )
    (net (code "54") (name "MOD0_ISO_USB") (class "Default")
      (node (ref "R1003") (pin "2") (pinfunction "2_2") (pintype "passive"))
      (node (ref "R68") (pin "2") (pinfunction "2_2") (pintype "passive"))
      (node (ref "S7") (pin "6") (pinfunction "S_6") (pintype "bidirectional"))
      (node (ref "TP1003") (pin "TESTPOINT") (pinfunction "TESTPOINT_TESTPOINT") (pintype "bidirectional"))
      (node (ref "U26") (pin "12") (pinfunction "P2_12") (pintype "bidirectional"))
    )
    (net (code "55") (name "MOD0_OUT") (class "Default")
      (node (ref "J0") (pin "8") (pinfunction "MOD_OUT_8") (pintype "bidirectional"))
      (node (ref "U14") (pin "7") (pinfunction "B1_7") (pintype "bidirectional"))
    )
    (net (code "56") (name "MOD0_PPS") (class "Default")
      (node (ref "J0") (pin "7") (pinfunction "PPS_7") (pintype "bidirectional"))
      (node (ref "U8") (pin "6") (pinfunction "B2_6") (pintype "bidirectional"))
    )
    (net (code "57") (name "MOD0_SCL") (class "Default")
      (node (ref "J0") (pin "5") (pinfunction "SCL_5") (pintype "bidirectional"))
      (node (ref "R35") (pin "2") (pinfunction "2_2") (pintype "passive"))
      (node (ref "U2") (pin "6") (pinfunction "B1_6") (pintype "bidirectional"))
    )
    (net (code "58") (name "MOD0_SDA") (class "Default")
      (node (ref "J0") (pin "6") (pinfunction "SDA_6") (pintype "bidirectional"))
      (node (ref "R34") (pin "2") (pinfunction "2_2") (pintype "passive"))
      (node (ref "U2") (pin "7") (pinfunction "B0_7") (pintype "bidirectional"))
    )
    (net (code "59") (name "MOD0_USB+") (class "Default")
      (node (ref "J0") (pin "11") (pinfunction "USB_D+_11") (pintype "bidirectional"))
      (node (ref "U20") (pin "1") (pinfunction "D1+_1") (pintype "bidirectional"))
    )
    (net (code "60") (name "MOD0_USB-") (class "Default")
      (node (ref "J0") (pin "12") (pinfunction "USB_D-_12") (pintype "bidirectional"))
      (node (ref "U20") (pin "7") (pinfunction "D1-_7") (pintype "bidirectional"))
    )
    (net (code "61") (name "MOD0_USB_VBUS") (class "Default")
      (node (ref "C77") (pin "1") (pinfunction "1_1") (pintype "bidirectional"))
      (node (ref "C95") (pin "1") (pinfunction "1_1") (pintype "bidirectional"))
      (node (ref "J0") (pin "13") (pinfunction "USB_VBUS_13") (pintype "bidirectional"))
      (node (ref "S13") (pin "6") (pinfunction "OUT_6") (pintype "bidirectional"))
      (node (ref "S13") (pin "7") (pinfunction "OUT_7") (pintype "bidirectional"))
    )
    (net (code "62") (name "MOD0_USB_~{EN}") (class "Default")
      (node (ref "S13") (pin "4") (pinfunction "~{EN}_4") (pintype "bidirectional"))
      (node (ref "S7") (pin "4") (pinfunction "Z_4") (pintype "bidirectional"))
      (node (ref "U20") (pin "8") (pinfunction "~{OE}_8") (pintype "bidirectional"))
    )
    (net (code "63") (name "MOD0_VCCIO") (class "Default")
      (node (ref "C22") (pin "1") (pinfunction "1_1") (pintype "bidirectional"))
      (node (ref "C40") (pin "1") (pinfunction "1_1") (pintype "bidirectional"))
      (node (ref "C52") (pin "1") (pinfunction "1_1") (pintype "bidirectional"))
      (node (ref "J0") (pin "4") (pinfunction "VCCIO_4") (pintype "bidirectional"))
      (node (ref "R34") (pin "1") (pinfunction "1_1") (pintype "passive"))
      (node (ref "R35") (pin "1") (pinfunction "1_1") (pintype "passive"))
      (node (ref "U14") (pin "8") (pinfunction "VCC_B_8") (pintype "bidirectional"))
      (node (ref "U2") (pin "8") (pinfunction "VCC_B_8") (pintype "bidirectional"))
      (node (ref "U8") (pin "8") (pinfunction "VCC_B_8") (pintype "bidirectional"))
    )
    (net (code "64") (name "MOD1_5V") (class "Default")
      (node (ref "C34") (pin "1") (pinfunction "1_1") (pintype "bidirectional"))
      (node (ref "J1") (pin "2") (pinfunction "5V_2") (pintype "bidirectional"))
      (node (ref "S2") (pin "1") (pinfunction "VLOAD_1") (pintype "bidirectional"))
    )
    (net (code "65") (name "MOD1_5V_METERED") (class "Default")
      (node (ref "C78") (pin "1") (pinfunction "1_1") (pintype "bidirectional"))
      (node (ref "C89") (pin "1") (pinfunction "1_1") (pintype "bidirectional"))
      (node (ref "J4") (pin "8") (pinfunction "VCC_MOD1_8") (pintype "power_in"))
      (node (ref "S14") (pin "2") (pinfunction "IN_2") (pintype "bidirectional"))
      (node (ref "S14") (pin "3") (pinfunction "IN_3") (pintype "bidirectional"))
      (node (ref "S2") (pin "3") (pinfunction "VSUPP_3") (pintype "bidirectional"))
      (node (ref "TP17") (pin "TESTPOINT") (pinfunction "TESTPOINT_TESTPOINT") (pintype "bidirectional"))
    )
    (net (code "66") (name "MOD1_D+_HUB-SW") (class "Default")
      (node (ref "D1") (pin "8") (pinfunction "A_8") (pintype "bidirectional"))
      (node (ref "R3") (pin "2") (pinfunction "2_2") (pintype "passive"))
      (node (ref "R54") (pin "2") (pinfunction "2_2") (pintype "passive"))
      (node (ref "U21") (pin "3") (pinfunction "D+_3") (pintype "bidirectional"))
    )
    (net (code "67") (name "MOD1_D-_HUB-SW") (class "Default")
      (node (ref "D1") (pin "6") (pinfunction "B_6") (pintype "bidirectional"))
      (node (ref "R4") (pin "2") (pinfunction "2_2") (pintype "passive"))
      (node (ref "R55") (pin "2") (pinfunction "2_2") (pintype "passive"))
      (node (ref "U21") (pin "5") (pinfunction "D-_5") (pintype "bidirectional"))
    )
    (net (code "68") (name "MOD1_IN") (class "Default")
      (node (ref "J1") (pin "10") (pinfunction "MOD_IN_10") (pintype "bidirectional"))
      (node (ref "U9") (pin "7") (pinfunction "B1_7") (pintype "bidirectional"))
    )
    (net (code "69") (name "MOD1_ISO_I2C") (class "Default")
      (node (ref "LED1005") (pin "A") (pinfunction "ANODE_A") (pintype "bidirectional"))
      (node (ref "R70") (pin "2") (pinfunction "2_2") (pintype "passive"))
      (node (ref "TP1005") (pin "TESTPOINT") (pinfunction "TESTPOINT_TESTPOINT") (pintype "bidirectional"))
      (node (ref "U27") (pin "11") (pinfunction "P1_11") (pintype "bidirectional"))
      (node (ref "U3") (pin "5") (pinfunction "OE_5") (pintype "bidirectional"))
    )
    (net (code "70") (name "MOD1_ISO_POWER") (class "Default")
      (node (ref "LED1004") (pin "A") (pinfunction "ANODE_A") (pintype "bidirectional"))
      (node (ref "R69") (pin "2") (pinfunction "2_2") (pintype "passive"))
      (node (ref "S2") (pin "4") (pinfunction "EN_4") (pintype "bidirectional"))
      (node (ref "TP1004") (pin "TESTPOINT") (pinfunction "TESTPOINT_TESTPOINT") (pintype "bidirectional"))
      (node (ref "U27") (pin "10") (pinfunction "P0_10") (pintype "bidirectional"))
    )
    (net (code "71") (name "MOD1_ISO_USB") (class "Default")
      (node (ref "LED1006") (pin "A") (pinfunction "ANODE_A") (pintype "bidirectional"))
      (node (ref "R71") (pin "2") (pinfunction "2_2") (pintype "passive"))
      (node (ref "S8") (pin "6") (pinfunction "S_6") (pintype "bidirectional"))
      (node (ref "TP1006") (pin "TESTPOINT") (pinfunction "TESTPOINT_TESTPOINT") (pintype "bidirectional"))
      (node (ref "U27") (pin "12") (pinfunction "P2_12") (pintype "bidirectional"))
    )
    (net (code "72") (name "MOD1_OUT") (class "Default")
      (node (ref "J1") (pin "8") (pinfunction "MOD_OUT_8") (pintype "bidirectional"))
      (node (ref "U15") (pin "7") (pinfunction "B1_7") (pintype "bidirectional"))
    )
    (net (code "73") (name "MOD1_PPS") (class "Default")
      (node (ref "J1") (pin "7") (pinfunction "PPS_7") (pintype "bidirectional"))
      (node (ref "U9") (pin "6") (pinfunction "B2_6") (pintype "bidirectional"))
    )
    (net (code "74") (name "MOD1_SCL") (class "Default")
      (node (ref "J1") (pin "5") (pinfunction "SCL_5") (pintype "bidirectional"))
      (node (ref "R37") (pin "2") (pinfunction "2_2") (pintype "passive"))
      (node (ref "U3") (pin "6") (pinfunction "B1_6") (pintype "bidirectional"))
    )
    (net (code "75") (name "MOD1_SDA") (class "Default")
      (node (ref "J1") (pin "6") (pinfunction "SDA_6") (pintype "bidirectional"))
      (node (ref "R36") (pin "2") (pinfunction "2_2") (pintype "passive"))
      (node (ref "U3") (pin "7") (pinfunction "B0_7") (pintype "bidirectional"))
    )
    (net (code "76") (name "MOD1_USB+") (class "Default")
      (node (ref "J1") (pin "11") (pinfunction "USB_D+_11") (pintype "bidirectional"))
      (node (ref "U21") (pin "1") (pinfunction "D1+_1") (pintype "bidirectional"))
    )
    (net (code "77") (name "MOD1_USB-") (class "Default")
      (node (ref "J1") (pin "12") (pinfunction "USB_D-_12") (pintype "bidirectional"))
      (node (ref "U21") (pin "7") (pinfunction "D1-_7") (pintype "bidirectional"))
    )
    (net (code "78") (name "MOD1_USB_VBUS") (class "Default")
      (node (ref "C79") (pin "1") (pinfunction "1_1") (pintype "bidirectional"))
      (node (ref "C96") (pin "1") (pinfunction "1_1") (pintype "bidirectional"))
      (node (ref "J1") (pin "13") (pinfunction "USB_VBUS_13") (pintype "bidirectional"))
      (node (ref "S14") (pin "6") (pinfunction "OUT_6") (pintype "bidirectional"))
      (node (ref "S14") (pin "7") (pinfunction "OUT_7") (pintype "bidirectional"))
    )
    (net (code "79") (name "MOD1_USB_~{EN}") (class "Default")
      (node (ref "S14") (pin "4") (pinfunction "~{EN}_4") (pintype "bidirectional"))
      (node (ref "S8") (pin "4") (pinfunction "Z_4") (pintype "bidirectional"))
      (node (ref "U21") (pin "8") (pinfunction "~{OE}_8") (pintype "bidirectional"))
    )
    (net (code "80") (name "MOD1_VCCIO") (class "Default")
      (node (ref "C24") (pin "1") (pinfunction "1_1") (pintype "bidirectional"))
      (node (ref "C42") (pin "1") (pinfunction "1_1") (pintype "bidirectional"))
      (node (ref "C54") (pin "1") (pinfunction "1_1") (pintype "bidirectional"))
      (node (ref "J1") (pin "4") (pinfunction "VCCIO_4") (pintype "bidirectional"))
      (node (ref "R36") (pin "1") (pinfunction "1_1") (pintype "passive"))
      (node (ref "R37") (pin "1") (pinfunction "1_1") (pintype "passive"))
      (node (ref "U15") (pin "8") (pinfunction "VCC_B_8") (pintype "bidirectional"))
      (node (ref "U3") (pin "8") (pinfunction "VCC_B_8") (pintype "bidirectional"))
      (node (ref "U9") (pin "8") (pinfunction "VCC_B_8") (pintype "bidirectional"))
    )
    (net (code "81") (name "MOD2_5V") (class "Default")
      (node (ref "C35") (pin "1") (pinfunction "1_1") (pintype "bidirectional"))
      (node (ref "J2") (pin "2") (pinfunction "5V_2") (pintype "bidirectional"))
      (node (ref "S3") (pin "1") (pinfunction "VLOAD_1") (pintype "bidirectional"))
    )
    (net (code "82") (name "MOD2_5V_METERED") (class "Default")
      (node (ref "C80") (pin "1") (pinfunction "1_1") (pintype "bidirectional"))
      (node (ref "C90") (pin "1") (pinfunction "1_1") (pintype "bidirectional"))
      (node (ref "J4") (pin "9") (pinfunction "VCC_MOD2_9") (pintype "power_in"))
      (node (ref "S15") (pin "2") (pinfunction "IN_2") (pintype "bidirectional"))
      (node (ref "S15") (pin "3") (pinfunction "IN_3") (pintype "bidirectional"))
      (node (ref "S3") (pin "3") (pinfunction "VSUPP_3") (pintype "bidirectional"))
      (node (ref "TP18") (pin "TESTPOINT") (pinfunction "TESTPOINT_TESTPOINT") (pintype "bidirectional"))
    )
    (net (code "83") (name "MOD2_D+_HUB-SW") (class "Default")
      (node (ref "D2") (pin "8") (pinfunction "A_8") (pintype "bidirectional"))
      (node (ref "R5") (pin "2") (pinfunction "2_2") (pintype "passive"))
      (node (ref "R56") (pin "2") (pinfunction "2_2") (pintype "passive"))
      (node (ref "U22") (pin "3") (pinfunction "D+_3") (pintype "bidirectional"))
    )
    (net (code "84") (name "MOD2_D-_HUB-SW") (class "Default")
      (node (ref "D2") (pin "6") (pinfunction "B_6") (pintype "bidirectional"))
      (node (ref "R57") (pin "2") (pinfunction "2_2") (pintype "passive"))
      (node (ref "R6") (pin "2") (pinfunction "2_2") (pintype "passive"))
      (node (ref "U22") (pin "5") (pinfunction "D-_5") (pintype "bidirectional"))
    )
    (net (code "85") (name "MOD2_IN") (class "Default")
      (node (ref "J2") (pin "10") (pinfunction "MOD_IN_10") (pintype "bidirectional"))
      (node (ref "U10") (pin "7") (pinfunction "B1_7") (pintype "bidirectional"))
    )
    (net (code "86") (name "MOD2_ISO_I2C") (class "Default")
      (node (ref "R1008") (pin "2") (pinfunction "2_2") (pintype "passive"))
      (node (ref "R73") (pin "2") (pinfunction "2_2") (pintype "passive"))
      (node (ref "TP1008") (pin "TESTPOINT") (pinfunction "TESTPOINT_TESTPOINT") (pintype "bidirectional"))
      (node (ref "U28") (pin "11") (pinfunction "P1_11") (pintype "bidirectional"))
      (node (ref "U4") (pin "5") (pinfunction "OE_5") (pintype "bidirectional"))
    )
    (net (code "87") (name "MOD2_ISO_POWER") (class "Default")
      (node (ref "R1007") (pin "2") (pinfunction "2_2") (pintype "passive"))
      (node (ref "R72") (pin "2") (pinfunction "2_2") (pintype "passive"))
      (node (ref "S3") (pin "4") (pinfunction "EN_4") (pintype "bidirectional"))
      (node (ref "TP1007") (pin "TESTPOINT") (pinfunction "TESTPOINT_TESTPOINT") (pintype "bidirectional"))
      (node (ref "U28") (pin "10") (pinfunction "P0_10") (pintype "bidirectional"))
    )
    (net (code "88") (name "MOD2_ISO_USB") (class "Default")
      (node (ref "R1009") (pin "2") (pinfunction "2_2") (pintype "passive"))
      (node (ref "R74") (pin "2") (pinfunction "2_2") (pintype "passive"))
      (node (ref "S9") (pin "6") (pinfunction "S_6") (pintype "bidirectional"))
      (node (ref "TP1009") (pin "TESTPOINT") (pinfunction "TESTPOINT_TESTPOINT") (pintype "bidirectional"))
      (node (ref "U28") (pin "12") (pinfunction "P2_12") (pintype "bidirectional"))
    )
    (net (code "89") (name "MOD2_OUT") (class "Default")
      (node (ref "J2") (pin "8") (pinfunction "MOD_OUT_8") (pintype "bidirectional"))
      (node (ref "U16") (pin "7") (pinfunction "B1_7") (pintype "bidirectional"))
    )
    (net (code "90") (name "MOD2_PPS") (class "Default")
      (node (ref "J2") (pin "7") (pinfunction "PPS_7") (pintype "bidirectional"))
      (node (ref "U10") (pin "6") (pinfunction "B2_6") (pintype "bidirectional"))
    )
    (net (code "91") (name "MOD2_SCL") (class "Default")
      (node (ref "J2") (pin "5") (pinfunction "SCL_5") (pintype "bidirectional"))
      (node (ref "R39") (pin "2") (pinfunction "2_2") (pintype "passive"))
      (node (ref "U4") (pin "6") (pinfunction "B1_6") (pintype "bidirectional"))
    )
    (net (code "92") (name "MOD2_SDA") (class "Default")
      (node (ref "J2") (pin "6") (pinfunction "SDA_6") (pintype "bidirectional"))
      (node (ref "R38") (pin "2") (pinfunction "2_2") (pintype "passive"))
      (node (ref "U4") (pin "7") (pinfunction "B0_7") (pintype "bidirectional"))
    )
    (net (code "93") (name "MOD2_USB+") (class "Default")
      (node (ref "J2") (pin "11") (pinfunction "USB_D+_11") (pintype "bidirectional"))
      (node (ref "U22") (pin "1") (pinfunction "D1+_1") (pintype "bidirectional"))
    )
    (net (code "94") (name "MOD2_USB-") (class "Default")
      (node (ref "J2") (pin "12") (pinfunction "USB_D-_12") (pintype "bidirectional"))
      (node (ref "U22") (pin "7") (pinfunction "D1-_7") (pintype "bidirectional"))
    )
    (net (code "95") (name "MOD2_USB_VBUS") (class "Default")
      (node (ref "C81") (pin "1") (pinfunction "1_1") (pintype "bidirectional"))
      (node (ref "C97") (pin "1") (pinfunction "1_1") (pintype "bidirectional"))
      (node (ref "J2") (pin "13") (pinfunction "USB_VBUS_13") (pintype "bidirectional"))
      (node (ref "S15") (pin "6") (pinfunction "OUT_6") (pintype "bidirectional"))
      (node (ref "S15") (pin "7") (pinfunction "OUT_7") (pintype "bidirectional"))
    )
    (net (code "96") (name "MOD2_USB_~{EN}") (class "Default")
      (node (ref "S15") (pin "4") (pinfunction "~{EN}_4") (pintype "bidirectional"))
      (node (ref "S9") (pin "4") (pinfunction "Z_4") (pintype "bidirectional"))
      (node (ref "U22") (pin "8") (pinfunction "~{OE}_8") (pintype "bidirectional"))
    )
    (net (code "97") (name "MOD2_VCCIO") (class "Default")
      (node (ref "C26") (pin "1") (pinfunction "1_1") (pintype "bidirectional"))
      (node (ref "C44") (pin "1") (pinfunction "1_1") (pintype "bidirectional"))
      (node (ref "C56") (pin "1") (pinfunction "1_1") (pintype "bidirectional"))
      (node (ref "J2") (pin "4") (pinfunction "VCCIO_4") (pintype "bidirectional"))
      (node (ref "R38") (pin "1") (pinfunction "1_1") (pintype "passive"))
      (node (ref "R39") (pin "1") (pinfunction "1_1") (pintype "passive"))
      (node (ref "U10") (pin "8") (pinfunction "VCC_B_8") (pintype "bidirectional"))
      (node (ref "U16") (pin "8") (pinfunction "VCC_B_8") (pintype "bidirectional"))
      (node (ref "U4") (pin "8") (pinfunction "VCC_B_8") (pintype "bidirectional"))
    )
    (net (code "98") (name "MOD5_5V") (class "Default")
      (node (ref "C36") (pin "1") (pinfunction "1_1") (pintype "bidirectional"))
      (node (ref "J5") (pin "2") (pinfunction "5V_2") (pintype "bidirectional"))
      (node (ref "S4") (pin "1") (pinfunction "VLOAD_1") (pintype "bidirectional"))
    )
    (net (code "99") (name "MOD5_5V_METERED") (class "Default")
      (node (ref "C82") (pin "1") (pinfunction "1_1") (pintype "bidirectional"))
      (node (ref "C91") (pin "1") (pinfunction "1_1") (pintype "bidirectional"))
      (node (ref "J4") (pin "10") (pinfunction "VCC_MOD5_10") (pintype "power_in"))
      (node (ref "S16") (pin "2") (pinfunction "IN_2") (pintype "bidirectional"))
      (node (ref "S16") (pin "3") (pinfunction "IN_3") (pintype "bidirectional"))
      (node (ref "S4") (pin "3") (pinfunction "VSUPP_3") (pintype "bidirectional"))
      (node (ref "TP19") (pin "TESTPOINT") (pinfunction "TESTPOINT_TESTPOINT") (pintype "bidirectional"))
    )
    (net (code "100") (name "MOD5_D+_HUB-SW") (class "Default")
      (node (ref "D3") (pin "2") (pinfunction "C_2") (pintype "bidirectional"))
      (node (ref "R58") (pin "2") (pinfunction "2_2") (pintype "passive"))
      (node (ref "R7") (pin "2") (pinfunction "2_2") (pintype "passive"))
      (node (ref "U23") (pin "3") (pinfunction "D+_3") (pintype "bidirectional"))
    )
    (net (code "101") (name "MOD5_D-_HUB-SW") (class "Default")
      (node (ref "D3") (pin "4") (pinfunction "D_4") (pintype "bidirectional"))
      (node (ref "R59") (pin "2") (pinfunction "2_2") (pintype "passive"))
      (node (ref "R8") (pin "2") (pinfunction "2_2") (pintype "passive"))
      (node (ref "U23") (pin "5") (pinfunction "D-_5") (pintype "bidirectional"))
    )
    (net (code "102") (name "MOD5_IN") (class "Default")
      (node (ref "J5") (pin "10") (pinfunction "MOD_IN_10") (pintype "bidirectional"))
      (node (ref "U11") (pin "7") (pinfunction "B1_7") (pintype "bidirectional"))
    )
    (net (code "103") (name "MOD5_ISO_I2C") (class "Default")
      (node (ref "LED1011") (pin "A") (pinfunction "ANODE_A") (pintype "bidirectional"))
      (node (ref "R76") (pin "2") (pinfunction "2_2") (pintype "passive"))
      (node (ref "TP1011") (pin "TESTPOINT") (pinfunction "TESTPOINT_TESTPOINT") (pintype "bidirectional"))
      (node (ref "U29") (pin "11") (pinfunction "P1_11") (pintype "bidirectional"))
      (node (ref "U5") (pin "5") (pinfunction "OE_5") (pintype "bidirectional"))
    )
    (net (code "104") (name "MOD5_ISO_POWER") (class "Default")
      (node (ref "LED1010") (pin "A") (pinfunction "ANODE_A") (pintype "bidirectional"))
      (node (ref "R75") (pin "2") (pinfunction "2_2") (pintype "passive"))
      (node (ref "S4") (pin "4") (pinfunction "EN_4") (pintype "bidirectional"))
      (node (ref "TP1010") (pin "TESTPOINT") (pinfunction "TESTPOINT_TESTPOINT") (pintype "bidirectional"))
      (node (ref "U29") (pin "10") (pinfunction "P0_10") (pintype "bidirectional"))
    )
    (net (code "105") (name "MOD5_ISO_USB") (class "Default")
      (node (ref "LED1012") (pin "A") (pinfunction "ANODE_A") (pintype "bidirectional"))
      (node (ref "R77") (pin "2") (pinfunction "2_2") (pintype "passive"))
      (node (ref "S10") (pin "6") (pinfunction "S_6") (pintype "bidirectional"))
      (node (ref "TP1012") (pin "TESTPOINT") (pinfunction "TESTPOINT_TESTPOINT") (pintype "bidirectional"))
      (node (ref "U29") (pin "12") (pinfunction "P2_12") (pintype "bidirectional"))
    )
    (net (code "106") (name "MOD5_OUT") (class "Default")
      (node (ref "J5") (pin "8") (pinfunction "MOD_OUT_8") (pintype "bidirectional"))
      (node (ref "U17") (pin "7") (pinfunction "B1_7") (pintype "bidirectional"))
    )
    (net (code "107") (name "MOD5_PPS") (class "Default")
      (node (ref "J5") (pin "7") (pinfunction "PPS_7") (pintype "bidirectional"))
      (node (ref "U11") (pin "6") (pinfunction "B2_6") (pintype "bidirectional"))
    )
    (net (code "108") (name "MOD5_SCL") (class "Default")
      (node (ref "J5") (pin "5") (pinfunction "SCL_5") (pintype "bidirectional"))
      (node (ref "R41") (pin "2") (pinfunction "2_2") (pintype "passive"))
      (node (ref "U5") (pin "6") (pinfunction "B1_6") (pintype "bidirectional"))
    )
    (net (code "109") (name "MOD5_SDA") (class "Default")
      (node (ref "J5") (pin "6") (pinfunction "SDA_6") (pintype "bidirectional"))
      (node (ref "R40") (pin "2") (pinfunction "2_2") (pintype "passive"))
      (node (ref "U5") (pin "7") (pinfunction "B0_7") (pintype "bidirectional"))
    )
    (net (code "110") (name "MOD5_USB+") (class "Default")
      (node (ref "J5") (pin "11") (pinfunction "USB_D+_11") (pintype "bidirectional"))
      (node (ref "U23") (pin "1") (pinfunction "D1+_1") (pintype "bidirectional"))
    )
    (net (code "111") (name "MOD5_USB-") (class "Default")
      (node (ref "J5") (pin "12") (pinfunction "USB_D-_12") (pintype "bidirectional"))
      (node (ref "U23") (pin "7") (pinfunction "D1-_7") (pintype "bidirectional"))
    )
    (net (code "112") (name "MOD5_USB_VBUS") (class "Default")
      (node (ref "C83") (pin "1") (pinfunction "1_1") (pintype "bidirectional"))
      (node (ref "C98") (pin "1") (pinfunction "1_1") (pintype "bidirectional"))
      (node (ref "J5") (pin "13") (pinfunction "USB_VBUS_13") (pintype "bidirectional"))
      (node (ref "S16") (pin "6") (pinfunction "OUT_6") (pintype "bidirectional"))
      (node (ref "S16") (pin "7") (pinfunction "OUT_7") (pintype "bidirectional"))
    )
    (net (code "113") (name "MOD5_USB_~{EN}") (class "Default")
      (node (ref "S10") (pin "4") (pinfunction "Z_4") (pintype "bidirectional"))
      (node (ref "S16") (pin "4") (pinfunction "~{EN}_4") (pintype "bidirectional"))
      (node (ref "U23") (pin "8") (pinfunction "~{OE}_8") (pintype "bidirectional"))
    )
    (net (code "114") (name "MOD5_VCCIO") (class "Default")
      (node (ref "C28") (pin "1") (pinfunction "1_1") (pintype "bidirectional"))
      (node (ref "C46") (pin "1") (pinfunction "1_1") (pintype "bidirectional"))
      (node (ref "C58") (pin "1") (pinfunction "1_1") (pintype "bidirectional"))
      (node (ref "J5") (pin "4") (pinfunction "VCCIO_4") (pintype "bidirectional"))
      (node (ref "R40") (pin "1") (pinfunction "1_1") (pintype "passive"))
      (node (ref "R41") (pin "1") (pinfunction "1_1") (pintype "passive"))
      (node (ref "U11") (pin "8") (pinfunction "VCC_B_8") (pintype "bidirectional"))
      (node (ref "U17") (pin "8") (pinfunction "VCC_B_8") (pintype "bidirectional"))
      (node (ref "U5") (pin "8") (pinfunction "VCC_B_8") (pintype "bidirectional"))
    )
    (net (code "115") (name "MOD6_5V") (class "Default")
      (node (ref "C37") (pin "1") (pinfunction "1_1") (pintype "bidirectional"))
      (node (ref "J6") (pin "2") (pinfunction "5V_2") (pintype "bidirectional"))
      (node (ref "S5") (pin "1") (pinfunction "VLOAD_1") (pintype "bidirectional"))
    )
    (net (code "116") (name "MOD6_5V_METERED") (class "Default")
      (node (ref "C84") (pin "1") (pinfunction "1_1") (pintype "bidirectional"))
      (node (ref "C92") (pin "1") (pinfunction "1_1") (pintype "bidirectional"))
      (node (ref "J4") (pin "11") (pinfunction "VCC_MOD6_11") (pintype "power_in"))
      (node (ref "S17") (pin "2") (pinfunction "IN_2") (pintype "bidirectional"))
      (node (ref "S17") (pin "3") (pinfunction "IN_3") (pintype "bidirectional"))
      (node (ref "S5") (pin "3") (pinfunction "VSUPP_3") (pintype "bidirectional"))
      (node (ref "TP20") (pin "TESTPOINT") (pinfunction "TESTPOINT_TESTPOINT") (pintype "bidirectional"))
    )
    (net (code "117") (name "MOD6_D+_HUB-SW") (class "Default")
      (node (ref "D4") (pin "8") (pinfunction "A_8") (pintype "bidirectional"))
      (node (ref "R60") (pin "2") (pinfunction "2_2") (pintype "passive"))
      (node (ref "R9") (pin "2") (pinfunction "2_2") (pintype "passive"))
      (node (ref "U24") (pin "3") (pinfunction "D+_3") (pintype "bidirectional"))
    )
    (net (code "118") (name "MOD6_D-_HUB-SW") (class "Default")
      (node (ref "D4") (pin "6") (pinfunction "B_6") (pintype "bidirectional"))
      (node (ref "R10") (pin "2") (pinfunction "2_2") (pintype "passive"))
      (node (ref "R61") (pin "2") (pinfunction "2_2") (pintype "passive"))
      (node (ref "U24") (pin "5") (pinfunction "D-_5") (pintype "bidirectional"))
    )
    (net (code "119") (name "MOD6_IN") (class "Default")
      (node (ref "J6") (pin "10") (pinfunction "MOD_IN_10") (pintype "bidirectional"))
      (node (ref "U12") (pin "7") (pinfunction "B1_7") (pintype "bidirectional"))
    )
    (net (code "120") (name "MOD6_ISO_I2C") (class "Default")
      (node (ref "R1014") (pin "2") (pinfunction "2_2") (pintype "passive"))
      (node (ref "R79") (pin "2") (pinfunction "2_2") (pintype "passive"))
      (node (ref "TP1014") (pin "TESTPOINT") (pinfunction "TESTPOINT_TESTPOINT") (pintype "bidirectional"))
      (node (ref "U30") (pin "11") (pinfunction "P1_11") (pintype "bidirectional"))
      (node (ref "U6") (pin "5") (pinfunction "OE_5") (pintype "bidirectional"))
    )
    (net (code "121") (name "MOD6_ISO_POWER") (class "Default")
      (node (ref "R1013") (pin "2") (pinfunction "2_2") (pintype "passive"))
      (node (ref "R78") (pin "2") (pinfunction "2_2") (pintype "passive"))
      (node (ref "S5") (pin "4") (pinfunction "EN_4") (pintype "bidirectional"))
      (node (ref "TP1013") (pin "TESTPOINT") (pinfunction "TESTPOINT_TESTPOINT") (pintype "bidirectional"))
      (node (ref "U30") (pin "10") (pinfunction "P0_10") (pintype "bidirectional"))
    )
    (net (code "122") (name "MOD6_ISO_USB") (class "Default")
      (node (ref "R1015") (pin "2") (pinfunction "2_2") (pintype "passive"))
      (node (ref "R80") (pin "2") (pinfunction "2_2") (pintype "passive"))
      (node (ref "S11") (pin "6") (pinfunction "S_6") (pintype "bidirectional"))
      (node (ref "TP1015") (pin "TESTPOINT") (pinfunction "TESTPOINT_TESTPOINT") (pintype "bidirectional"))
      (node (ref "U30") (pin "12") (pinfunction "P2_12") (pintype "bidirectional"))
    )
    (net (code "123") (name "MOD6_OUT") (class "Default")
      (node (ref "J6") (pin "8") (pinfunction "MOD_OUT_8") (pintype "bidirectional"))
      (node (ref "U18") (pin "7") (pinfunction "B1_7") (pintype "bidirectional"))
    )
    (net (code "124") (name "MOD6_PPS") (class "Default")
      (node (ref "J6") (pin "7") (pinfunction "PPS_7") (pintype "bidirectional"))
      (node (ref "U12") (pin "6") (pinfunction "B2_6") (pintype "bidirectional"))
    )
    (net (code "125") (name "MOD6_SCL") (class "Default")
      (node (ref "J6") (pin "5") (pinfunction "SCL_5") (pintype "bidirectional"))
      (node (ref "R43") (pin "2") (pinfunction "2_2") (pintype "passive"))
      (node (ref "U6") (pin "6") (pinfunction "B1_6") (pintype "bidirectional"))
    )
    (net (code "126") (name "MOD6_SDA") (class "Default")
      (node (ref "J6") (pin "6") (pinfunction "SDA_6") (pintype "bidirectional"))
      (node (ref "R42") (pin "2") (pinfunction "2_2") (pintype "passive"))
      (node (ref "U6") (pin "7") (pinfunction "B0_7") (pintype "bidirectional"))
    )
    (net (code "127") (name "MOD6_USB+") (class "Default")
      (node (ref "J6") (pin "11") (pinfunction "USB_D+_11") (pintype "bidirectional"))
      (node (ref "U24") (pin "1") (pinfunction "D1+_1") (pintype "bidirectional"))
    )
    (net (code "128") (name "MOD6_USB-") (class "Default")
      (node (ref "J6") (pin "12") (pinfunction "USB_D-_12") (pintype "bidirectional"))
      (node (ref "U24") (pin "7") (pinfunction "D1-_7") (pintype "bidirectional"))
    )
    (net (code "129") (name "MOD6_USB_VBUS") (class "Default")
      (node (ref "C85") (pin "1") (pinfunction "1_1") (pintype "bidirectional"))
      (node (ref "C99") (pin "1") (pinfunction "1_1") (pintype "bidirectional"))
      (node (ref "J6") (pin "13") (pinfunction "USB_VBUS_13") (pintype "bidirectional"))
      (node (ref "S17") (pin "6") (pinfunction "OUT_6") (pintype "bidirectional"))
      (node (ref "S17") (pin "7") (pinfunction "OUT_7") (pintype "bidirectional"))
    )
    (net (code "130") (name "MOD6_USB_~{EN}") (class "Default")
      (node (ref "S11") (pin "4") (pinfunction "Z_4") (pintype "bidirectional"))
      (node (ref "S17") (pin "4") (pinfunction "~{EN}_4") (pintype "bidirectional"))
      (node (ref "U24") (pin "8") (pinfunction "~{OE}_8") (pintype "bidirectional"))
    )
    (net (code "131") (name "MOD6_VCCIO") (class "Default")
      (node (ref "C30") (pin "1") (pinfunction "1_1") (pintype "bidirectional"))
      (node (ref "C48") (pin "1") (pinfunction "1_1") (pintype "bidirectional"))
      (node (ref "C60") (pin "1") (pinfunction "1_1") (pintype "bidirectional"))
      (node (ref "J6") (pin "4") (pinfunction "VCCIO_4") (pintype "bidirectional"))
      (node (ref "R42") (pin "1") (pinfunction "1_1") (pintype "passive"))
      (node (ref "R43") (pin "1") (pinfunction "1_1") (pintype "passive"))
      (node (ref "U12") (pin "8") (pinfunction "VCC_B_8") (pintype "bidirectional"))
      (node (ref "U18") (pin "8") (pinfunction "VCC_B_8") (pintype "bidirectional"))
      (node (ref "U6") (pin "8") (pinfunction "VCC_B_8") (pintype "bidirectional"))
    )
    (net (code "132") (name "MOD7_5V") (class "Default")
      (node (ref "C38") (pin "1") (pinfunction "1_1") (pintype "bidirectional"))
      (node (ref "J7") (pin "2") (pinfunction "5V_2") (pintype "bidirectional"))
      (node (ref "S6") (pin "1") (pinfunction "VLOAD_1") (pintype "bidirectional"))
    )
    (net (code "133") (name "MOD7_5V_METERED") (class "Default")
      (node (ref "C86") (pin "1") (pinfunction "1_1") (pintype "bidirectional"))
      (node (ref "C93") (pin "1") (pinfunction "1_1") (pintype "bidirectional"))
      (node (ref "J4") (pin "12") (pinfunction "VCC_MOD7_12") (pintype "power_in"))
      (node (ref "S18") (pin "2") (pinfunction "IN_2") (pintype "bidirectional"))
      (node (ref "S18") (pin "3") (pinfunction "IN_3") (pintype "bidirectional"))
      (node (ref "S6") (pin "3") (pinfunction "VSUPP_3") (pintype "bidirectional"))
      (node (ref "TP21") (pin "TESTPOINT") (pinfunction "TESTPOINT_TESTPOINT") (pintype "bidirectional"))
    )
    (net (code "134") (name "MOD7_D+_HUB-SW") (class "Default")
      (node (ref "D4") (pin "4") (pinfunction "D_4") (pintype "bidirectional"))
      (node (ref "R11") (pin "2") (pinfunction "2_2") (pintype "passive"))
      (node (ref "R62") (pin "2") (pinfunction "2_2") (pintype "passive"))
      (node (ref "U25") (pin "3") (pinfunction "D+_3") (pintype "bidirectional"))
    )
    (net (code "135") (name "MOD7_D-_HUB-SW") (class "Default")
      (node (ref "D4") (pin "2") (pinfunction "C_2") (pintype "bidirectional"))
      (node (ref "R12") (pin "2") (pinfunction "2_2") (pintype "passive"))
      (node (ref "R63") (pin "2") (pinfunction "2_2") (pintype "passive"))
      (node (ref "U25") (pin "5") (pinfunction "D-_5") (pintype "bidirectional"))
    )
    (net (code "136") (name "MOD7_IN") (class "Default")
      (node (ref "J7") (pin "10") (pinfunction "MOD_IN_10") (pintype "bidirectional"))
      (node (ref "U13") (pin "7") (pinfunction "B1_7") (pintype "bidirectional"))
    )
    (net (code "137") (name "MOD7_ISO_I2C") (class "Default")
      (node (ref "LED1017") (pin "A") (pinfunction "ANODE_A") (pintype "bidirectional"))
      (node (ref "R82") (pin "2") (pinfunction "2_2") (pintype "passive"))
      (node (ref "TP1017") (pin "TESTPOINT") (pinfunction "TESTPOINT_TESTPOINT") (pintype "bidirectional"))
      (node (ref "U31") (pin "11") (pinfunction "P1_11") (pintype "bidirectional"))
      (node (ref "U7") (pin "5") (pinfunction "OE_5") (pintype "bidirectional"))
    )
    (net (code "138") (name "MOD7_ISO_POWER") (class "Default")
      (node (ref "LED1016") (pin "A") (pinfunction "ANODE_A") (pintype "bidirectional"))
      (node (ref "R81") (pin "2") (pinfunction "2_2") (pintype "passive"))
      (node (ref "S6") (pin "4") (pinfunction "EN_4") (pintype "bidirectional"))
      (node (ref "TP1016") (pin "TESTPOINT") (pinfunction "TESTPOINT_TESTPOINT") (pintype "bidirectional"))
      (node (ref "U31") (pin "10") (pinfunction "P0_10") (pintype "bidirectional"))
    )
    (net (code "139") (name "MOD7_ISO_USB") (class "Default")
      (node (ref "LED1018") (pin "A") (pinfunction "ANODE_A") (pintype "bidirectional"))
      (node (ref "R83") (pin "2") (pinfunction "2_2") (pintype "passive"))
      (node (ref "S12") (pin "6") (pinfunction "S_6") (pintype "bidirectional"))
      (node (ref "TP1018") (pin "TESTPOINT") (pinfunction "TESTPOINT_TESTPOINT") (pintype "bidirectional"))
      (node (ref "U31") (pin "12") (pinfunction "P2_12") (pintype "bidirectional"))
    )
    (net (code "140") (name "MOD7_OUT") (class "Default")
      (node (ref "J7") (pin "8") (pinfunction "MOD_OUT_8") (pintype "bidirectional"))
      (node (ref "U19") (pin "7") (pinfunction "B1_7") (pintype "bidirectional"))
    )
    (net (code "141") (name "MOD7_PPS") (class "Default")
      (node (ref "J7") (pin "7") (pinfunction "PPS_7") (pintype "bidirectional"))
      (node (ref "U13") (pin "6") (pinfunction "B2_6") (pintype "bidirectional"))
    )
    (net (code "142") (name "MOD7_SCL") (class "Default")
      (node (ref "J7") (pin "5") (pinfunction "SCL_5") (pintype "bidirectional"))
      (node (ref "R45") (pin "2") (pinfunction "2_2") (pintype "passive"))
      (node (ref "U7") (pin "6") (pinfunction "B1_6") (pintype "bidirectional"))
    )
    (net (code "143") (name "MOD7_SDA") (class "Default")
      (node (ref "J7") (pin "6") (pinfunction "SDA_6") (pintype "bidirectional"))
      (node (ref "R44") (pin "2") (pinfunction "2_2") (pintype "passive"))
      (node (ref "U7") (pin "7") (pinfunction "B0_7") (pintype "bidirectional"))
    )
    (net (code "144") (name "MOD7_USB+") (class "Default")
      (node (ref "J7") (pin "11") (pinfunction "USB_D+_11") (pintype "bidirectional"))
      (node (ref "U25") (pin "1") (pinfunction "D1+_1") (pintype "bidirectional"))
    )
    (net (code "145") (name "MOD7_USB-") (class "Default")
      (node (ref "J7") (pin "12") (pinfunction "USB_D-_12") (pintype "bidirectional"))
      (node (ref "U25") (pin "7") (pinfunction "D1-_7") (pintype "bidirectional"))
    )
    (net (code "146") (name "MOD7_USB_VBUS") (class "Default")
      (node (ref "C100") (pin "1") (pinfunction "1_1") (pintype "bidirectional"))
      (node (ref "C87") (pin "1") (pinfunction "1_1") (pintype "bidirectional"))
      (node (ref "J7") (pin "13") (pinfunction "USB_VBUS_13") (pintype "bidirectional"))
      (node (ref "S18") (pin "6") (pinfunction "OUT_6") (pintype "bidirectional"))
      (node (ref "S18") (pin "7") (pinfunction "OUT_7") (pintype "bidirectional"))
    )
    (net (code "147") (name "MOD7_USB_~{EN}") (class "Default")
      (node (ref "S12") (pin "4") (pinfunction "Z_4") (pintype "bidirectional"))
      (node (ref "S18") (pin "4") (pinfunction "~{EN}_4") (pintype "bidirectional"))
      (node (ref "U25") (pin "8") (pinfunction "~{OE}_8") (pintype "bidirectional"))
    )
    (net (code "148") (name "MOD7_VCCIO") (class "Default")
      (node (ref "C32") (pin "1") (pinfunction "1_1") (pintype "bidirectional"))
      (node (ref "C50") (pin "1") (pinfunction "1_1") (pintype "bidirectional"))
      (node (ref "C62") (pin "1") (pinfunction "1_1") (pintype "bidirectional"))
      (node (ref "J7") (pin "4") (pinfunction "VCCIO_4") (pintype "bidirectional"))
      (node (ref "R44") (pin "1") (pinfunction "1_1") (pintype "passive"))
      (node (ref "R45") (pin "1") (pinfunction "1_1") (pintype "passive"))
      (node (ref "U13") (pin "8") (pinfunction "VCC_B_8") (pintype "bidirectional"))
      (node (ref "U19") (pin "8") (pinfunction "VCC_B_8") (pintype "bidirectional"))
      (node (ref "U7") (pin "8") (pinfunction "VCC_B_8") (pintype "bidirectional"))
    )
    (net (code "149") (name "MOD_SCL") (class "Default")
      (node (ref "J3") (pin "24") (pinfunction "MODULES_SCL_24") (pintype "bidirectional"))
      (node (ref "R50") (pin "1") (pinfunction "1_1") (pintype "passive"))
      (node (ref "TP6") (pin "TESTPOINT") (pinfunction "TESTPOINT_TESTPOINT") (pintype "bidirectional"))
      (node (ref "U2") (pin "3") (pinfunction "A1_3") (pintype "bidirectional"))
      (node (ref "U3") (pin "3") (pinfunction "A1_3") (pintype "bidirectional"))
      (node (ref "U4") (pin "3") (pinfunction "A1_3") (pintype "bidirectional"))
      (node (ref "U5") (pin "3") (pinfunction "A1_3") (pintype "bidirectional"))
      (node (ref "U6") (pin "3") (pinfunction "A1_3") (pintype "bidirectional"))
      (node (ref "U7") (pin "3") (pinfunction "A1_3") (pintype "bidirectional"))
    )
    (net (code "150") (name "MOD_SDA") (class "Default")
      (node (ref "J3") (pin "23") (pinfunction "MODULES_SDA_23") (pintype "bidirectional"))
      (node (ref "R49") (pin "1") (pinfunction "1_1") (pintype "passive"))
      (node (ref "TP5") (pin "TESTPOINT") (pinfunction "TESTPOINT_TESTPOINT") (pintype "bidirectional"))
      (node (ref "U2") (pin "2") (pinfunction "A0_2") (pintype "bidirectional"))
      (node (ref "U3") (pin "2") (pinfunction "A0_2") (pintype "bidirectional"))
      (node (ref "U4") (pin "2") (pinfunction "A0_2") (pintype "bidirectional"))
      (node (ref "U5") (pin "2") (pinfunction "A0_2") (pintype "bidirectional"))
      (node (ref "U6") (pin "2") (pinfunction "A0_2") (pintype "bidirectional"))
      (node (ref "U7") (pin "2") (pinfunction "A0_2") (pintype "bidirectional"))
    )
    (net (code "151") (name "Net-(C2-Pad2)") (class "Default")
      (node (ref "C2") (pin "2") (pinfunction "2_2") (pintype "bidirectional"))
      (node (ref "R26") (pin "1") (pinfunction "1_1") (pintype "passive"))
      (node (ref "Y1") (pin "1") (pinfunction "1_1") (pintype "bidirectional"))
    )
    (net (code "152") (name "Net-(LED1001-ANODE)") (class "Default")
      (node (ref "LED1001") (pin "A") (pinfunction "ANODE_A") (pintype "bidirectional"))
      (node (ref "R1001") (pin "1") (pinfunction "1_1") (pintype "passive"))
    )
    (net (code "153") (name "Net-(LED1002-ANODE)") (class "Default")
      (node (ref "LED1002") (pin "A") (pinfunction "ANODE_A") (pintype "bidirectional"))
      (node (ref "R1002") (pin "1") (pinfunction "1_1") (pintype "passive"))
    )
    (net (code "154") (name "Net-(LED1003-ANODE)") (class "Default")
      (node (ref "LED1003") (pin "A") (pinfunction "ANODE_A") (pintype "bidirectional"))
      (node (ref "R1003") (pin "1") (pinfunction "1_1") (pintype "passive"))
    )
    (net (code "155") (name "Net-(LED1004-CATHODE)") (class "Default")
      (node (ref "LED1004") (pin "C") (pinfunction "CATHODE_C") (pintype "bidirectional"))
      (node (ref "R1004") (pin "2") (pinfunction "2_2") (pintype "passive"))
    )
    (net (code "156") (name "Net-(LED1005-CATHODE)") (class "Default")
      (node (ref "LED1005") (pin "C") (pinfunction "CATHODE_C") (pintype "bidirectional"))
      (node (ref "R1005") (pin "2") (pinfunction "2_2") (pintype "passive"))
    )
    (net (code "157") (name "Net-(LED1006-CATHODE)") (class "Default")
      (node (ref "LED1006") (pin "C") (pinfunction "CATHODE_C") (pintype "bidirectional"))
      (node (ref "R1006") (pin "2") (pinfunction "2_2") (pintype "passive"))
    )
    (net (code "158") (name "Net-(LED1007-ANODE)") (class "Default")
      (node (ref "LED1007") (pin "A") (pinfunction "ANODE_A") (pintype "bidirectional"))
      (node (ref "R1007") (pin "1") (pinfunction "1_1") (pintype "passive"))
    )
    (net (code "159") (name "Net-(LED1008-ANODE)") (class "Default")
      (node (ref "LED1008") (pin "A") (pinfunction "ANODE_A") (pintype "bidirectional"))
      (node (ref "R1008") (pin "1") (pinfunction "1_1") (pintype "passive"))
    )
    (net (code "160") (name "Net-(LED1009-ANODE)") (class "Default")
      (node (ref "LED1009") (pin "A") (pinfunction "ANODE_A") (pintype "bidirectional"))
      (node (ref "R1009") (pin "1") (pinfunction "1_1") (pintype "passive"))
    )
    (net (code "161") (name "Net-(LED1010-CATHODE)") (class "Default")
      (node (ref "LED1010") (pin "C") (pinfunction "CATHODE_C") (pintype "bidirectional"))
      (node (ref "R1010") (pin "2") (pinfunction "2_2") (pintype "passive"))
    )
    (net (code "162") (name "Net-(LED1011-CATHODE)") (class "Default")
      (node (ref "LED1011") (pin "C") (pinfunction "CATHODE_C") (pintype "bidirectional"))
      (node (ref "R1011") (pin "2") (pinfunction "2_2") (pintype "passive"))
    )
    (net (code "163") (name "Net-(LED1012-CATHODE)") (class "Default")
      (node (ref "LED1012") (pin "C") (pinfunction "CATHODE_C") (pintype "bidirectional"))
      (node (ref "R1012") (pin "2") (pinfunction "2_2") (pintype "passive"))
    )
    (net (code "164") (name "Net-(LED1013-ANODE)") (class "Default")
      (node (ref "LED1013") (pin "A") (pinfunction "ANODE_A") (pintype "bidirectional"))
      (node (ref "R1013") (pin "1") (pinfunction "1_1") (pintype "passive"))
    )
    (net (code "165") (name "Net-(LED1014-ANODE)") (class "Default")
      (node (ref "LED1014") (pin "A") (pinfunction "ANODE_A") (pintype "bidirectional"))
      (node (ref "R1014") (pin "1") (pinfunction "1_1") (pintype "passive"))
    )
    (net (code "166") (name "Net-(LED1015-ANODE)") (class "Default")
      (node (ref "LED1015") (pin "A") (pinfunction "ANODE_A") (pintype "bidirectional"))
      (node (ref "R1015") (pin "1") (pinfunction "1_1") (pintype "passive"))
    )
    (net (code "167") (name "Net-(LED1016-CATHODE)") (class "Default")
      (node (ref "LED1016") (pin "C") (pinfunction "CATHODE_C") (pintype "bidirectional"))
      (node (ref "R1016") (pin "2") (pinfunction "2_2") (pintype "passive"))
    )
    (net (code "168") (name "Net-(LED1017-CATHODE)") (class "Default")
      (node (ref "LED1017") (pin "C") (pinfunction "CATHODE_C") (pintype "bidirectional"))
      (node (ref "R1017") (pin "2") (pinfunction "2_2") (pintype "passive"))
    )
    (net (code "169") (name "Net-(LED1018-CATHODE)") (class "Default")
      (node (ref "LED1018") (pin "C") (pinfunction "CATHODE_C") (pintype "bidirectional"))
      (node (ref "R1018") (pin "2") (pinfunction "2_2") (pintype "passive"))
    )
    (net (code "170") (name "Net-(U1-DP0PUR)") (class "Default")
      (node (ref "R25") (pin "2") (pinfunction "2_2") (pintype "passive"))
      (node (ref "U1") (pin "2") (pinfunction "DP0PUR_2") (pintype "bidirectional"))
    )
    (net (code "171") (name "Net-(U1-XTAL1)") (class "Default")
      (node (ref "C1") (pin "2") (pinfunction "2_2") (pintype "bidirectional"))
      (node (ref "U1") (pin "45") (pinfunction "XTAL1_45") (pintype "bidirectional"))
      (node (ref "Y1") (pin "3") (pinfunction "2_3") (pintype "bidirectional"))
    )
    (net (code "172") (name "Net-(U1-XTAL2)") (class "Default")
      (node (ref "R26") (pin "2") (pinfunction "2_2") (pintype "passive"))
      (node (ref "U1") (pin "44") (pinfunction "XTAL2_44") (pintype "bidirectional"))
    )
    (net (code "173") (name "Net-(U20-D2+)") (class "Default")
      (node (ref "R13") (pin "1") (pinfunction "1_1") (pintype "passive"))
      (node (ref "U20") (pin "2") (pinfunction "D2+_2") (pintype "bidirectional"))
    )
    (net (code "174") (name "Net-(U20-D2-)") (class "Default")
      (node (ref "R14") (pin "1") (pinfunction "1_1") (pintype "passive"))
      (node (ref "U20") (pin "6") (pinfunction "D2-_6") (pintype "bidirectional"))
    )
    (net (code "175") (name "Net-(U21-D2+)") (class "Default")
      (node (ref "R15") (pin "1") (pinfunction "1_1") (pintype "passive"))
      (node (ref "U21") (pin "2") (pinfunction "D2+_2") (pintype "bidirectional"))
    )
    (net (code "176") (name "Net-(U21-D2-)") (class "Default")
      (node (ref "R16") (pin "1") (pinfunction "1_1") (pintype "passive"))
      (node (ref "U21") (pin "6") (pinfunction "D2-_6") (pintype "bidirectional"))
    )
    (net (code "177") (name "Net-(U22-D2+)") (class "Default")
      (node (ref "R17") (pin "1") (pinfunction "1_1") (pintype "passive"))
      (node (ref "U22") (pin "2") (pinfunction "D2+_2") (pintype "bidirectional"))
    )
    (net (code "178") (name "Net-(U22-D2-)") (class "Default")
      (node (ref "R18") (pin "1") (pinfunction "1_1") (pintype "passive"))
      (node (ref "U22") (pin "6") (pinfunction "D2-_6") (pintype "bidirectional"))
    )
    (net (code "179") (name "Net-(U23-D2+)") (class "Default")
      (node (ref "R19") (pin "1") (pinfunction "1_1") (pintype "passive"))
      (node (ref "U23") (pin "2") (pinfunction "D2+_2") (pintype "bidirectional"))
    )
    (net (code "180") (name "Net-(U23-D2-)") (class "Default")
      (node (ref "R20") (pin "1") (pinfunction "1_1") (pintype "passive"))
      (node (ref "U23") (pin "6") (pinfunction "D2-_6") (pintype "bidirectional"))
    )
    (net (code "181") (name "Net-(U24-D2+)") (class "Default")
      (node (ref "R21") (pin "1") (pinfunction "1_1") (pintype "passive"))
      (node (ref "U24") (pin "2") (pinfunction "D2+_2") (pintype "bidirectional"))
    )
    (net (code "182") (name "Net-(U24-D2-)") (class "Default")
      (node (ref "R22") (pin "1") (pinfunction "1_1") (pintype "passive"))
      (node (ref "U24") (pin "6") (pinfunction "D2-_6") (pintype "bidirectional"))
    )
    (net (code "183") (name "Net-(U25-D2+)") (class "Default")
      (node (ref "R23") (pin "1") (pinfunction "1_1") (pintype "passive"))
      (node (ref "U25") (pin "2") (pinfunction "D2+_2") (pintype "bidirectional"))
    )
    (net (code "184") (name "Net-(U25-D2-)") (class "Default")
      (node (ref "R24") (pin "1") (pinfunction "1_1") (pintype "passive"))
      (node (ref "U25") (pin "6") (pinfunction "D2-_6") (pintype "bidirectional"))
    )
    (net (code "185") (name "PPS") (class "Default")
      (node (ref "J3") (pin "25") (pinfunction "PPS_25") (pintype "bidirectional"))
      (node (ref "TP10") (pin "TESTPOINT") (pinfunction "TESTPOINT_TESTPOINT") (pintype "bidirectional"))
      (node (ref "U10") (pin "3") (pinfunction "A2_3") (pintype "bidirectional"))
      (node (ref "U11") (pin "3") (pinfunction "A2_3") (pintype "bidirectional"))
      (node (ref "U12") (pin "3") (pinfunction "A2_3") (pintype "bidirectional"))
      (node (ref "U13") (pin "3") (pinfunction "A2_3") (pintype "bidirectional"))
      (node (ref "U8") (pin "3") (pinfunction "A2_3") (pintype "bidirectional"))
      (node (ref "U9") (pin "3") (pinfunction "A2_3") (pintype "bidirectional"))
    )
    (net (code "186") (name "SMBCLK") (class "Default")
      (node (ref "J3") (pin "5") (pinfunction "SMBCLK_5") (pintype "bidirectional"))
      (node (ref "J4") (pin "5") (pinfunction "SMBCLK_5") (pintype "open_collector"))
      (node (ref "R47") (pin "1") (pinfunction "1_1") (pintype "passive"))
      (node (ref "TP2") (pin "TESTPOINT") (pinfunction "TESTPOINT_TESTPOINT") (pintype "bidirectional"))
      (node (ref "U26") (pin "1") (pinfunction "SCL_1") (pintype "bidirectional"))
      (node (ref "U27") (pin "1") (pinfunction "SCL_1") (pintype "bidirectional"))
      (node (ref "U28") (pin "1") (pinfunction "SCL_1") (pintype "bidirectional"))
      (node (ref "U29") (pin "1") (pinfunction "SCL_1") (pintype "bidirectional"))
      (node (ref "U30") (pin "1") (pinfunction "SCL_1") (pintype "bidirectional"))
      (node (ref "U31") (pin "1") (pinfunction "SCL_1") (pintype "bidirectional"))
    )
    (net (code "187") (name "SMBDATA") (class "Default")
      (node (ref "J3") (pin "3") (pinfunction "SMBDATA_3") (pintype "bidirectional"))
      (node (ref "J4") (pin "3") (pinfunction "SMBDATA_3") (pintype "open_collector"))
      (node (ref "R46") (pin "1") (pinfunction "1_1") (pintype "passive"))
      (node (ref "TP1") (pin "TESTPOINT") (pinfunction "TESTPOINT_TESTPOINT") (pintype "bidirectional"))
      (node (ref "U26") (pin "2") (pinfunction "SDA_2") (pintype "bidirectional"))
      (node (ref "U27") (pin "2") (pinfunction "SDA_2") (pintype "bidirectional"))
      (node (ref "U28") (pin "2") (pinfunction "SDA_2") (pintype "bidirectional"))
      (node (ref "U29") (pin "2") (pinfunction "SDA_2") (pintype "bidirectional"))
      (node (ref "U30") (pin "2") (pinfunction "SDA_2") (pintype "bidirectional"))
      (node (ref "U31") (pin "2") (pinfunction "SDA_2") (pintype "bidirectional"))
    )
    (net (code "188") (name "USB_SUSPEND_STATUS") (class "Default")
      (node (ref "TP31") (pin "TESTPOINT") (pinfunction "TESTPOINT_TESTPOINT") (pintype "bidirectional"))
      (node (ref "U1") (pin "1") (pinfunction "SUSPND_1") (pintype "bidirectional"))
    )
    (net (code "189") (name "VBATT+") (class "Default")
      (node (ref "J4") (pin "17") (pinfunction "VBATT+_17") (pintype "power_in"))
      (node (ref "TP14") (pin "TESTPOINT") (pinfunction "TESTPOINT_TESTPOINT") (pintype "bidirectional"))
    )
    (net (code "190") (name "VBATT-") (class "Default")
      (node (ref "J4") (pin "18") (pinfunction "VBATT-_18") (pintype "power_in"))
      (node (ref "TP15") (pin "TESTPOINT") (pinfunction "TESTPOINT_TESTPOINT") (pintype "bidirectional"))
    )
    (net (code "191") (name "VCC_BACKPLANE") (class "Default")
      (node (ref "C15") (pin "1") (pinfunction "1_1") (pintype "bidirectional"))
      (node (ref "C16") (pin "1") (pinfunction "1_1") (pintype "bidirectional"))
      (node (ref "C17") (pin "1") (pinfunction "1_1") (pintype "bidirectional"))
      (node (ref "C18") (pin "1") (pinfunction "1_1") (pintype "bidirectional"))
      (node (ref "C19") (pin "1") (pinfunction "1_1") (pintype "bidirectional"))
      (node (ref "C20") (pin "1") (pinfunction "1_1") (pintype "bidirectional"))
      (node (ref "C21") (pin "1") (pinfunction "1_1") (pintype "bidirectional"))
      (node (ref "C23") (pin "1") (pinfunction "1_1") (pintype "bidirectional"))
      (node (ref "C25") (pin "1") (pinfunction "1_1") (pintype "bidirectional"))
      (node (ref "C27") (pin "1") (pinfunction "1_1") (pintype "bidirectional"))
      (node (ref "C29") (pin "1") (pinfunction "1_1") (pintype "bidirectional"))
      (node (ref "C31") (pin "1") (pinfunction "1_1") (pintype "bidirectional"))
      (node (ref "C39") (pin "1") (pinfunction "1_1") (pintype "bidirectional"))
      (node (ref "C41") (pin "1") (pinfunction "1_1") (pintype "bidirectional"))
      (node (ref "C43") (pin "1") (pinfunction "1_1") (pintype "bidirectional"))
      (node (ref "C45") (pin "1") (pinfunction "1_1") (pintype "bidirectional"))
      (node (ref "C47") (pin "1") (pinfunction "1_1") (pintype "bidirectional"))
      (node (ref "C49") (pin "1") (pinfunction "1_1") (pintype "bidirectional"))
      (node (ref "C51") (pin "1") (pinfunction "1_1") (pintype "bidirectional"))
      (node (ref "C53") (pin "1") (pinfunction "1_1") (pintype "bidirectional"))
      (node (ref "C55") (pin "1") (pinfunction "1_1") (pintype "bidirectional"))
      (node (ref "C57") (pin "1") (pinfunction "1_1") (pintype "bidirectional"))
      (node (ref "C59") (pin "1") (pinfunction "1_1") (pintype "bidirectional"))
      (node (ref "C61") (pin "1") (pinfunction "1_1") (pintype "bidirectional"))
      (node (ref "C63") (pin "2") (pinfunction "2_2") (pintype "bidirectional"))
      (node (ref "C64") (pin "2") (pinfunction "2_2") (pintype "bidirectional"))
      (node (ref "C65") (pin "2") (pinfunction "2_2") (pintype "bidirectional"))
      (node (ref "C66") (pin "2") (pinfunction "2_2") (pintype "bidirectional"))
      (node (ref "C67") (pin "2") (pinfunction "2_2") (pintype "bidirectional"))
      (node (ref "C68") (pin "2") (pinfunction "2_2") (pintype "bidirectional"))
      (node (ref "C69") (pin "2") (pinfunction "2_2") (pintype "bidirectional"))
      (node (ref "C70") (pin "1") (pinfunction "1_1") (pintype "bidirectional"))
      (node (ref "C71") (pin "1") (pinfunction "1_1") (pintype "bidirectional"))
      (node (ref "C72") (pin "1") (pinfunction "1_1") (pintype "bidirectional"))
      (node (ref "C73") (pin "1") (pinfunction "1_1") (pintype "bidirectional"))
      (node (ref "C74") (pin "1") (pinfunction "1_1") (pintype "bidirectional"))
      (node (ref "C75") (pin "1") (pinfunction "1_1") (pintype "bidirectional"))
      (node (ref "C94") (pin "2") (pinfunction "2_2") (pintype "bidirectional"))
      (node (ref "J4") (pin "13") (pinfunction "VCC_BACKPLANE_13") (pintype "power_in"))
      (node (ref "R27") (pin "1") (pinfunction "1_1") (pintype "passive"))
      (node (ref "R28") (pin "2") (pinfunction "2_2") (pintype "passive"))
      (node (ref "R29") (pin "2") (pinfunction "2_2") (pintype "passive"))
      (node (ref "R30") (pin "2") (pinfunction "2_2") (pintype "passive"))
      (node (ref "R31") (pin "2") (pinfunction "2_2") (pintype "passive"))
      (node (ref "R32") (pin "2") (pinfunction "2_2") (pintype "passive"))
      (node (ref "R33") (pin "2") (pinfunction "2_2") (pintype "passive"))
      (node (ref "R46") (pin "2") (pinfunction "2_2") (pintype "passive"))
      (node (ref "R47") (pin "2") (pinfunction "2_2") (pintype "passive"))
      (node (ref "R48") (pin "2") (pinfunction "2_2") (pintype "passive"))
      (node (ref "R49") (pin "2") (pinfunction "2_2") (pintype "passive"))
      (node (ref "R50") (pin "2") (pinfunction "2_2") (pintype "passive"))
      (node (ref "R51") (pin "2") (pinfunction "2_2") (pintype "passive"))
      (node (ref "S10") (pin "3") (pinfunction "I0_3") (pintype "bidirectional"))
      (node (ref "S10") (pin "5") (pinfunction "VCC_5") (pintype "bidirectional"))
      (node (ref "S11") (pin "3") (pinfunction "I0_3") (pintype "bidirectional"))
      (node (ref "S11") (pin "5") (pinfunction "VCC_5") (pintype "bidirectional"))
      (node (ref "S12") (pin "3") (pinfunction "I0_3") (pintype "bidirectional"))
      (node (ref "S12") (pin "5") (pinfunction "VCC_5") (pintype "bidirectional"))
      (node (ref "S7") (pin "3") (pinfunction "I0_3") (pintype "bidirectional"))
      (node (ref "S7") (pin "5") (pinfunction "VCC_5") (pintype "bidirectional"))
      (node (ref "S8") (pin "3") (pinfunction "I0_3") (pintype "bidirectional"))
      (node (ref "S8") (pin "5") (pinfunction "VCC_5") (pintype "bidirectional"))
      (node (ref "S9") (pin "3") (pinfunction "I0_3") (pintype "bidirectional"))
      (node (ref "S9") (pin "5") (pinfunction "VCC_5") (pintype "bidirectional"))
      (node (ref "TP24") (pin "TESTPOINT") (pinfunction "TESTPOINT_TESTPOINT") (pintype "bidirectional"))
      (node (ref "TP8") (pin "TESTPOINT") (pinfunction "TESTPOINT_TESTPOINT") (pintype "bidirectional"))
      (node (ref "U1") (pin "46") (pinfunction "VCC_46") (pintype "bidirectional"))
      (node (ref "U1") (pin "47") (pinfunction "~{EXTMEM}_47") (pintype "bidirectional"))
      (node (ref "U1") (pin "8") (pinfunction "EEDATA/~{GANGED}_8") (pintype "bidirectional"))
      (node (ref "U1") (pin "9") (pinfunction "VCC_9") (pintype "bidirectional"))
      (node (ref "U10") (pin "1") (pinfunction "VCC_A_1") (pintype "bidirectional"))
      (node (ref "U10") (pin "5") (pinfunction "DIR_5") (pintype "bidirectional"))
      (node (ref "U11") (pin "1") (pinfunction "VCC_A_1") (pintype "bidirectional"))
      (node (ref "U11") (pin "5") (pinfunction "DIR_5") (pintype "bidirectional"))
      (node (ref "U12") (pin "1") (pinfunction "VCC_A_1") (pintype "bidirectional"))
      (node (ref "U12") (pin "5") (pinfunction "DIR_5") (pintype "bidirectional"))
      (node (ref "U13") (pin "1") (pinfunction "VCC_A_1") (pintype "bidirectional"))
      (node (ref "U13") (pin "5") (pinfunction "DIR_5") (pintype "bidirectional"))
      (node (ref "U14") (pin "1") (pinfunction "VCC_A_1") (pintype "bidirectional"))
      (node (ref "U15") (pin "1") (pinfunction "VCC_A_1") (pintype "bidirectional"))
      (node (ref "U16") (pin "1") (pinfunction "VCC_A_1") (pintype "bidirectional"))
      (node (ref "U17") (pin "1") (pinfunction "VCC_A_1") (pintype "bidirectional"))
      (node (ref "U18") (pin "1") (pinfunction "VCC_A_1") (pintype "bidirectional"))
      (node (ref "U19") (pin "1") (pinfunction "VCC_A_1") (pintype "bidirectional"))
      (node (ref "U2") (pin "1") (pinfunction "VCC_A_1") (pintype "bidirectional"))
      (node (ref "U20") (pin "9") (pinfunction "VCC_9") (pintype "bidirectional"))
      (node (ref "U21") (pin "9") (pinfunction "VCC_9") (pintype "bidirectional"))
      (node (ref "U22") (pin "9") (pinfunction "VCC_9") (pintype "bidirectional"))
      (node (ref "U23") (pin "9") (pinfunction "VCC_9") (pintype "bidirectional"))
      (node (ref "U24") (pin "9") (pinfunction "VCC_9") (pintype "bidirectional"))
      (node (ref "U25") (pin "9") (pinfunction "VCC_9") (pintype "bidirectional"))
      (node (ref "U26") (pin "18") (pinfunction "VCC_18") (pintype "bidirectional"))
      (node (ref "U27") (pin "18") (pinfunction "VCC_18") (pintype "bidirectional"))
      (node (ref "U27") (pin "5") (pinfunction "A0_5") (pintype "bidirectional"))
      (node (ref "U28") (pin "18") (pinfunction "VCC_18") (pintype "bidirectional"))
      (node (ref "U28") (pin "4") (pinfunction "A1_4") (pintype "bidirectional"))
      (node (ref "U29") (pin "18") (pinfunction "VCC_18") (pintype "bidirectional"))
      (node (ref "U29") (pin "3") (pinfunction "A2_3") (pintype "bidirectional"))
      (node (ref "U29") (pin "5") (pinfunction "A0_5") (pintype "bidirectional"))
      (node (ref "U3") (pin "1") (pinfunction "VCC_A_1") (pintype "bidirectional"))
      (node (ref "U30") (pin "18") (pinfunction "VCC_18") (pintype "bidirectional"))
      (node (ref "U30") (pin "3") (pinfunction "A2_3") (pintype "bidirectional"))
      (node (ref "U30") (pin "4") (pinfunction "A1_4") (pintype "bidirectional"))
      (node (ref "U31") (pin "18") (pinfunction "VCC_18") (pintype "bidirectional"))
      (node (ref "U31") (pin "3") (pinfunction "A2_3") (pintype "bidirectional"))
      (node (ref "U31") (pin "4") (pinfunction "A1_4") (pintype "bidirectional"))
      (node (ref "U31") (pin "5") (pinfunction "A0_5") (pintype "bidirectional"))
      (node (ref "U4") (pin "1") (pinfunction "VCC_A_1") (pintype "bidirectional"))
      (node (ref "U5") (pin "1") (pinfunction "VCC_A_1") (pintype "bidirectional"))
      (node (ref "U6") (pin "1") (pinfunction "VCC_A_1") (pintype "bidirectional"))
      (node (ref "U7") (pin "1") (pinfunction "VCC_A_1") (pintype "bidirectional"))
      (node (ref "U8") (pin "1") (pinfunction "VCC_A_1") (pintype "bidirectional"))
      (node (ref "U8") (pin "5") (pinfunction "DIR_5") (pintype "bidirectional"))
      (node (ref "U9") (pin "1") (pinfunction "VCC_A_1") (pintype "bidirectional"))
      (node (ref "U9") (pin "5") (pinfunction "DIR_5") (pintype "bidirectional"))
    )
    (net (code "192") (name "VCC_CONTROLLER") (class "Default")
      (node (ref "J3") (pin "2") (pinfunction "VCC_CONTROLLER_2") (pintype "bidirectional"))
      (node (ref "J4") (pin "2") (pinfunction "VCC_CONTROLLER_2") (pintype "power_in"))
      (node (ref "TP22") (pin "TESTPOINT") (pinfunction "TESTPOINT_TESTPOINT") (pintype "bidirectional"))
    )
    (net (code "193") (name "VCC_LINUX") (class "Default")
      (node (ref "J3") (pin "4") (pinfunction "VCC_LINUX_4") (pintype "bidirectional"))
      (node (ref "J4") (pin "4") (pinfunction "VCC_LINUX_4") (pintype "power_in"))
      (node (ref "TP23") (pin "TESTPOINT") (pinfunction "TESTPOINT_TESTPOINT") (pintype "bidirectional"))
    )
    (net (code "194") (name "VSOL+") (class "Default")
      (node (ref "J4") (pin "19") (pinfunction "VSOL+_19") (pintype "power_in"))
      (node (ref "TP12") (pin "TESTPOINT") (pinfunction "TESTPOINT_TESTPOINT") (pintype "bidirectional"))
    )
    (net (code "195") (name "VSOL-") (class "Default")
      (node (ref "J4") (pin "20") (pinfunction "VSOL-_20") (pintype "power_in"))
      (node (ref "TP13") (pin "TESTPOINT") (pinfunction "TESTPOINT_TESTPOINT") (pintype "bidirectional"))
    )
    (net (code "196") (name "unconnected-(D2-C-Pad2)") (class "Default")
      (node (ref "D2") (pin "2") (pinfunction "C_2") (pintype "bidirectional"))
    )
    (net (code "197") (name "unconnected-(D2-D-Pad4)") (class "Default")
      (node (ref "D2") (pin "4") (pinfunction "D_4") (pintype "bidirectional"))
    )
    (net (code "198") (name "unconnected-(D3-A-Pad8)") (class "Default")
      (node (ref "D3") (pin "8") (pinfunction "A_8") (pintype "bidirectional"))
    )
    (net (code "199") (name "unconnected-(D3-B-Pad6)") (class "Default")
      (node (ref "D3") (pin "6") (pinfunction "B_6") (pintype "bidirectional"))
    )
    (net (code "200") (name "unconnected-(U1-EECLK-Pad7)") (class "Default")
      (node (ref "U1") (pin "7") (pinfunction "EECLK_7") (pintype "bidirectional"))
    )
    (net (code "201") (name "unconnected-(U14-A2-Pad3)") (class "Default")
      (node (ref "U14") (pin "3") (pinfunction "A2_3") (pintype "bidirectional"))
    )
    (net (code "202") (name "unconnected-(U14-B2-Pad6)") (class "Default")
      (node (ref "U14") (pin "6") (pinfunction "B2_6") (pintype "bidirectional"))
    )
    (net (code "203") (name "unconnected-(U15-A2-Pad3)") (class "Default")
      (node (ref "U15") (pin "3") (pinfunction "A2_3") (pintype "bidirectional"))
    )
    (net (code "204") (name "unconnected-(U15-B2-Pad6)") (class "Default")
      (node (ref "U15") (pin "6") (pinfunction "B2_6") (pintype "bidirectional"))
    )
    (net (code "205") (name "unconnected-(U16-A2-Pad3)") (class "Default")
      (node (ref "U16") (pin "3") (pinfunction "A2_3") (pintype "bidirectional"))
    )
    (net (code "206") (name "unconnected-(U16-B2-Pad6)") (class "Default")
      (node (ref "U16") (pin "6") (pinfunction "B2_6") (pintype "bidirectional"))
    )
    (net (code "207") (name "unconnected-(U17-A2-Pad3)") (class "Default")
      (node (ref "U17") (pin "3") (pinfunction "A2_3") (pintype "bidirectional"))
    )
    (net (code "208") (name "unconnected-(U17-B2-Pad6)") (class "Default")
      (node (ref "U17") (pin "6") (pinfunction "B2_6") (pintype "bidirectional"))
    )
    (net (code "209") (name "unconnected-(U18-A2-Pad3)") (class "Default")
      (node (ref "U18") (pin "3") (pinfunction "A2_3") (pintype "bidirectional"))
    )
    (net (code "210") (name "unconnected-(U18-B2-Pad6)") (class "Default")
      (node (ref "U18") (pin "6") (pinfunction "B2_6") (pintype "bidirectional"))
    )
    (net (code "211") (name "unconnected-(U18-DIR-Pad5)") (class "Default")
      (node (ref "U18") (pin "5") (pinfunction "DIR_5") (pintype "bidirectional"))
    )
    (net (code "212") (name "unconnected-(U19-A2-Pad3)") (class "Default")
      (node (ref "U19") (pin "3") (pinfunction "A2_3") (pintype "bidirectional"))
    )
    (net (code "213") (name "unconnected-(U19-B2-Pad6)") (class "Default")
      (node (ref "U19") (pin "6") (pinfunction "B2_6") (pintype "bidirectional"))
    )
    (net (code "214") (name "unconnected-(U26-INT-Pad8)") (class "Default")
      (node (ref "U26") (pin "8") (pinfunction "INT_8") (pintype "bidirectional"))
    )
    (net (code "215") (name "unconnected-(U26-P3-Pad13)") (class "Default")
      (node (ref "U26") (pin "13") (pinfunction "P3_13") (pintype "bidirectional"))
    )
    (net (code "216") (name "unconnected-(U26-P4-Pad14)") (class "Default")
      (node (ref "U26") (pin "14") (pinfunction "P4_14") (pintype "bidirectional"))
    )
    (net (code "217") (name "unconnected-(U26-P5-Pad15)") (class "Default")
      (node (ref "U26") (pin "15") (pinfunction "P5_15") (pintype "bidirectional"))
    )
    (net (code "218") (name "unconnected-(U26-P6-Pad16)") (class "Default")
      (node (ref "U26") (pin "16") (pinfunction "P6_16") (pintype "bidirectional"))
    )
    (net (code "219") (name "unconnected-(U26-P7-Pad17)") (class "Default")
      (node (ref "U26") (pin "17") (pinfunction "P7_17") (pintype "bidirectional"))
    )
    (net (code "220") (name "unconnected-(U27-INT-Pad8)") (class "Default")
      (node (ref "U27") (pin "8") (pinfunction "INT_8") (pintype "bidirectional"))
    )
    (net (code "221") (name "unconnected-(U27-P3-Pad13)") (class "Default")
      (node (ref "U27") (pin "13") (pinfunction "P3_13") (pintype "bidirectional"))
    )
    (net (code "222") (name "unconnected-(U27-P4-Pad14)") (class "Default")
      (node (ref "U27") (pin "14") (pinfunction "P4_14") (pintype "bidirectional"))
    )
    (net (code "223") (name "unconnected-(U27-P5-Pad15)") (class "Default")
      (node (ref "U27") (pin "15") (pinfunction "P5_15") (pintype "bidirectional"))
    )
    (net (code "224") (name "unconnected-(U27-P6-Pad16)") (class "Default")
      (node (ref "U27") (pin "16") (pinfunction "P6_16") (pintype "bidirectional"))
    )
    (net (code "225") (name "unconnected-(U27-P7-Pad17)") (class "Default")
      (node (ref "U27") (pin "17") (pinfunction "P7_17") (pintype "bidirectional"))
    )
    (net (code "226") (name "unconnected-(U28-INT-Pad8)") (class "Default")
      (node (ref "U28") (pin "8") (pinfunction "INT_8") (pintype "bidirectional"))
    )
    (net (code "227") (name "unconnected-(U28-P3-Pad13)") (class "Default")
      (node (ref "U28") (pin "13") (pinfunction "P3_13") (pintype "bidirectional"))
    )
    (net (code "228") (name "unconnected-(U28-P4-Pad14)") (class "Default")
      (node (ref "U28") (pin "14") (pinfunction "P4_14") (pintype "bidirectional"))
    )
    (net (code "229") (name "unconnected-(U28-P5-Pad15)") (class "Default")
      (node (ref "U28") (pin "15") (pinfunction "P5_15") (pintype "bidirectional"))
    )
    (net (code "230") (name "unconnected-(U28-P6-Pad16)") (class "Default")
      (node (ref "U28") (pin "16") (pinfunction "P6_16") (pintype "bidirectional"))
    )
    (net (code "231") (name "unconnected-(U28-P7-Pad17)") (class "Default")
      (node (ref "U28") (pin "17") (pinfunction "P7_17") (pintype "bidirectional"))
    )
    (net (code "232") (name "unconnected-(U29-INT-Pad8)") (class "Default")
      (node (ref "U29") (pin "8") (pinfunction "INT_8") (pintype "bidirectional"))
    )
    (net (code "233") (name "unconnected-(U29-P3-Pad13)") (class "Default")
      (node (ref "U29") (pin "13") (pinfunction "P3_13") (pintype "bidirectional"))
    )
    (net (code "234") (name "unconnected-(U29-P4-Pad14)") (class "Default")
      (node (ref "U29") (pin "14") (pinfunction "P4_14") (pintype "bidirectional"))
    )
    (net (code "235") (name "unconnected-(U29-P5-Pad15)") (class "Default")
      (node (ref "U29") (pin "15") (pinfunction "P5_15") (pintype "bidirectional"))
    )
    (net (code "236") (name "unconnected-(U29-P6-Pad16)") (class "Default")
      (node (ref "U29") (pin "16") (pinfunction "P6_16") (pintype "bidirectional"))
    )
    (net (code "237") (name "unconnected-(U29-P7-Pad17)") (class "Default")
      (node (ref "U29") (pin "17") (pinfunction "P7_17") (pintype "bidirectional"))
    )
    (net (code "238") (name "unconnected-(U30-INT-Pad8)") (class "Default")
      (node (ref "U30") (pin "8") (pinfunction "INT_8") (pintype "bidirectional"))
    )
    (net (code "239") (name "unconnected-(U30-P3-Pad13)") (class "Default")
      (node (ref "U30") (pin "13") (pinfunction "P3_13") (pintype "bidirectional"))
    )
    (net (code "240") (name "unconnected-(U30-P4-Pad14)") (class "Default")
      (node (ref "U30") (pin "14") (pinfunction "P4_14") (pintype "bidirectional"))
    )
    (net (code "241") (name "unconnected-(U30-P5-Pad15)") (class "Default")
      (node (ref "U30") (pin "15") (pinfunction "P5_15") (pintype "bidirectional"))
    )
    (net (code "242") (name "unconnected-(U30-P6-Pad16)") (class "Default")
      (node (ref "U30") (pin "16") (pinfunction "P6_16") (pintype "bidirectional"))
    )
    (net (code "243") (name "unconnected-(U30-P7-Pad17)") (class "Default")
      (node (ref "U30") (pin "17") (pinfunction "P7_17") (pintype "bidirectional"))
    )
    (net (code "244") (name "unconnected-(U31-INT-Pad8)") (class "Default")
      (node (ref "U31") (pin "8") (pinfunction "INT_8") (pintype "bidirectional"))
    )
    (net (code "245") (name "unconnected-(U31-P3-Pad13)") (class "Default")
      (node (ref "U31") (pin "13") (pinfunction "P3_13") (pintype "bidirectional"))
    )
    (net (code "246") (name "unconnected-(U31-P4-Pad14)") (class "Default")
      (node (ref "U31") (pin "14") (pinfunction "P4_14") (pintype "bidirectional"))
    )
    (net (code "247") (name "unconnected-(U31-P5-Pad15)") (class "Default")
      (node (ref "U31") (pin "15") (pinfunction "P5_15") (pintype "bidirectional"))
    )
    (net (code "248") (name "unconnected-(U31-P6-Pad16)") (class "Default")
      (node (ref "U31") (pin "16") (pinfunction "P6_16") (pintype "bidirectional"))
    )
    (net (code "249") (name "unconnected-(U31-P7-Pad17)") (class "Default")
      (node (ref "U31") (pin "17") (pinfunction "P7_17") (pintype "bidirectional"))
    )
    (net (code "250") (name "~{BACKPLANE_RESET}") (class "Default")
      (node (ref "J3") (pin "22") (pinfunction "~{BACKPLANE_RESET}_22") (pintype "bidirectional"))
      (node (ref "R27") (pin "2") (pinfunction "2_2") (pintype "passive"))
      (node (ref "TP9") (pin "TESTPOINT") (pinfunction "TESTPOINT_TESTPOINT") (pintype "bidirectional"))
      (node (ref "U1") (pin "6") (pinfunction "~{RESET}_6") (pintype "bidirectional"))
      (node (ref "U26") (pin "6") (pinfunction "~{RESET}_6") (pintype "bidirectional"))
      (node (ref "U27") (pin "6") (pinfunction "~{RESET}_6") (pintype "bidirectional"))
      (node (ref "U28") (pin "6") (pinfunction "~{RESET}_6") (pintype "bidirectional"))
      (node (ref "U29") (pin "6") (pinfunction "~{RESET}_6") (pintype "bidirectional"))
      (node (ref "U30") (pin "6") (pinfunction "~{RESET}_6") (pintype "bidirectional"))
      (node (ref "U31") (pin "6") (pinfunction "~{RESET}_6") (pintype "bidirectional"))
    )
    (net (code "251") (name "~{SMBALERT}") (class "Default")
      (node (ref "J3") (pin "6") (pinfunction "~{SMBALERT}_6") (pintype "bidirectional"))
      (node (ref "J4") (pin "6") (pinfunction "~{SMBALERT}_6") (pintype "bidirectional"))
      (node (ref "R48") (pin "1") (pinfunction "1_1") (pintype "passive"))
      (node (ref "TP3") (pin "TESTPOINT") (pinfunction "TESTPOINT_TESTPOINT") (pintype "bidirectional"))
    )
  )
)
